# soundcard_v2_2.net
KiCad netlist of a schematic drawn in EAGLE
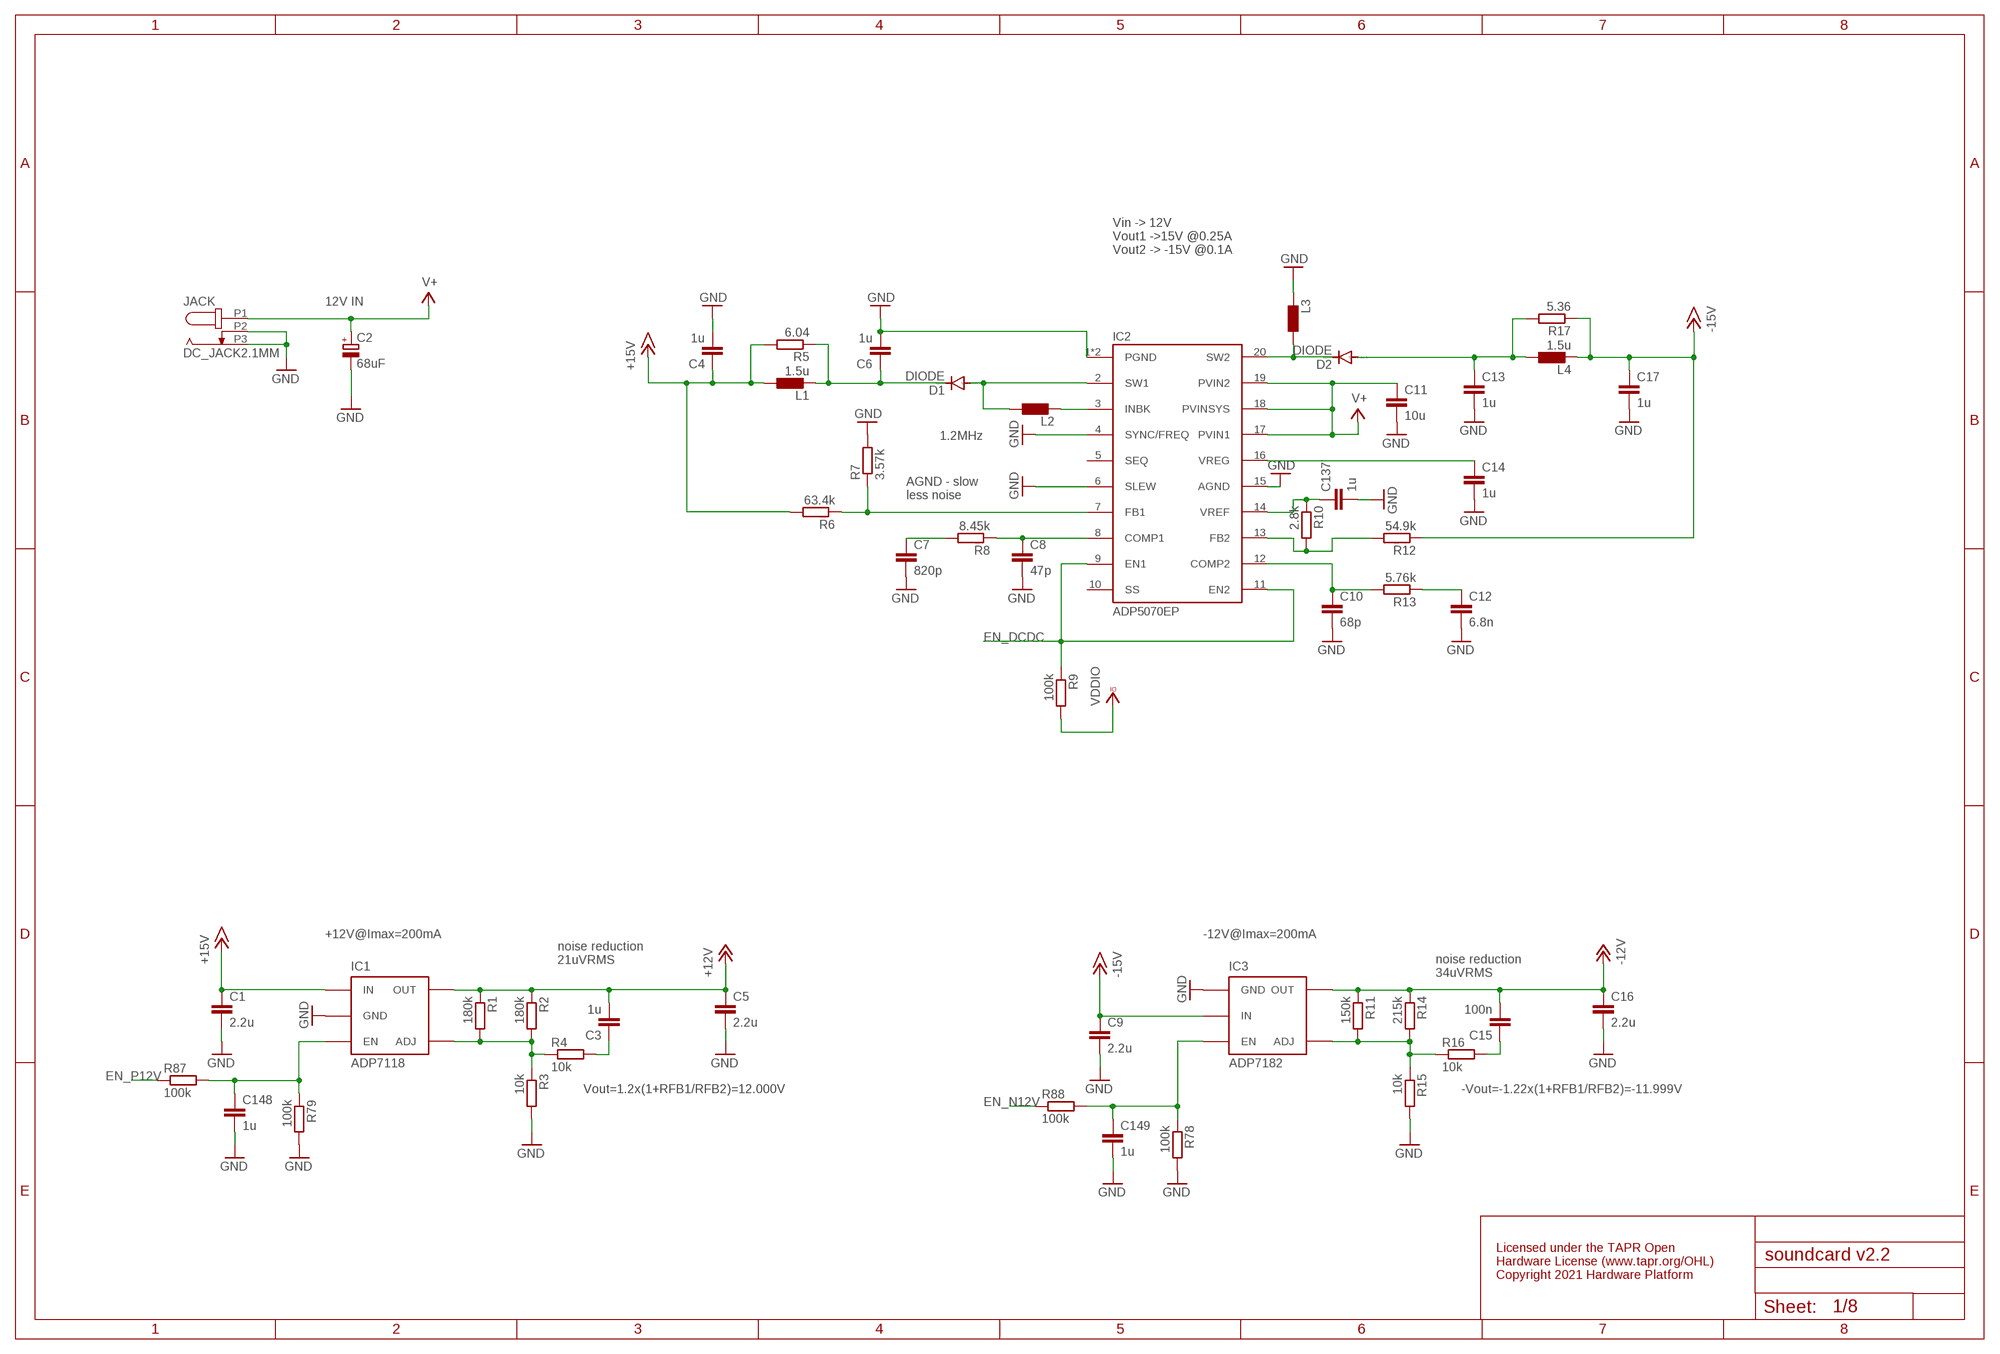
[diagram p0: schematic, sheet 1]
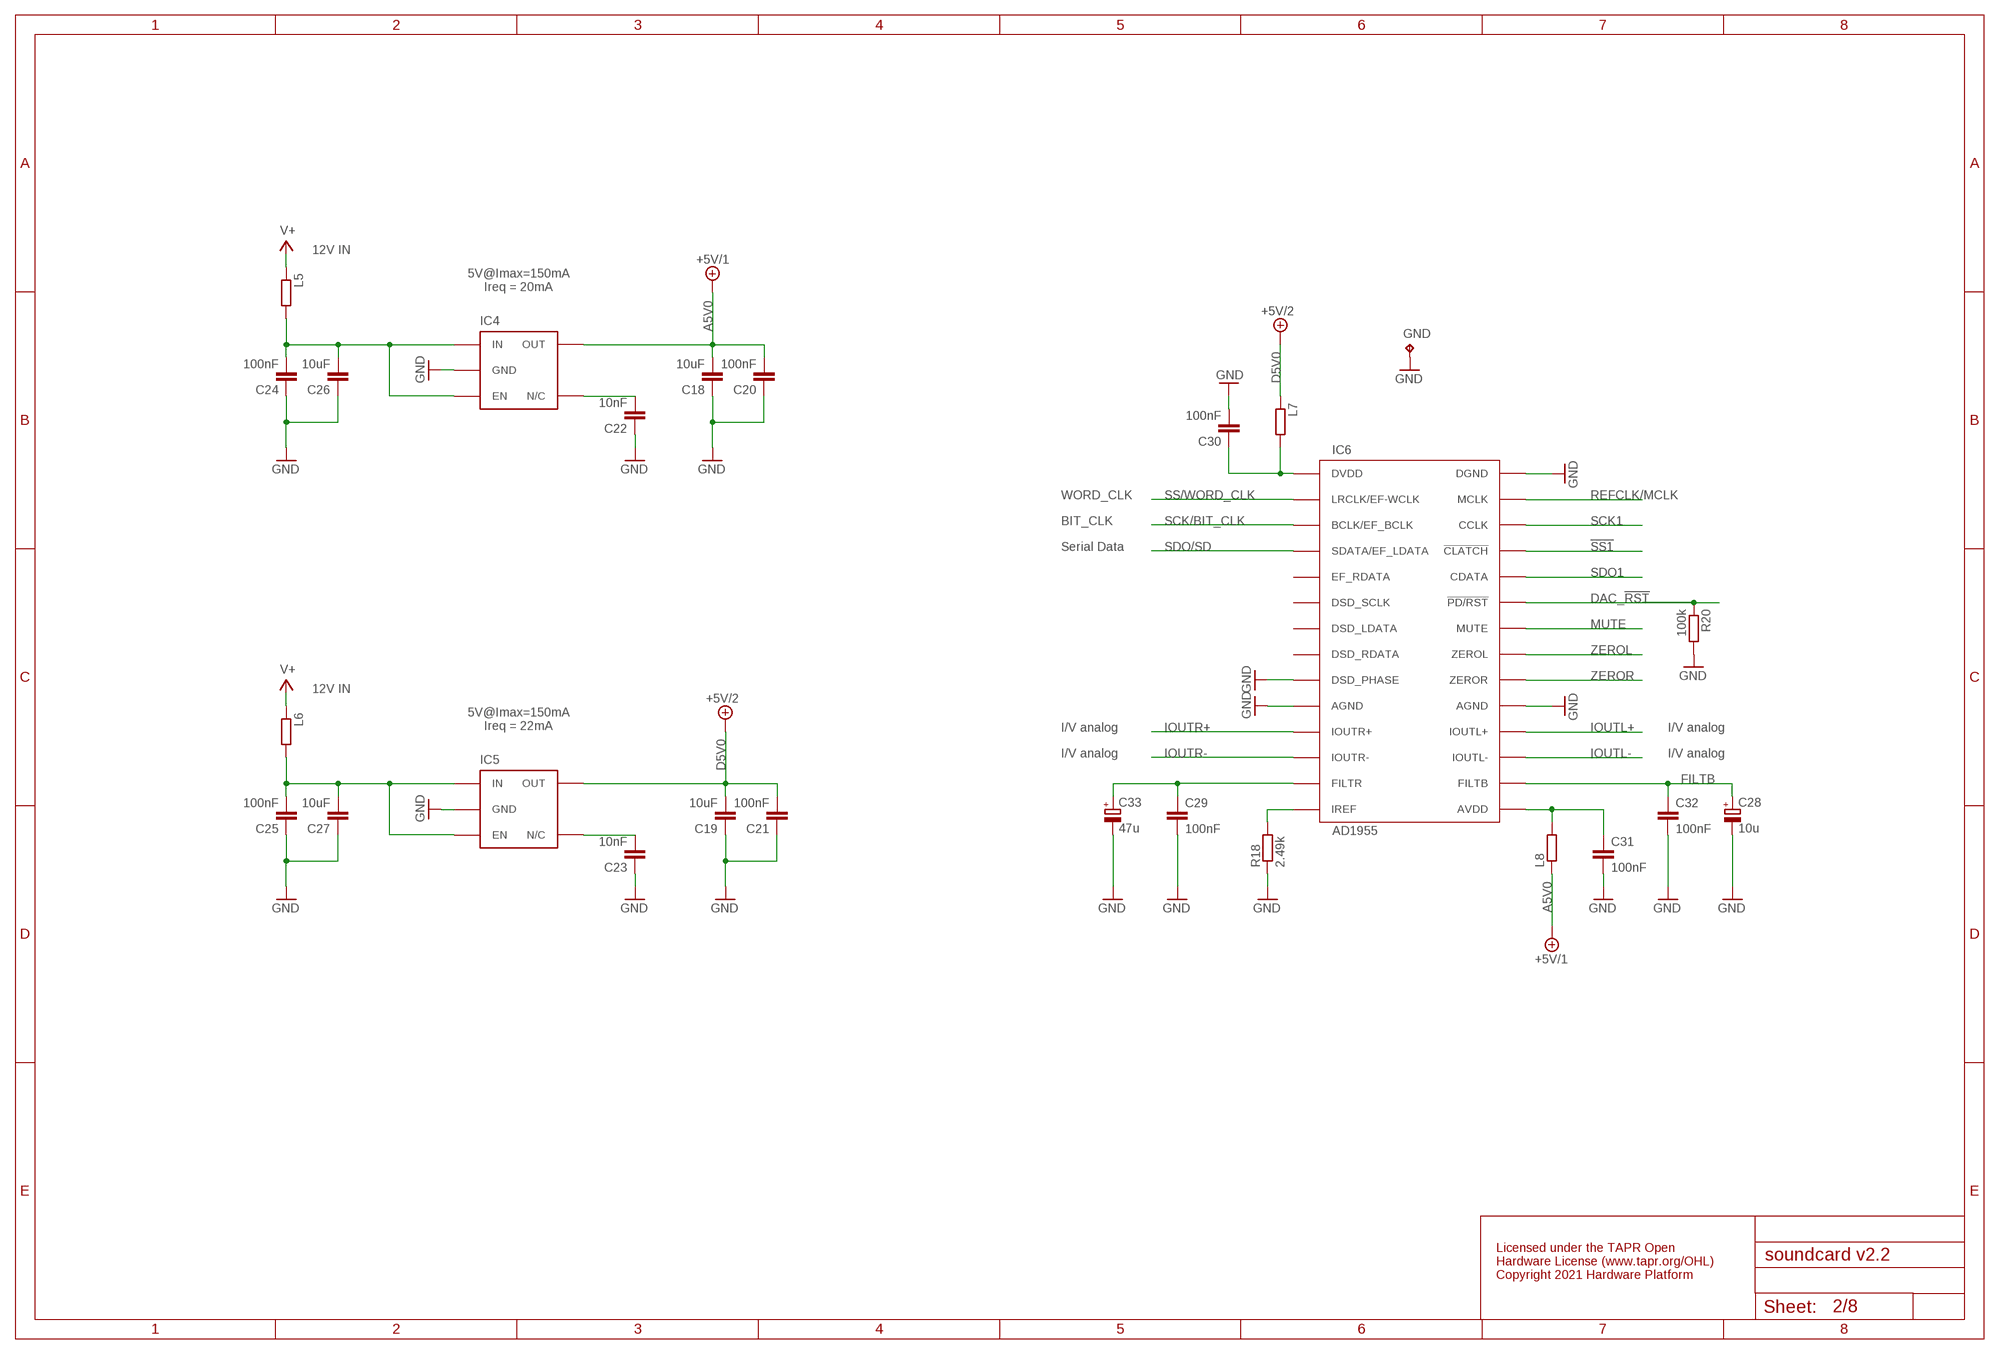
[diagram p1: schematic, sheet 2]
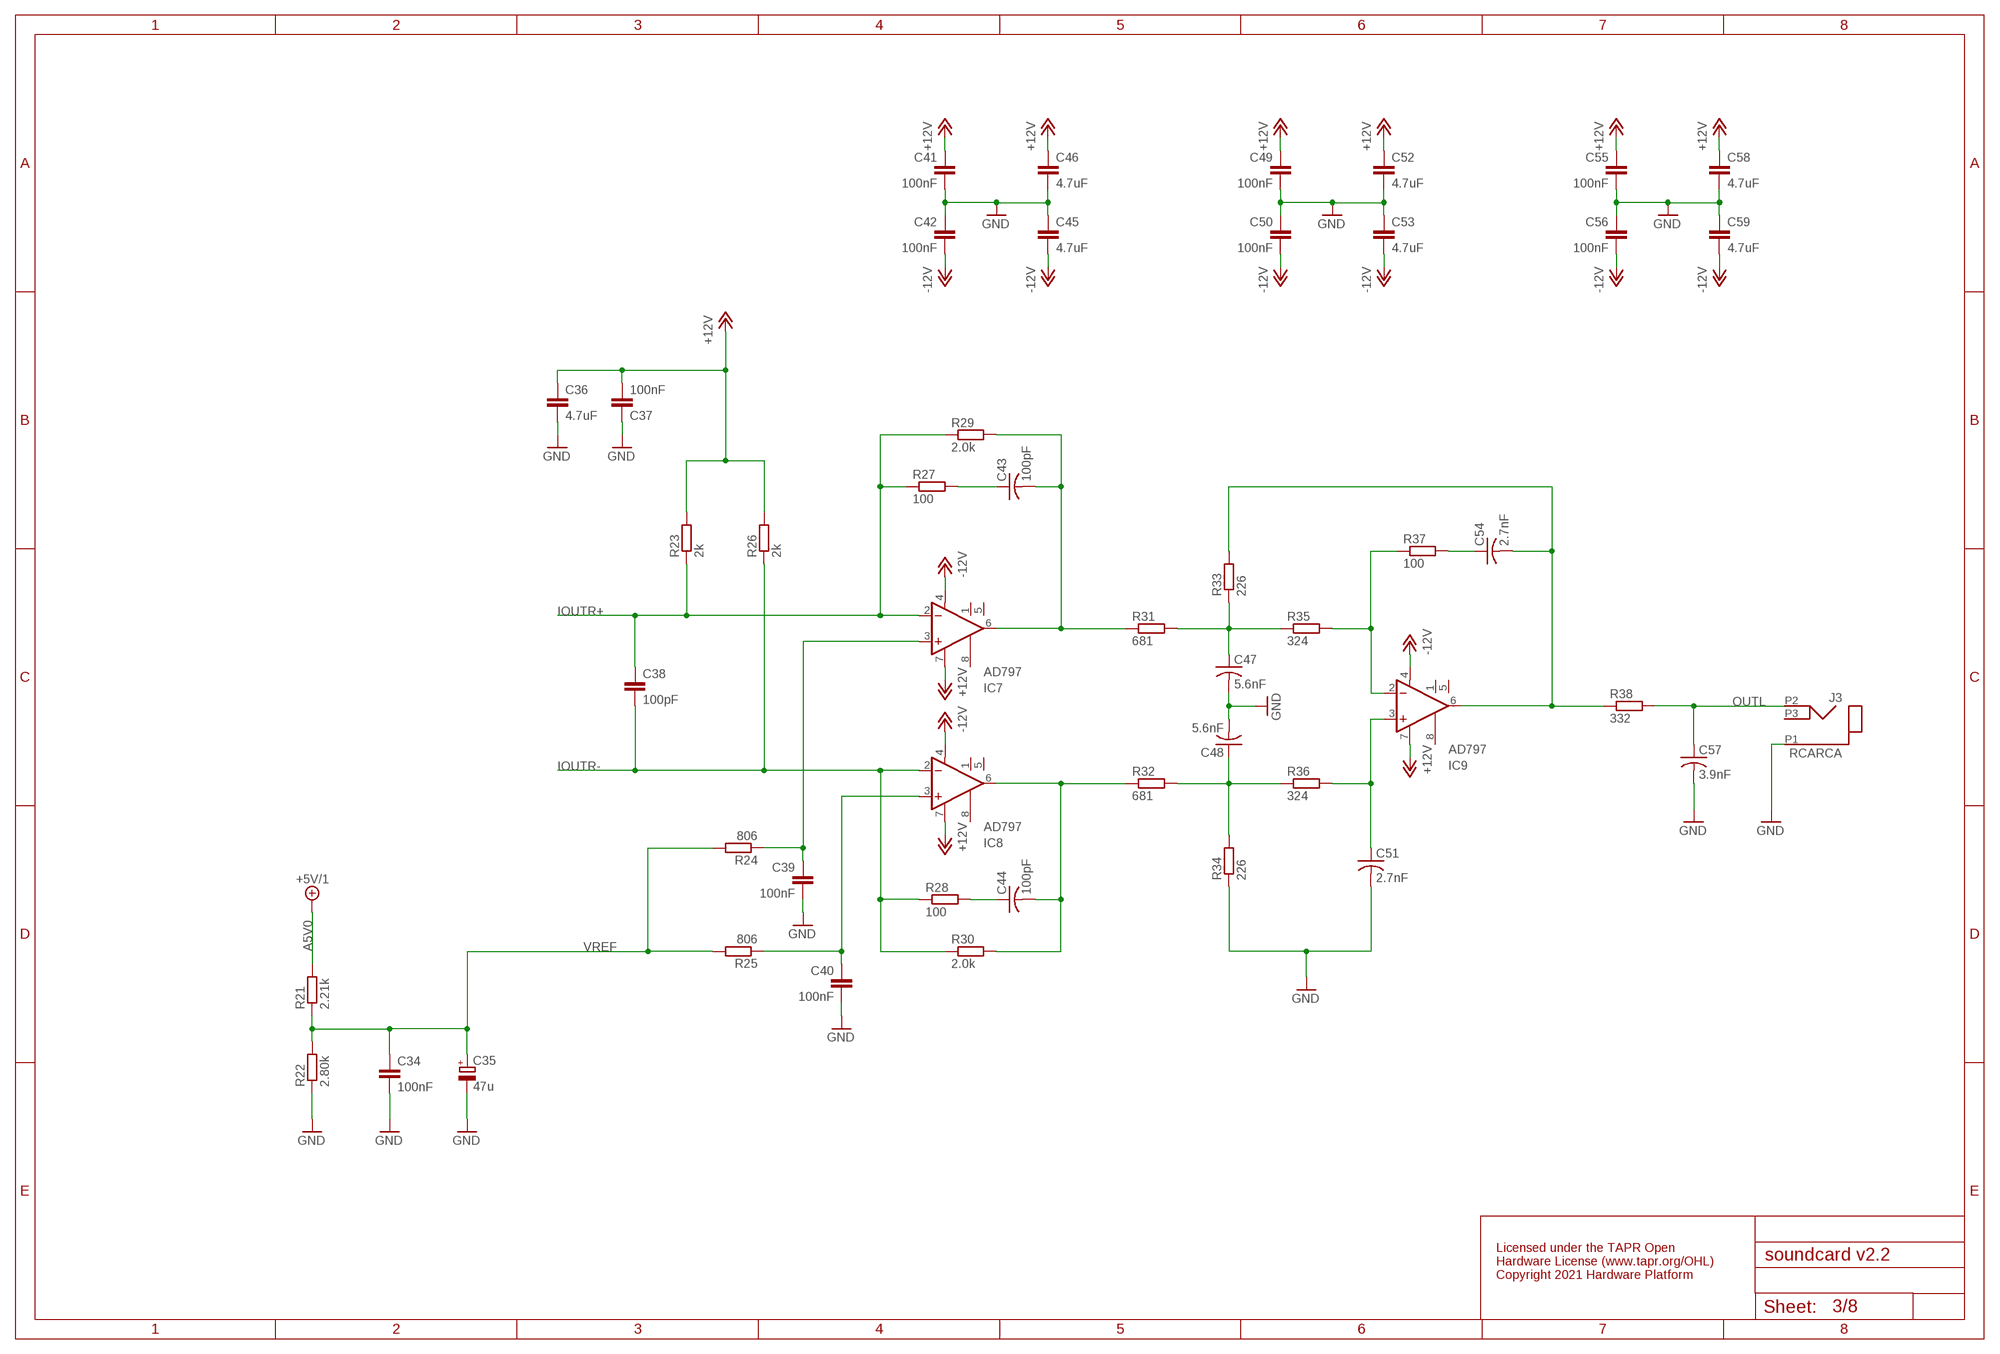
[diagram p2: schematic, sheet 3]
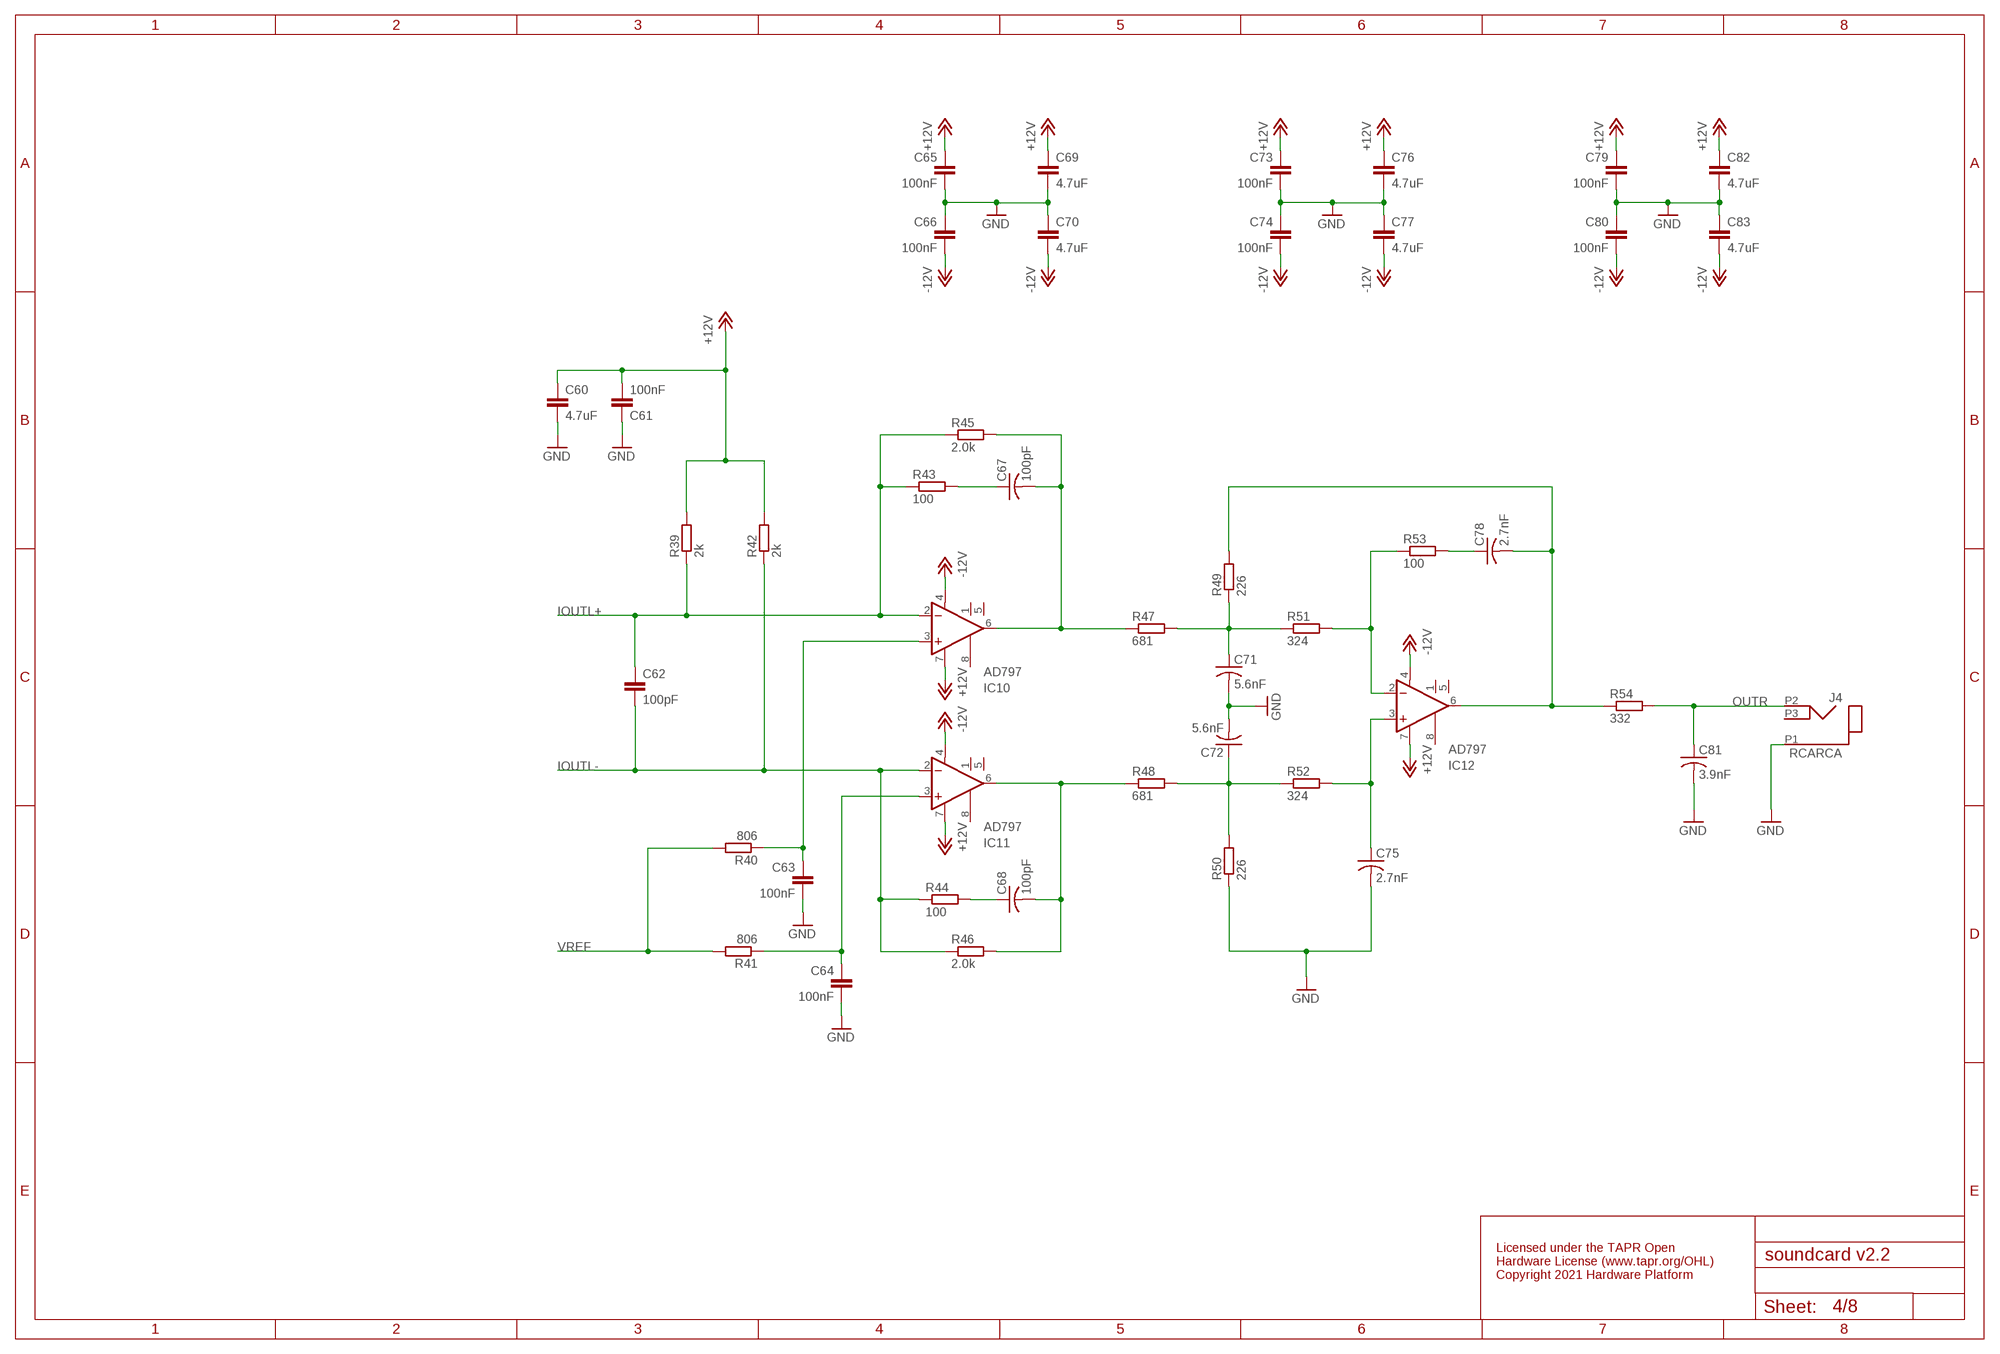
[diagram p3: schematic, sheet 4]
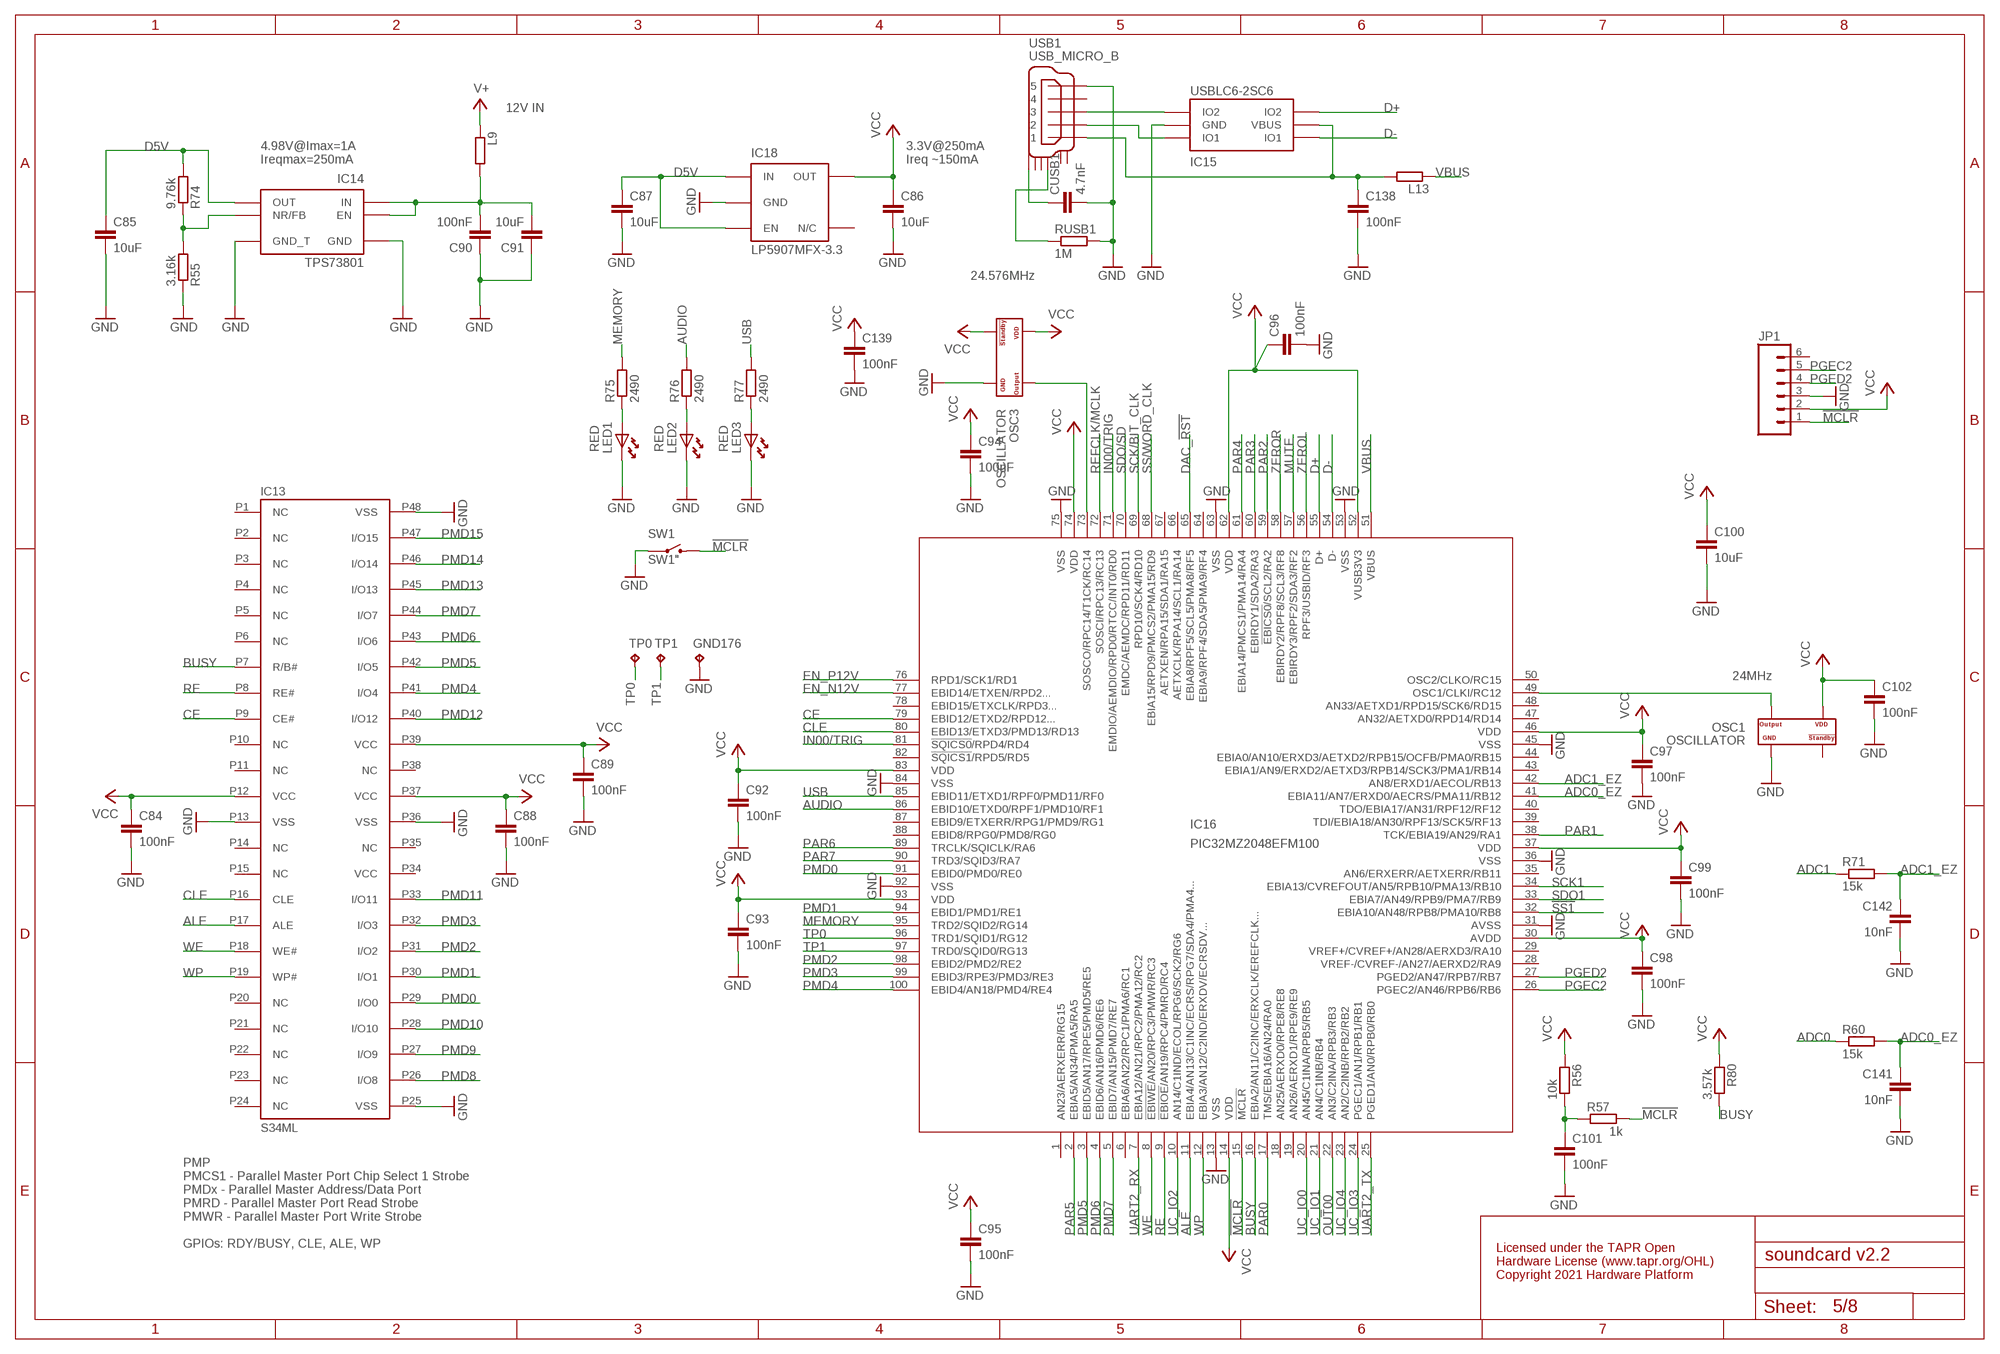
[diagram p4: schematic, sheet 5]
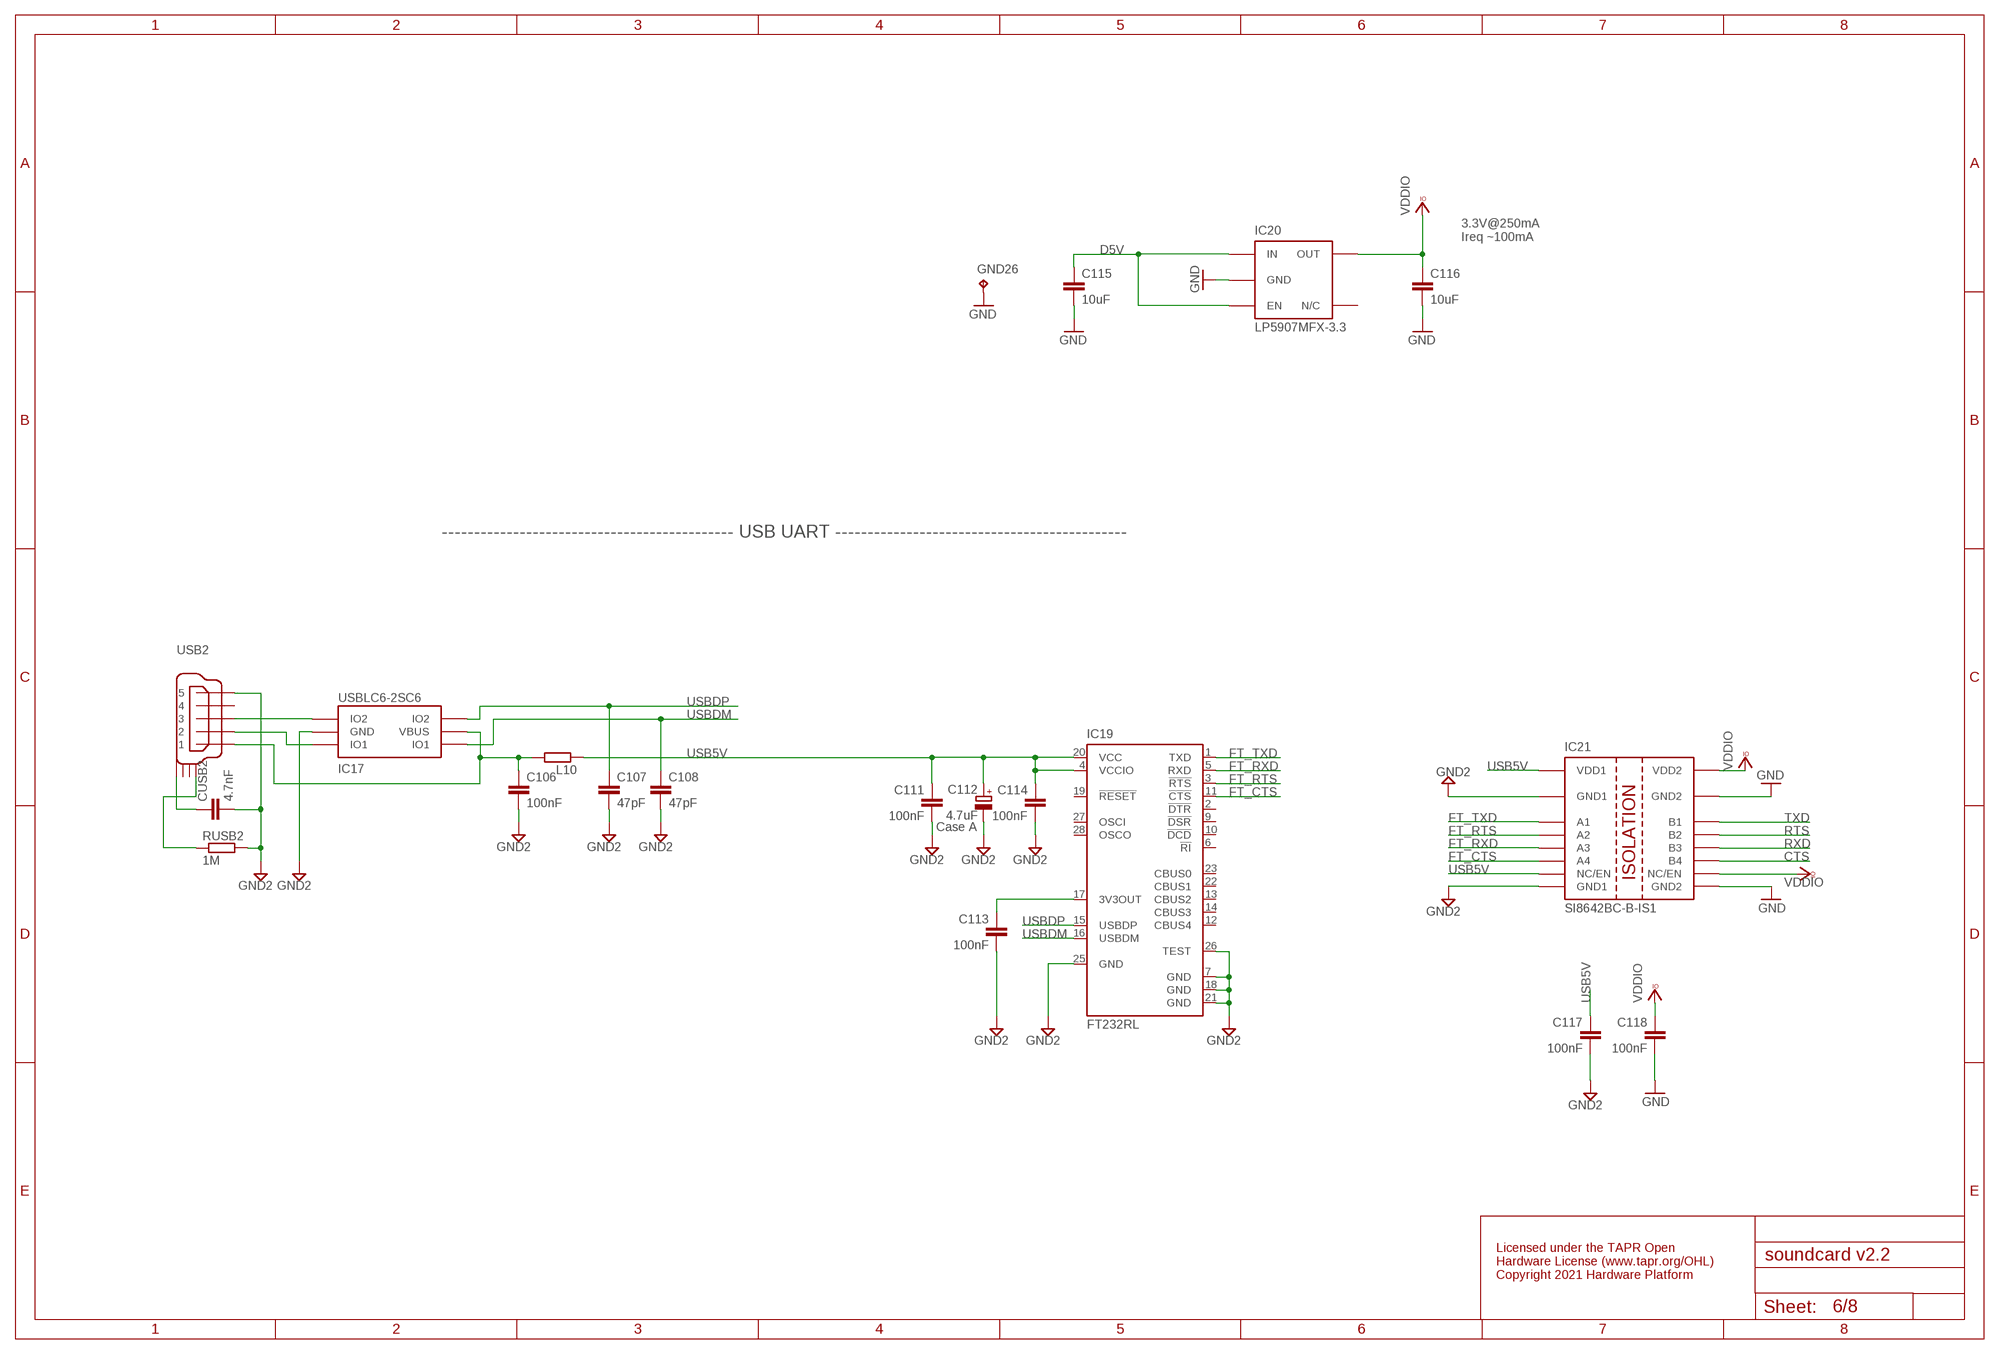
[diagram p5: schematic, sheet 6]
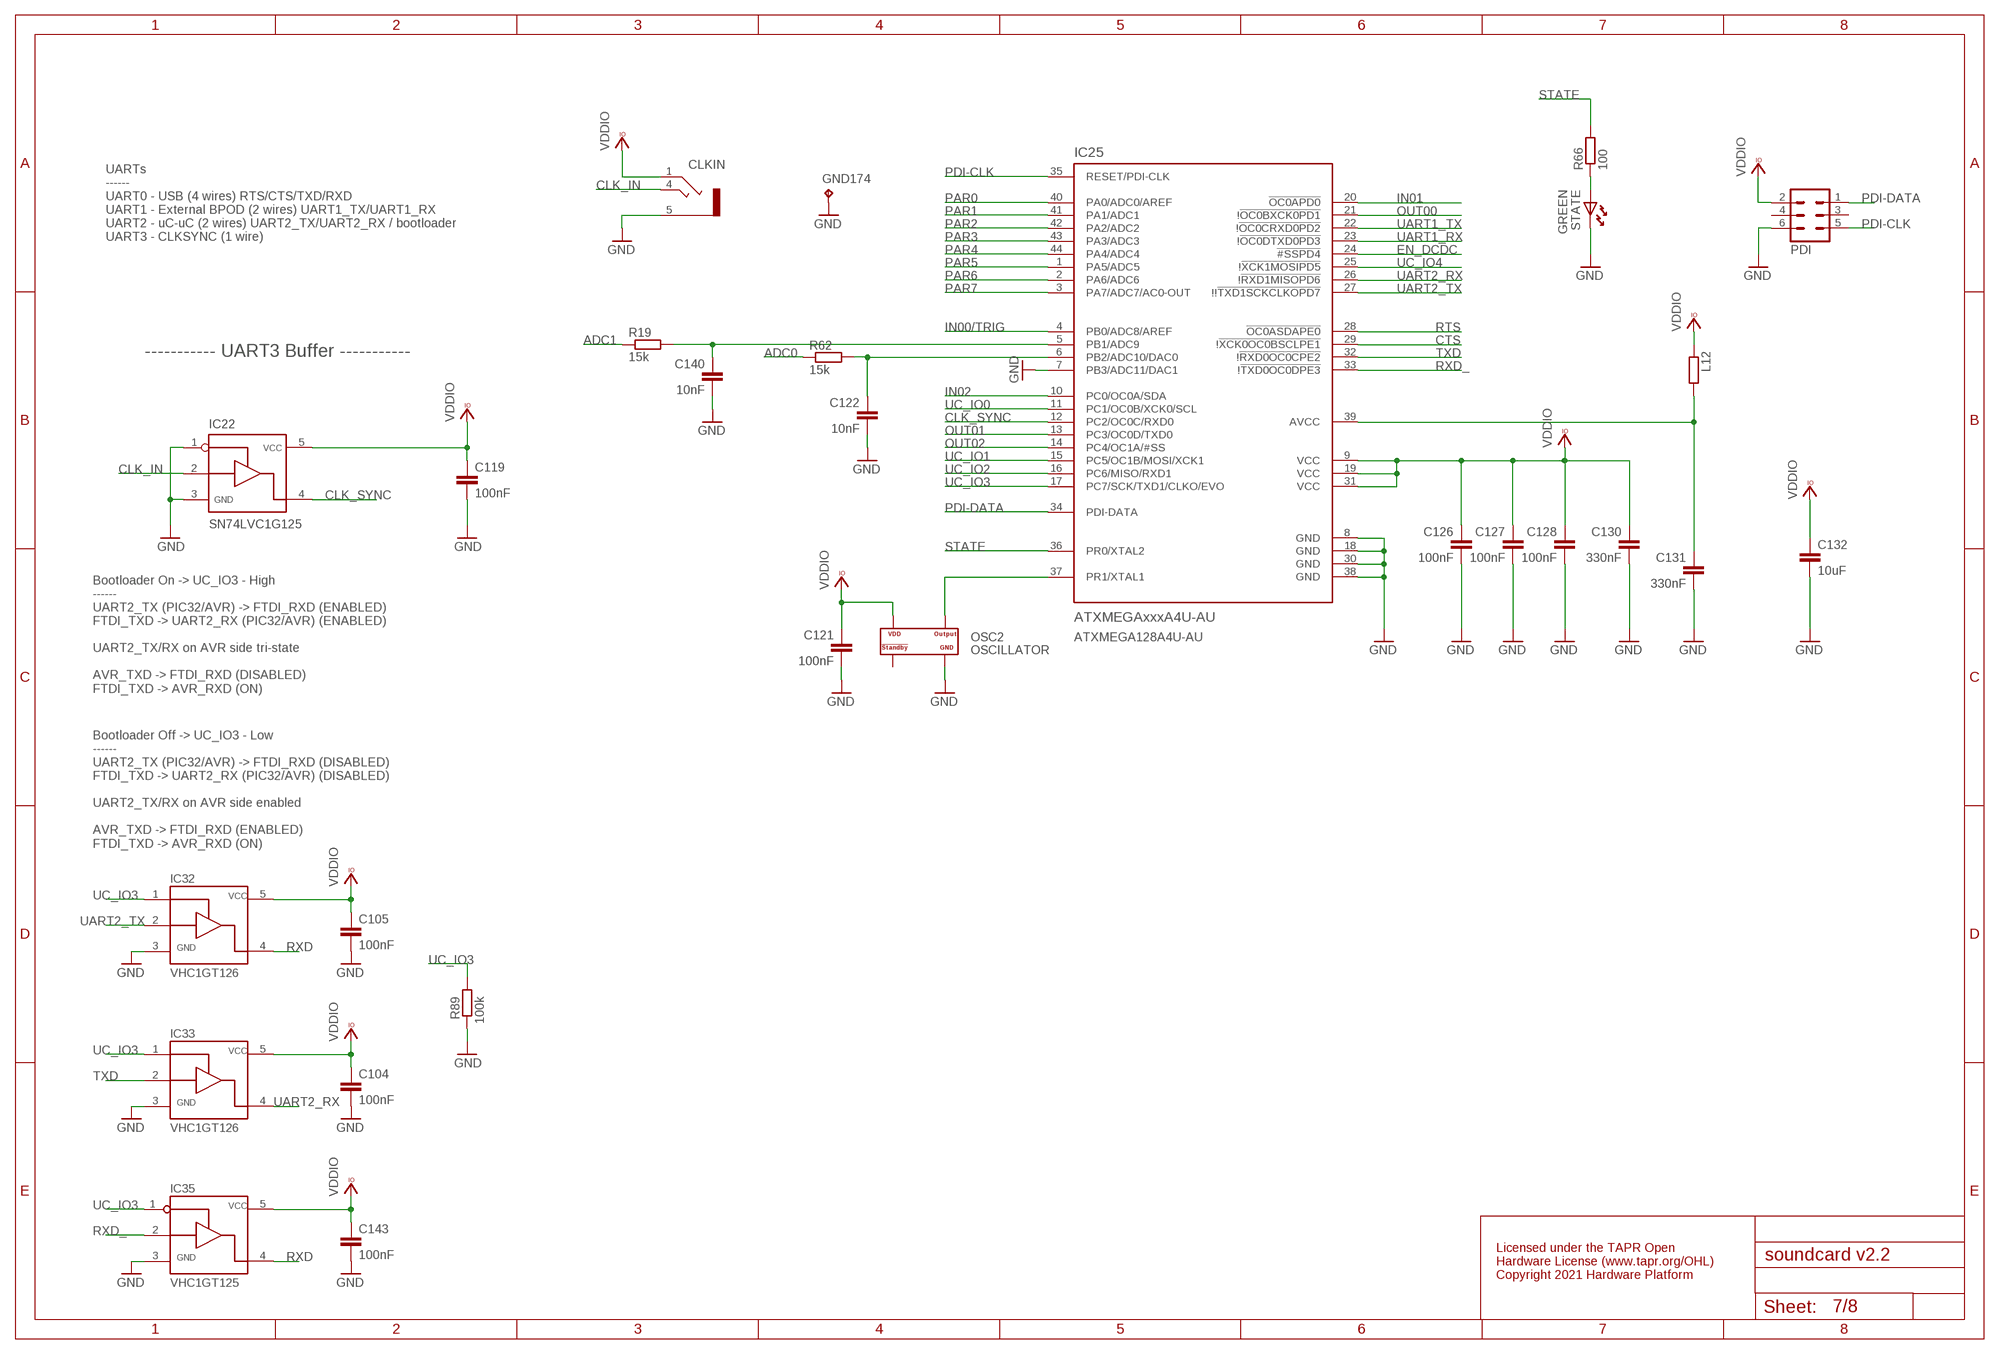
[diagram p6: schematic, sheet 7]
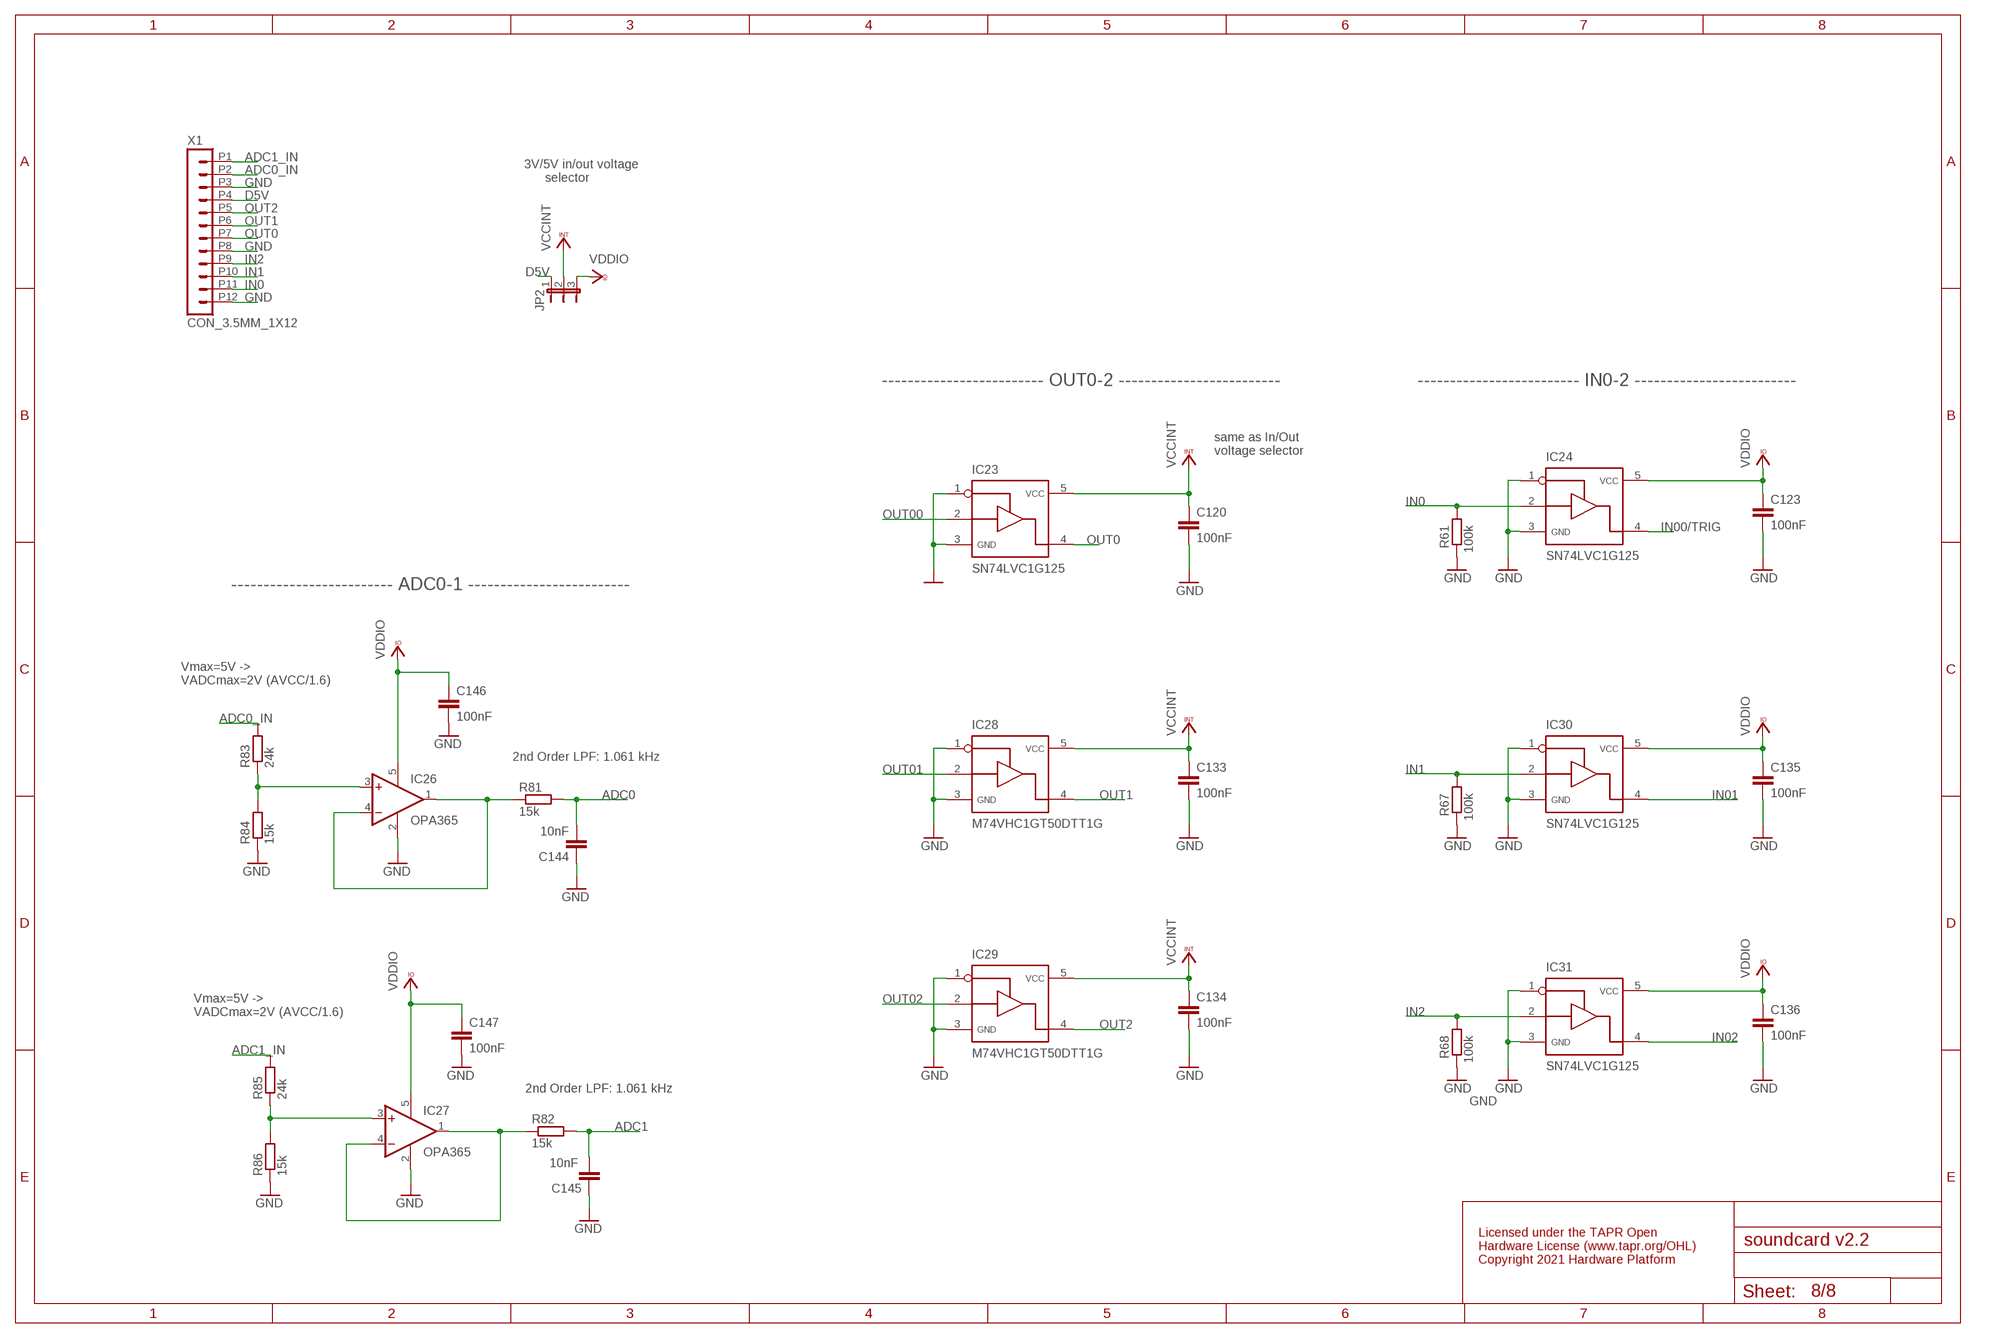
[diagram p7: schematic, sheet 8]

(export (version "E")
  (design (tool "Eeschema 10.0.6"))
  (components
    (comp (ref "C104")
      (value "100nF")
      (footprint "eagle-import:C0402")
      (libsource (lib "eagle-import") (part "rcl_334_C-EUC0402"))
    )
    (comp (ref "C105")
      (value "100nF")
      (footprint "eagle-import:C0402")
      (libsource (lib "eagle-import") (part "rcl_334_C-EUC0402"))
    )
    (comp (ref "C119")
      (value "100nF")
      (footprint "eagle-import:C0402")
      (libsource (lib "eagle-import") (part "rcl_334_C-EUC0402"))
    )
    (comp (ref "C121")
      (value "100nF")
      (footprint "eagle-import:C0402")
      (libsource (lib "eagle-import") (part "rcl_334_C-EUC0402"))
    )
    (comp (ref "C122")
      (value "10nF")
      (footprint "eagle-import:C0402")
      (libsource (lib "eagle-import") (part "C-EUC0402"))
    )
    (comp (ref "C126")
      (value "100nF")
      (footprint "eagle-import:C0402")
      (libsource (lib "eagle-import") (part "rcl_334_C-EUC0402"))
    )
    (comp (ref "C127")
      (value "100nF")
      (footprint "eagle-import:C0402")
      (libsource (lib "eagle-import") (part "rcl_334_C-EUC0402"))
    )
    (comp (ref "C128")
      (value "100nF")
      (footprint "eagle-import:C0402")
      (libsource (lib "eagle-import") (part "rcl_334_C-EUC0402"))
    )
    (comp (ref "C130")
      (value "330nF")
      (footprint "eagle-import:C0402")
      (libsource (lib "eagle-import") (part "rcl_334_C-EUC0402"))
    )
    (comp (ref "C131")
      (value "330nF")
      (footprint "eagle-import:C0402")
      (libsource (lib "eagle-import") (part "rcl_334_C-EUC0402"))
    )
    (comp (ref "C132")
      (value "10uF")
      (footprint "eagle-import:C0603")
      (libsource (lib "eagle-import") (part "rcl_334_C-EUC0603"))
    )
    (comp (ref "C140")
      (value "10nF")
      (footprint "eagle-import:C0402")
      (libsource (lib "eagle-import") (part "C-EUC0402"))
    )
    (comp (ref "C143")
      (value "100nF")
      (footprint "eagle-import:C0402")
      (libsource (lib "eagle-import") (part "rcl_334_C-EUC0402"))
    )
    (comp (ref "CLKIN")
      (value "STEREO_JACK")
      (footprint "eagle-import:35RASMT2BHNTRX")
      (libsource (lib "eagle-import") (part "STEREO_JACK"))
    )
    (comp (ref "GND174")
      (value "TP")
      (footprint "eagle-import:TP_1")
      (libsource (lib "eagle-import") (part "TP"))
    )
    (comp (ref "IC22")
      (value "SN74LVC1G125")
      (footprint "eagle-import:SOT23-5")
      (libsource (lib "eagle-import") (part "SN74LVC1G125"))
    )
    (comp (ref "IC25")
      (value "ATXMEGAxxxA4U-AU")
      (footprint "eagle-import:QFP80P1200X1200X120-44N")
      (libsource (lib "eagle-import") (part "AT-XMEGA-XXA4-AU"))
    )
    (comp (ref "IC32")
      (value "VHC1GT126")
      (footprint "eagle-import:SC-70-5")
      (libsource (lib "eagle-import") (part "VHC1GT126"))
    )
    (comp (ref "IC33")
      (value "VHC1GT126")
      (footprint "eagle-import:SC-70-5")
      (libsource (lib "eagle-import") (part "VHC1GT126"))
    )
    (comp (ref "IC35")
      (value "VHC1GT125")
      (footprint "eagle-import:SC-70-5")
      (libsource (lib "eagle-import") (part "VHC1GT125"))
    )
    (comp (ref "L12")
      (value "???")
      (footprint "eagle-import:R0805")
      (libsource (lib "eagle-import") (part "rcl_334_R-EU_R0805"))
    )
    (comp (ref "OSC2")
      (value "OSCILLATOR")
      (footprint "eagle-import:OSCILLATOR_3.2X2.5")
      (libsource (lib "eagle-import") (part "OSCILLATOR"))
    )
    (comp (ref "PDI")
      (value "MA03-2")
      (footprint "eagle-import:MA03-2")
      (libsource (lib "eagle-import") (part "MA03-2"))
    )
    (comp (ref "R19")
      (value "15k")
      (footprint "eagle-import:R0402")
      (libsource (lib "eagle-import") (part "R-EU_R0402"))
    )
    (comp (ref "R62")
      (value "15k")
      (footprint "eagle-import:R0402")
      (libsource (lib "eagle-import") (part "R-EU_R0402"))
    )
    (comp (ref "R66")
      (value "100")
      (footprint "eagle-import:R0402")
      (libsource (lib "eagle-import") (part "rcl_334_R-EU_R0402"))
    )
    (comp (ref "R89")
      (value "100k")
      (footprint "eagle-import:R0402")
      (libsource (lib "eagle-import") (part "rcl_334_R-EU_R0402"))
    )
    (comp (ref "STATE")
      (value "GREEN")
      (footprint "eagle-import:LED_HAND")
      (libsource (lib "eagle-import") (part "LEDHAND"))
    )
    (comp (ref "C106")
      (value "100nF")
      (footprint "eagle-import:C0402")
      (libsource (lib "eagle-import") (part "rcl_334_C-EUC0402"))
    )
    (comp (ref "C107")
      (value "47pF")
      (footprint "eagle-import:C0402")
      (libsource (lib "eagle-import") (part "rcl_334_C-EUC0402"))
    )
    (comp (ref "C108")
      (value "47pF")
      (footprint "eagle-import:C0402")
      (libsource (lib "eagle-import") (part "rcl_334_C-EUC0402"))
    )
    (comp (ref "C111")
      (value "100nF")
      (footprint "eagle-import:C0402")
      (libsource (lib "eagle-import") (part "rcl_334_C-EUC0402"))
    )
    (comp (ref "C112")
      (value "4.7uF")
      (footprint "eagle-import:A_3216-18W")
      (libsource (lib "eagle-import") (part "CPOL-EUA/3216-18W"))
    )
    (comp (ref "C113")
      (value "100nF")
      (footprint "eagle-import:C0402")
      (libsource (lib "eagle-import") (part "rcl_334_C-EUC0402"))
    )
    (comp (ref "C114")
      (value "100nF")
      (footprint "eagle-import:C0402")
      (libsource (lib "eagle-import") (part "rcl_334_C-EUC0402"))
    )
    (comp (ref "C115")
      (value "10uF")
      (footprint "eagle-import:C0603")
      (libsource (lib "eagle-import") (part "rcl_334_C-EUC0603"))
    )
    (comp (ref "C116")
      (value "10uF")
      (footprint "eagle-import:C0603")
      (libsource (lib "eagle-import") (part "rcl_334_C-EUC0603"))
    )
    (comp (ref "C117")
      (value "100nF")
      (footprint "eagle-import:C0402")
      (libsource (lib "eagle-import") (part "rcl_334_C-EUC0402"))
    )
    (comp (ref "C118")
      (value "100nF")
      (footprint "eagle-import:C0402")
      (libsource (lib "eagle-import") (part "rcl_334_C-EUC0402"))
    )
    (comp (ref "CUSB2")
      (value "4.7nF")
      (footprint "eagle-import:C0402")
      (libsource (lib "eagle-import") (part "rcl_334_C-EUC0402"))
    )
    (comp (ref "GND26")
      (value "TP")
      (footprint "eagle-import:TP_1")
      (libsource (lib "eagle-import") (part "TP"))
    )
    (comp (ref "IC17")
      (value "USBLC6-2SC6")
      (footprint "eagle-import:SOT23-6L")
      (libsource (lib "eagle-import") (part "USBLC6-2"))
    )
    (comp (ref "IC19")
      (value "FT232RL")
      (footprint "eagle-import:SSOP28")
      (libsource (lib "eagle-import") (part "FT232RL"))
    )
    (comp (ref "IC20")
      (value "LP5907MFX-3.3")
      (footprint "eagle-import:TSOT23-5")
      (libsource (lib "eagle-import") (part "TLV700XX"))
    )
    (comp (ref "IC21")
      (value "SI8642BC-B-IS1")
      (footprint "eagle-import:NSOIC-16")
      (libsource (lib "eagle-import") (part "SI8645"))
    )
    (comp (ref "L10")
      (value "???")
      (footprint "eagle-import:R0805")
      (libsource (lib "eagle-import") (part "rcl_334_R-EU_R0805"))
    )
    (comp (ref "RUSB2")
      (value "1M")
      (footprint "eagle-import:R0402")
      (libsource (lib "eagle-import") (part "rcl_334_R-EU_R0402"))
    )
    (comp (ref "USB2")
      (value "USB_MINI_B")
      (footprint "eagle-import:240-0002-1")
      (libsource (lib "eagle-import") (part "USB_MINI_B"))
    )
    (comp (ref "C60")
      (value "4.7uF")
      (footprint "eagle-import:C0603")
      (libsource (lib "eagle-import") (part "rcl_334_C-EUC0603"))
    )
    (comp (ref "C61")
      (value "100nF")
      (footprint "eagle-import:C0402")
      (libsource (lib "eagle-import") (part "rcl_334_C-EUC0402"))
    )
    (comp (ref "C62")
      (value "100pF")
      (footprint "eagle-import:C0603")
      (libsource (lib "eagle-import") (part "rcl_334_C-EUC0603"))
    )
    (comp (ref "C63")
      (value "100nF")
      (footprint "eagle-import:C0402")
      (libsource (lib "eagle-import") (part "rcl_334_C-EUC0402"))
    )
    (comp (ref "C64")
      (value "100nF")
      (footprint "eagle-import:C0402")
      (libsource (lib "eagle-import") (part "rcl_334_C-EUC0402"))
    )
    (comp (ref "C65")
      (value "100nF")
      (footprint "eagle-import:C0402")
      (libsource (lib "eagle-import") (part "rcl_334_C-EUC0402"))
    )
    (comp (ref "C66")
      (value "100nF")
      (footprint "eagle-import:C0402")
      (libsource (lib "eagle-import") (part "rcl_334_C-EUC0402"))
    )
    (comp (ref "C67")
      (value "100pF")
      (footprint "eagle-import:C050-025X075")
      (libsource (lib "eagle-import") (part "C-US050-025X075"))
    )
    (comp (ref "C68")
      (value "100pF")
      (footprint "eagle-import:C050-025X075")
      (libsource (lib "eagle-import") (part "C-US050-025X075"))
    )
    (comp (ref "C69")
      (value "4.7uF")
      (footprint "eagle-import:C0603")
      (libsource (lib "eagle-import") (part "rcl_334_C-EUC0603"))
    )
    (comp (ref "C70")
      (value "4.7uF")
      (footprint "eagle-import:C0603")
      (libsource (lib "eagle-import") (part "rcl_334_C-EUC0603"))
    )
    (comp (ref "C71")
      (value "5.6nF")
      (footprint "eagle-import:C050-025X075")
      (libsource (lib "eagle-import") (part "C-US050-025X075"))
    )
    (comp (ref "C72")
      (value "5.6nF")
      (footprint "eagle-import:C050-025X075")
      (libsource (lib "eagle-import") (part "C-US050-025X075"))
    )
    (comp (ref "C73")
      (value "100nF")
      (footprint "eagle-import:C0402")
      (libsource (lib "eagle-import") (part "rcl_334_C-EUC0402"))
    )
    (comp (ref "C74")
      (value "100nF")
      (footprint "eagle-import:C0402")
      (libsource (lib "eagle-import") (part "rcl_334_C-EUC0402"))
    )
    (comp (ref "C75")
      (value "2.7nF")
      (footprint "eagle-import:C050-025X075")
      (libsource (lib "eagle-import") (part "C-US050-025X075"))
    )
    (comp (ref "C76")
      (value "4.7uF")
      (footprint "eagle-import:C0603")
      (libsource (lib "eagle-import") (part "rcl_334_C-EUC0603"))
    )
    (comp (ref "C77")
      (value "4.7uF")
      (footprint "eagle-import:C0603")
      (libsource (lib "eagle-import") (part "rcl_334_C-EUC0603"))
    )
    (comp (ref "C78")
      (value "2.7nF")
      (footprint "eagle-import:C050-025X075")
      (libsource (lib "eagle-import") (part "C-US050-025X075"))
    )
    (comp (ref "C79")
      (value "100nF")
      (footprint "eagle-import:C0402")
      (libsource (lib "eagle-import") (part "rcl_334_C-EUC0402"))
    )
    (comp (ref "C80")
      (value "100nF")
      (footprint "eagle-import:C0402")
      (libsource (lib "eagle-import") (part "rcl_334_C-EUC0402"))
    )
    (comp (ref "C81")
      (value "3.9nF")
      (footprint "eagle-import:C050-025X075")
      (libsource (lib "eagle-import") (part "C-US050-025X075"))
    )
    (comp (ref "C82")
      (value "4.7uF")
      (footprint "eagle-import:C0603")
      (libsource (lib "eagle-import") (part "rcl_334_C-EUC0603"))
    )
    (comp (ref "C83")
      (value "4.7uF")
      (footprint "eagle-import:C0603")
      (libsource (lib "eagle-import") (part "rcl_334_C-EUC0603"))
    )
    (comp (ref "IC10")
      (value "AD797")
      (footprint "eagle-import:SO08")
      (libsource (lib "eagle-import") (part "AD797"))
    )
    (comp (ref "IC11")
      (value "AD797")
      (footprint "eagle-import:SO08")
      (libsource (lib "eagle-import") (part "AD797"))
    )
    (comp (ref "IC12")
      (value "AD797")
      (footprint "eagle-import:SO08")
      (libsource (lib "eagle-import") (part "AD797"))
    )
    (comp (ref "J4")
      (value "RCARCA")
      (footprint "eagle-import:RCA")
      (libsource (lib "eagle-import") (part "RCARCA"))
    )
    (comp (ref "R39")
      (value "2k")
      (footprint "eagle-import:R0402")
      (libsource (lib "eagle-import") (part "rcl_334_R-EU_R0402"))
    )
    (comp (ref "R40")
      (value "806")
      (footprint "eagle-import:R0402")
      (libsource (lib "eagle-import") (part "rcl_334_R-EU_R0402"))
    )
    (comp (ref "R41")
      (value "806")
      (footprint "eagle-import:R0402")
      (libsource (lib "eagle-import") (part "rcl_334_R-EU_R0402"))
    )
    (comp (ref "R42")
      (value "2k")
      (footprint "eagle-import:R0402")
      (libsource (lib "eagle-import") (part "rcl_334_R-EU_R0402"))
    )
    (comp (ref "R43")
      (value "100")
      (footprint "eagle-import:R0402")
      (libsource (lib "eagle-import") (part "rcl_334_R-EU_R0402"))
    )
    (comp (ref "R44")
      (value "100")
      (footprint "eagle-import:R0402")
      (libsource (lib "eagle-import") (part "rcl_334_R-EU_R0402"))
    )
    (comp (ref "R45")
      (value "2.0k")
      (footprint "eagle-import:R0402")
      (libsource (lib "eagle-import") (part "rcl_334_R-EU_R0402"))
    )
    (comp (ref "R46")
      (value "2.0k")
      (footprint "eagle-import:R0402")
      (libsource (lib "eagle-import") (part "rcl_334_R-EU_R0402"))
    )
    (comp (ref "R47")
      (value "681")
      (footprint "eagle-import:R0402")
      (libsource (lib "eagle-import") (part "rcl_334_R-EU_R0402"))
    )
    (comp (ref "R48")
      (value "681")
      (footprint "eagle-import:R0402")
      (libsource (lib "eagle-import") (part "rcl_334_R-EU_R0402"))
    )
    (comp (ref "R49")
      (value "226")
      (footprint "eagle-import:R0402")
      (libsource (lib "eagle-import") (part "rcl_334_R-EU_R0402"))
    )
    (comp (ref "R50")
      (value "226")
      (footprint "eagle-import:R0402")
      (libsource (lib "eagle-import") (part "rcl_334_R-EU_R0402"))
    )
    (comp (ref "R51")
      (value "324")
      (footprint "eagle-import:R0402")
      (libsource (lib "eagle-import") (part "rcl_334_R-EU_R0402"))
    )
    (comp (ref "R52")
      (value "324")
      (footprint "eagle-import:R0402")
      (libsource (lib "eagle-import") (part "rcl_334_R-EU_R0402"))
    )
    (comp (ref "R53")
      (value "100")
      (footprint "eagle-import:R0402")
      (libsource (lib "eagle-import") (part "rcl_334_R-EU_R0402"))
    )
    (comp (ref "R54")
      (value "332")
      (footprint "eagle-import:R0402")
      (libsource (lib "eagle-import") (part "rcl_334_R-EU_R0402"))
    )
    (comp (ref "C120")
      (value "100nF")
      (footprint "eagle-import:C0402")
      (libsource (lib "eagle-import") (part "rcl_334_C-EUC0402"))
    )
    (comp (ref "C123")
      (value "100nF")
      (footprint "eagle-import:C0402")
      (libsource (lib "eagle-import") (part "rcl_334_C-EUC0402"))
    )
    (comp (ref "C133")
      (value "100nF")
      (footprint "eagle-import:C0402")
      (libsource (lib "eagle-import") (part "rcl_334_C-EUC0402"))
    )
    (comp (ref "C134")
      (value "100nF")
      (footprint "eagle-import:C0402")
      (libsource (lib "eagle-import") (part "rcl_334_C-EUC0402"))
    )
    (comp (ref "C135")
      (value "100nF")
      (footprint "eagle-import:C0402")
      (libsource (lib "eagle-import") (part "rcl_334_C-EUC0402"))
    )
    (comp (ref "C136")
      (value "100nF")
      (footprint "eagle-import:C0402")
      (libsource (lib "eagle-import") (part "rcl_334_C-EUC0402"))
    )
    (comp (ref "C144")
      (value "10nF")
      (footprint "eagle-import:C0402")
      (libsource (lib "eagle-import") (part "C-EUC0402"))
    )
    (comp (ref "C145")
      (value "10nF")
      (footprint "eagle-import:C0402")
      (libsource (lib "eagle-import") (part "C-EUC0402"))
    )
    (comp (ref "C146")
      (value "100nF")
      (footprint "eagle-import:C0402")
      (libsource (lib "eagle-import") (part "C-EUC0402"))
    )
    (comp (ref "C147")
      (value "100nF")
      (footprint "eagle-import:C0402")
      (libsource (lib "eagle-import") (part "C-EUC0402"))
    )
    (comp (ref "IC23")
      (value "SN74LVC1G125")
      (footprint "eagle-import:SOT23-5")
      (libsource (lib "eagle-import") (part "SN74LVC1G125"))
    )
    (comp (ref "IC24")
      (value "SN74LVC1G125")
      (footprint "eagle-import:SOT23-5")
      (libsource (lib "eagle-import") (part "SN74LVC1G125"))
    )
    (comp (ref "IC26")
      (value "OPA365")
      (footprint "eagle-import:SOT23-5")
      (libsource (lib "eagle-import") (part "OPA365"))
    )
    (comp (ref "IC27")
      (value "OPA365")
      (footprint "eagle-import:SOT23-5")
      (libsource (lib "eagle-import") (part "OPA365"))
    )
    (comp (ref "IC28")
      (value "M74VHC1GT50DTT1G")
      (footprint "eagle-import:SOT23-5")
      (libsource (lib "eagle-import") (part "SN74LVC1G125"))
    )
    (comp (ref "IC29")
      (value "M74VHC1GT50DTT1G")
      (footprint "eagle-import:SOT23-5")
      (libsource (lib "eagle-import") (part "SN74LVC1G125"))
    )
    (comp (ref "IC30")
      (value "SN74LVC1G125")
      (footprint "eagle-import:SOT23-5")
      (libsource (lib "eagle-import") (part "SN74LVC1G125"))
    )
    (comp (ref "IC31")
      (value "SN74LVC1G125")
      (footprint "eagle-import:SOT23-5")
      (libsource (lib "eagle-import") (part "SN74LVC1G125"))
    )
    (comp (ref "JP2")
      (value "JP2E")
      (footprint "eagle-import:JP2")
      (libsource (lib "eagle-import") (part "JP2E"))
    )
    (comp (ref "R61")
      (value "100k")
      (footprint "eagle-import:R0402")
      (libsource (lib "eagle-import") (part "rcl_334_R-EU_R0402"))
    )
    (comp (ref "R67")
      (value "100k")
      (footprint "eagle-import:R0402")
      (libsource (lib "eagle-import") (part "rcl_334_R-EU_R0402"))
    )
    (comp (ref "R68")
      (value "100k")
      (footprint "eagle-import:R0402")
      (libsource (lib "eagle-import") (part "rcl_334_R-EU_R0402"))
    )
    (comp (ref "R81")
      (value "15k")
      (footprint "eagle-import:R0402")
      (libsource (lib "eagle-import") (part "R-EU_R0402"))
    )
    (comp (ref "R82")
      (value "15k")
      (footprint "eagle-import:R0402")
      (libsource (lib "eagle-import") (part "R-EU_R0402"))
    )
    (comp (ref "R83")
      (value "24k")
      (footprint "eagle-import:R0402")
      (libsource (lib "eagle-import") (part "R-EU_R0402"))
    )
    (comp (ref "R84")
      (value "15k")
      (footprint "eagle-import:R0402")
      (libsource (lib "eagle-import") (part "R-EU_R0402"))
    )
    (comp (ref "R85")
      (value "24k")
      (footprint "eagle-import:R0402")
      (libsource (lib "eagle-import") (part "R-EU_R0402"))
    )
    (comp (ref "R86")
      (value "15k")
      (footprint "eagle-import:R0402")
      (libsource (lib "eagle-import") (part "R-EU_R0402"))
    )
    (comp (ref "X1")
      (value "CON_3.5MM_1X12")
      (footprint "eagle-import:CON_3.5MM_1X12")
      (libsource (lib "eagle-import") (part "CON_3.5MM_1X12"))
    )
    (comp (ref "C34")
      (value "100nF")
      (footprint "eagle-import:C0402")
      (libsource (lib "eagle-import") (part "rcl_334_C-EUC0402"))
    )
    (comp (ref "C35")
      (value "47u")
      (footprint "eagle-import:C_6032-28W")
      (libsource (lib "eagle-import") (part "CPOL-EUC/6032-28W"))
    )
    (comp (ref "C36")
      (value "4.7uF")
      (footprint "eagle-import:C0603")
      (libsource (lib "eagle-import") (part "rcl_334_C-EUC0603"))
    )
    (comp (ref "C37")
      (value "100nF")
      (footprint "eagle-import:C0402")
      (libsource (lib "eagle-import") (part "rcl_334_C-EUC0402"))
    )
    (comp (ref "C38")
      (value "100pF")
      (footprint "eagle-import:C0603")
      (libsource (lib "eagle-import") (part "rcl_334_C-EUC0603"))
    )
    (comp (ref "C39")
      (value "100nF")
      (footprint "eagle-import:C0402")
      (libsource (lib "eagle-import") (part "rcl_334_C-EUC0402"))
    )
    (comp (ref "C40")
      (value "100nF")
      (footprint "eagle-import:C0402")
      (libsource (lib "eagle-import") (part "rcl_334_C-EUC0402"))
    )
    (comp (ref "C41")
      (value "100nF")
      (footprint "eagle-import:C0402")
      (libsource (lib "eagle-import") (part "rcl_334_C-EUC0402"))
    )
    (comp (ref "C42")
      (value "100nF")
      (footprint "eagle-import:C0402")
      (libsource (lib "eagle-import") (part "rcl_334_C-EUC0402"))
    )
    (comp (ref "C43")
      (value "100pF")
      (footprint "eagle-import:C050-025X075")
      (libsource (lib "eagle-import") (part "C-US050-025X075"))
    )
    (comp (ref "C44")
      (value "100pF")
      (footprint "eagle-import:C050-025X075")
      (libsource (lib "eagle-import") (part "C-US050-025X075"))
    )
    (comp (ref "C45")
      (value "4.7uF")
      (footprint "eagle-import:C0603")
      (libsource (lib "eagle-import") (part "rcl_334_C-EUC0603"))
    )
    (comp (ref "C46")
      (value "4.7uF")
      (footprint "eagle-import:C0603")
      (libsource (lib "eagle-import") (part "rcl_334_C-EUC0603"))
    )
    (comp (ref "C47")
      (value "5.6nF")
      (footprint "eagle-import:C050-025X075")
      (libsource (lib "eagle-import") (part "C-US050-025X075"))
    )
    (comp (ref "C48")
      (value "5.6nF")
      (footprint "eagle-import:C050-025X075")
      (libsource (lib "eagle-import") (part "C-US050-025X075"))
    )
    (comp (ref "C49")
      (value "100nF")
      (footprint "eagle-import:C0402")
      (libsource (lib "eagle-import") (part "rcl_334_C-EUC0402"))
    )
    (comp (ref "C50")
      (value "100nF")
      (footprint "eagle-import:C0402")
      (libsource (lib "eagle-import") (part "rcl_334_C-EUC0402"))
    )
    (comp (ref "C51")
      (value "2.7nF")
      (footprint "eagle-import:C050-025X075")
      (libsource (lib "eagle-import") (part "C-US050-025X075"))
    )
    (comp (ref "C52")
      (value "4.7uF")
      (footprint "eagle-import:C0603")
      (libsource (lib "eagle-import") (part "rcl_334_C-EUC0603"))
    )
    (comp (ref "C53")
      (value "4.7uF")
      (footprint "eagle-import:C0603")
      (libsource (lib "eagle-import") (part "rcl_334_C-EUC0603"))
    )
    (comp (ref "C54")
      (value "2.7nF")
      (footprint "eagle-import:C050-025X075")
      (libsource (lib "eagle-import") (part "C-US050-025X075"))
    )
    (comp (ref "C55")
      (value "100nF")
      (footprint "eagle-import:C0402")
      (libsource (lib "eagle-import") (part "rcl_334_C-EUC0402"))
    )
    (comp (ref "C56")
      (value "100nF")
      (footprint "eagle-import:C0402")
      (libsource (lib "eagle-import") (part "rcl_334_C-EUC0402"))
    )
    (comp (ref "C57")
      (value "3.9nF")
      (footprint "eagle-import:C050-025X075")
      (libsource (lib "eagle-import") (part "C-US050-025X075"))
    )
    (comp (ref "C58")
      (value "4.7uF")
      (footprint "eagle-import:C0603")
      (libsource (lib "eagle-import") (part "rcl_334_C-EUC0603"))
    )
    (comp (ref "C59")
      (value "4.7uF")
      (footprint "eagle-import:C0603")
      (libsource (lib "eagle-import") (part "rcl_334_C-EUC0603"))
    )
    (comp (ref "IC7")
      (value "AD797")
      (footprint "eagle-import:SO08")
      (libsource (lib "eagle-import") (part "AD797"))
    )
    (comp (ref "IC8")
      (value "AD797")
      (footprint "eagle-import:SO08")
      (libsource (lib "eagle-import") (part "AD797"))
    )
    (comp (ref "IC9")
      (value "AD797")
      (footprint "eagle-import:SO08")
      (libsource (lib "eagle-import") (part "AD797"))
    )
    (comp (ref "J3")
      (value "RCARCA")
      (footprint "eagle-import:RCA")
      (libsource (lib "eagle-import") (part "RCARCA"))
    )
    (comp (ref "R21")
      (value "2.21k")
      (footprint "eagle-import:R0402")
      (libsource (lib "eagle-import") (part "rcl_334_R-EU_R0402"))
    )
    (comp (ref "R22")
      (value "2.80k")
      (footprint "eagle-import:R0402")
      (libsource (lib "eagle-import") (part "rcl_334_R-EU_R0402"))
    )
    (comp (ref "R23")
      (value "2k")
      (footprint "eagle-import:R0402")
      (libsource (lib "eagle-import") (part "rcl_334_R-EU_R0402"))
    )
    (comp (ref "R24")
      (value "806")
      (footprint "eagle-import:R0402")
      (libsource (lib "eagle-import") (part "rcl_334_R-EU_R0402"))
    )
    (comp (ref "R25")
      (value "806")
      (footprint "eagle-import:R0402")
      (libsource (lib "eagle-import") (part "rcl_334_R-EU_R0402"))
    )
    (comp (ref "R26")
      (value "2k")
      (footprint "eagle-import:R0402")
      (libsource (lib "eagle-import") (part "rcl_334_R-EU_R0402"))
    )
    (comp (ref "R27")
      (value "100")
      (footprint "eagle-import:R0402")
      (libsource (lib "eagle-import") (part "rcl_334_R-EU_R0402"))
    )
    (comp (ref "R28")
      (value "100")
      (footprint "eagle-import:R0402")
      (libsource (lib "eagle-import") (part "rcl_334_R-EU_R0402"))
    )
    (comp (ref "R29")
      (value "2.0k")
      (footprint "eagle-import:R0402")
      (libsource (lib "eagle-import") (part "rcl_334_R-EU_R0402"))
    )
    (comp (ref "R30")
      (value "2.0k")
      (footprint "eagle-import:R0402")
      (libsource (lib "eagle-import") (part "rcl_334_R-EU_R0402"))
    )
    (comp (ref "R31")
      (value "681")
      (footprint "eagle-import:R0402")
      (libsource (lib "eagle-import") (part "rcl_334_R-EU_R0402"))
    )
    (comp (ref "R32")
      (value "681")
      (footprint "eagle-import:R0402")
      (libsource (lib "eagle-import") (part "rcl_334_R-EU_R0402"))
    )
    (comp (ref "R33")
      (value "226")
      (footprint "eagle-import:R0402")
      (libsource (lib "eagle-import") (part "rcl_334_R-EU_R0402"))
    )
    (comp (ref "R34")
      (value "226")
      (footprint "eagle-import:R0402")
      (libsource (lib "eagle-import") (part "rcl_334_R-EU_R0402"))
    )
    (comp (ref "R35")
      (value "324")
      (footprint "eagle-import:R0402")
      (libsource (lib "eagle-import") (part "rcl_334_R-EU_R0402"))
    )
    (comp (ref "R36")
      (value "324")
      (footprint "eagle-import:R0402")
      (libsource (lib "eagle-import") (part "rcl_334_R-EU_R0402"))
    )
    (comp (ref "R37")
      (value "100")
      (footprint "eagle-import:R0402")
      (libsource (lib "eagle-import") (part "rcl_334_R-EU_R0402"))
    )
    (comp (ref "R38")
      (value "332")
      (footprint "eagle-import:R0402")
      (libsource (lib "eagle-import") (part "rcl_334_R-EU_R0402"))
    )
    (comp (ref "C18")
      (value "10uF")
      (footprint "eagle-import:C0603")
      (libsource (lib "eagle-import") (part "rcl_334_C-EUC0603"))
    )
    (comp (ref "C19")
      (value "10uF")
      (footprint "eagle-import:C0603")
      (libsource (lib "eagle-import") (part "rcl_334_C-EUC0603"))
    )
    (comp (ref "C20")
      (value "100nF")
      (footprint "eagle-import:C0402")
      (libsource (lib "eagle-import") (part "rcl_334_C-EUC0402"))
    )
    (comp (ref "C21")
      (value "100nF")
      (footprint "eagle-import:C0402")
      (libsource (lib "eagle-import") (part "rcl_334_C-EUC0402"))
    )
    (comp (ref "C22")
      (value "10nF")
      (footprint "eagle-import:C0402")
      (libsource (lib "eagle-import") (part "rcl_334_C-EUC0402"))
    )
    (comp (ref "C23")
      (value "10nF")
      (footprint "eagle-import:C0402")
      (libsource (lib "eagle-import") (part "rcl_334_C-EUC0402"))
    )
    (comp (ref "C24")
      (value "100nF")
      (footprint "eagle-import:C0402")
      (libsource (lib "eagle-import") (part "rcl_334_C-EUC0402"))
    )
    (comp (ref "C25")
      (value "100nF")
      (footprint "eagle-import:C0402")
      (libsource (lib "eagle-import") (part "rcl_334_C-EUC0402"))
    )
    (comp (ref "C26")
      (value "10uF")
      (footprint "eagle-import:C0603")
      (libsource (lib "eagle-import") (part "rcl_334_C-EUC0603"))
    )
    (comp (ref "C27")
      (value "10uF")
      (footprint "eagle-import:C0603")
      (libsource (lib "eagle-import") (part "rcl_334_C-EUC0603"))
    )
    (comp (ref "C28")
      (value "10u")
      (footprint "eagle-import:B_3528-21W")
      (libsource (lib "eagle-import") (part "CPOL-EUB/3528-21W"))
    )
    (comp (ref "C29")
      (value "100nF")
      (footprint "eagle-import:C0402")
      (libsource (lib "eagle-import") (part "rcl_334_C-EUC0402"))
    )
    (comp (ref "C30")
      (value "100nF")
      (footprint "eagle-import:C0402")
      (libsource (lib "eagle-import") (part "rcl_334_C-EUC0402"))
    )
    (comp (ref "C31")
      (value "100nF")
      (footprint "eagle-import:C0402")
      (libsource (lib "eagle-import") (part "rcl_334_C-EUC0402"))
    )
    (comp (ref "C32")
      (value "100nF")
      (footprint "eagle-import:C0402")
      (libsource (lib "eagle-import") (part "rcl_334_C-EUC0402"))
    )
    (comp (ref "C33")
      (value "47u")
      (footprint "eagle-import:C_6032-28W")
      (libsource (lib "eagle-import") (part "CPOL-EUC/6032-28W"))
    )
    (comp (ref "GND")
      (value "TP")
      (footprint "eagle-import:TP_1")
      (libsource (lib "eagle-import") (part "TP"))
    )
    (comp (ref "IC4")
      (value "LP5907MFX-3.3")
      (footprint "eagle-import:TSOT23-5")
      (libsource (lib "eagle-import") (part "TLV700XX"))
    )
    (comp (ref "IC5")
      (value "LP5907MFX-3.3")
      (footprint "eagle-import:TSOT23-5")
      (libsource (lib "eagle-import") (part "TLV700XX"))
    )
    (comp (ref "IC6")
      (value "AD1955")
      (footprint "eagle-import:SSOP28")
      (libsource (lib "eagle-import") (part "AD1955"))
    )
    (comp (ref "L5")
      (value "600@100M")
      (footprint "eagle-import:R0805")
      (libsource (lib "eagle-import") (part "rcl_334_R-EU_R0805"))
    )
    (comp (ref "L6")
      (value "600@100M")
      (footprint "eagle-import:R0805")
      (libsource (lib "eagle-import") (part "rcl_334_R-EU_R0805"))
    )
    (comp (ref "L7")
      (value "600@100M")
      (footprint "eagle-import:R0805")
      (libsource (lib "eagle-import") (part "rcl_334_R-EU_R0805"))
    )
    (comp (ref "L8")
      (value "600@100M")
      (footprint "eagle-import:R0805")
      (libsource (lib "eagle-import") (part "rcl_334_R-EU_R0805"))
    )
    (comp (ref "R18")
      (value "2.49k")
      (footprint "eagle-import:R0402")
      (libsource (lib "eagle-import") (part "rcl_334_R-EU_R0402"))
    )
    (comp (ref "R20")
      (value "100k")
      (footprint "eagle-import:R0402")
      (libsource (lib "eagle-import") (part "rcl_334_R-EU_R0402"))
    )
    (comp (ref "C84")
      (value "100nF")
      (footprint "eagle-import:C0402")
      (libsource (lib "eagle-import") (part "rcl_334_C-EUC0402"))
    )
    (comp (ref "C85")
      (value "10uF")
      (footprint "eagle-import:C0603")
      (libsource (lib "eagle-import") (part "rcl_334_C-EUC0603"))
    )
    (comp (ref "C86")
      (value "10uF")
      (footprint "eagle-import:C0603")
      (libsource (lib "eagle-import") (part "rcl_334_C-EUC0603"))
    )
    (comp (ref "C87")
      (value "10uF")
      (footprint "eagle-import:C0603")
      (libsource (lib "eagle-import") (part "rcl_334_C-EUC0603"))
    )
    (comp (ref "C88")
      (value "100nF")
      (footprint "eagle-import:C0402")
      (libsource (lib "eagle-import") (part "rcl_334_C-EUC0402"))
    )
    (comp (ref "C89")
      (value "100nF")
      (footprint "eagle-import:C0402")
      (libsource (lib "eagle-import") (part "rcl_334_C-EUC0402"))
    )
    (comp (ref "C90")
      (value "100nF")
      (footprint "eagle-import:C0402")
      (libsource (lib "eagle-import") (part "rcl_334_C-EUC0402"))
    )
    (comp (ref "C91")
      (value "10uF")
      (footprint "eagle-import:C0603")
      (libsource (lib "eagle-import") (part "rcl_334_C-EUC0603"))
    )
    (comp (ref "C92")
      (value "100nF")
      (footprint "eagle-import:C0402")
      (libsource (lib "eagle-import") (part "rcl_334_C-EUC0402"))
    )
    (comp (ref "C93")
      (value "100nF")
      (footprint "eagle-import:C0402")
      (libsource (lib "eagle-import") (part "rcl_334_C-EUC0402"))
    )
    (comp (ref "C94")
      (value "100nF")
      (footprint "eagle-import:C0402")
      (libsource (lib "eagle-import") (part "rcl_334_C-EUC0402"))
    )
    (comp (ref "C95")
      (value "100nF")
      (footprint "eagle-import:C0402")
      (libsource (lib "eagle-import") (part "rcl_334_C-EUC0402"))
    )
    (comp (ref "C96")
      (value "100nF")
      (footprint "eagle-import:C0402")
      (libsource (lib "eagle-import") (part "rcl_334_C-EUC0402"))
    )
    (comp (ref "C97")
      (value "100nF")
      (footprint "eagle-import:C0402")
      (libsource (lib "eagle-import") (part "rcl_334_C-EUC0402"))
    )
    (comp (ref "C98")
      (value "100nF")
      (footprint "eagle-import:C0402")
      (libsource (lib "eagle-import") (part "rcl_334_C-EUC0402"))
    )
    (comp (ref "C99")
      (value "100nF")
      (footprint "eagle-import:C0402")
      (libsource (lib "eagle-import") (part "rcl_334_C-EUC0402"))
    )
    (comp (ref "C100")
      (value "10uF")
      (footprint "eagle-import:C0603")
      (libsource (lib "eagle-import") (part "rcl_334_C-EUC0603"))
    )
    (comp (ref "C101")
      (value "100nF")
      (footprint "eagle-import:C0402")
      (libsource (lib "eagle-import") (part "rcl_334_C-EUC0402"))
    )
    (comp (ref "C102")
      (value "100nF")
      (footprint "eagle-import:C0402")
      (libsource (lib "eagle-import") (part "rcl_334_C-EUC0402"))
    )
    (comp (ref "C138")
      (value "100nF")
      (footprint "eagle-import:C0402")
      (libsource (lib "eagle-import") (part "rcl_334_C-EUC0402"))
    )
    (comp (ref "C139")
      (value "100nF")
      (footprint "eagle-import:C0402")
      (libsource (lib "eagle-import") (part "rcl_334_C-EUC0402"))
    )
    (comp (ref "C141")
      (value "10nF")
      (footprint "eagle-import:C0402")
      (libsource (lib "eagle-import") (part "C-EUC0402"))
    )
    (comp (ref "C142")
      (value "10nF")
      (footprint "eagle-import:C0402")
      (libsource (lib "eagle-import") (part "C-EUC0402"))
    )
    (comp (ref "CUSB1")
      (value "4.7nF")
      (footprint "eagle-import:C0402")
      (libsource (lib "eagle-import") (part "rcl_334_C-EUC0402"))
    )
    (comp (ref "GND176")
      (value "TP")
      (footprint "eagle-import:TP_1")
      (libsource (lib "eagle-import") (part "TP"))
    )
    (comp (ref "IC13")
      (value "S34ML")
      (footprint "eagle-import:TSOP-48")
      (libsource (lib "eagle-import") (part "S34ML"))
    )
    (comp (ref "IC14")
      (value "TPS73801")
      (footprint "eagle-import:SOT223-6")
      (libsource (lib "eagle-import") (part "TPS73801"))
    )
    (comp (ref "IC15")
      (value "USBLC6-2SC6")
      (footprint "eagle-import:SOT23-6L")
      (libsource (lib "eagle-import") (part "USBLC6-2"))
    )
    (comp (ref "IC16")
      (value "PIC32MZ2048EFM100")
      (footprint "eagle-import:TQFP-100")
      (libsource (lib "eagle-import") (part "PIC32MZ2048EFM100"))
    )
    (comp (ref "IC18")
      (value "LP5907MFX-3.3")
      (footprint "eagle-import:TSOT23-5")
      (libsource (lib "eagle-import") (part "TLV700XX"))
    )
    (comp (ref "JP1")
      (value "M06NO_SILK")
      (footprint "eagle-import:1X06_NO_SILK")
      (libsource (lib "eagle-import") (part "M06NO_SILK"))
    )
    (comp (ref "L9")
      (value "600@100M")
      (footprint "eagle-import:R0805")
      (libsource (lib "eagle-import") (part "rcl_334_R-EU_R0805"))
    )
    (comp (ref "L13")
      (value "???")
      (footprint "eagle-import:R0805")
      (libsource (lib "eagle-import") (part "rcl_334_R-EU_R0805"))
    )
    (comp (ref "LED1")
      (value "RED")
      (footprint "eagle-import:LED_HAND")
      (libsource (lib "eagle-import") (part "LEDHAND"))
    )
    (comp (ref "LED2")
      (value "RED")
      (footprint "eagle-import:LED_HAND")
      (libsource (lib "eagle-import") (part "LEDHAND"))
    )
    (comp (ref "LED3")
      (value "RED")
      (footprint "eagle-import:LED_HAND")
      (libsource (lib "eagle-import") (part "LEDHAND"))
    )
    (comp (ref "OSC1")
      (value "OSCILLATOR")
      (footprint "eagle-import:OSCILLATOR_3.2X2.5")
      (libsource (lib "eagle-import") (part "OSCILLATOR"))
    )
    (comp (ref "OSC3")
      (value "OSCILLATOR")
      (footprint "eagle-import:OSCILLATOR_3.2X2.5")
      (libsource (lib "eagle-import") (part "OSCILLATOR"))
    )
    (comp (ref "R55")
      (value "3.16k")
      (footprint "eagle-import:R0402")
      (libsource (lib "eagle-import") (part "rcl_334_R-EU_R0402"))
    )
    (comp (ref "R56")
      (value "10k")
      (footprint "eagle-import:R0402")
      (libsource (lib "eagle-import") (part "rcl_334_R-EU_R0402"))
    )
    (comp (ref "R57")
      (value "1k")
      (footprint "eagle-import:R0402")
      (libsource (lib "eagle-import") (part "rcl_334_R-EU_R0402"))
    )
    (comp (ref "R60")
      (value "15k")
      (footprint "eagle-import:R0402")
      (libsource (lib "eagle-import") (part "R-EU_R0402"))
    )
    (comp (ref "R71")
      (value "15k")
      (footprint "eagle-import:R0402")
      (libsource (lib "eagle-import") (part "R-EU_R0402"))
    )
    (comp (ref "R74")
      (value "9.76k")
      (footprint "eagle-import:R0402")
      (libsource (lib "eagle-import") (part "rcl_334_R-EU_R0402"))
    )
    (comp (ref "R75")
      (value "2490")
      (footprint "eagle-import:R0402")
      (libsource (lib "eagle-import") (part "rcl_334_R-EU_R0402"))
    )
    (comp (ref "R76")
      (value "2490")
      (footprint "eagle-import:R0402")
      (libsource (lib "eagle-import") (part "rcl_334_R-EU_R0402"))
    )
    (comp (ref "R77")
      (value "2490")
      (footprint "eagle-import:R0402")
      (libsource (lib "eagle-import") (part "rcl_334_R-EU_R0402"))
    )
    (comp (ref "R80")
      (value "3.57k")
      (footprint "eagle-import:R0402")
      (libsource (lib "eagle-import") (part "rcl_334_R-EU_R0402"))
    )
    (comp (ref "RUSB1")
      (value "1M")
      (footprint "eagle-import:R0402")
      (libsource (lib "eagle-import") (part "rcl_334_R-EU_R0402"))
    )
    (comp (ref "SW1")
      (value "SW1\"")
      (footprint "eagle-import:SWITCH_KSS")
      (libsource (lib "eagle-import") (part "SW1{dblquote}"))
    )
    (comp (ref "TP0")
      (value "TP")
      (footprint "eagle-import:TP_1")
      (libsource (lib "eagle-import") (part "TP"))
    )
    (comp (ref "TP1")
      (value "TP")
      (footprint "eagle-import:TP_1")
      (libsource (lib "eagle-import") (part "TP"))
    )
    (comp (ref "USB1")
      (value "USB_MICRO_B")
      (footprint "eagle-import:ZX62D-B-5P8")
      (libsource (lib "eagle-import") (part "USB_MICRO_B"))
    )
    (comp (ref "C1")
      (value "2.2u")
      (footprint "eagle-import:C0603")
      (libsource (lib "eagle-import") (part "rcl_334_C-EUC0603"))
    )
    (comp (ref "C2")
      (value "68uF")
      (footprint "eagle-import:E2-5")
      (libsource (lib "eagle-import") (part "rcl_334_CPOL-EUE2-5"))
    )
    (comp (ref "C3")
      (value "1u")
      (footprint "eagle-import:C0402")
      (libsource (lib "eagle-import") (part "rcl_334_C-EUC0402"))
    )
    (comp (ref "C4")
      (value "1u")
      (footprint "eagle-import:C0603")
      (libsource (lib "eagle-import") (part "rcl_334_C-EUC0603"))
    )
    (comp (ref "C5")
      (value "2.2u")
      (footprint "eagle-import:C0603")
      (libsource (lib "eagle-import") (part "rcl_334_C-EUC0603"))
    )
    (comp (ref "C6")
      (value "1u")
      (footprint "eagle-import:C0603")
      (libsource (lib "eagle-import") (part "rcl_334_C-EUC0603"))
    )
    (comp (ref "C7")
      (value "820p")
      (footprint "eagle-import:C0402")
      (libsource (lib "eagle-import") (part "rcl_334_C-EUC0402"))
    )
    (comp (ref "C8")
      (value "47p")
      (footprint "eagle-import:C0402")
      (libsource (lib "eagle-import") (part "rcl_334_C-EUC0402"))
    )
    (comp (ref "C9")
      (value "2.2u")
      (footprint "eagle-import:C0603")
      (libsource (lib "eagle-import") (part "rcl_334_C-EUC0603"))
    )
    (comp (ref "C10")
      (value "68p")
      (footprint "eagle-import:C0402")
      (libsource (lib "eagle-import") (part "rcl_334_C-EUC0402"))
    )
    (comp (ref "C11")
      (value "10u")
      (footprint "eagle-import:C1206")
      (libsource (lib "eagle-import") (part "rcl_334_C-EUC1206"))
    )
    (comp (ref "C12")
      (value "6.8n")
      (footprint "eagle-import:C0402")
      (libsource (lib "eagle-import") (part "rcl_334_C-EUC0402"))
    )
    (comp (ref "C13")
      (value "1u")
      (footprint "eagle-import:C0603")
      (libsource (lib "eagle-import") (part "rcl_334_C-EUC0603"))
    )
    (comp (ref "C14")
      (value "1u")
      (footprint "eagle-import:C0402")
      (libsource (lib "eagle-import") (part "rcl_334_C-EUC0402"))
    )
    (comp (ref "C15")
      (value "100n")
      (footprint "eagle-import:C0402")
      (libsource (lib "eagle-import") (part "rcl_334_C-EUC0402"))
    )
    (comp (ref "C16")
      (value "2.2u")
      (footprint "eagle-import:C0603")
      (libsource (lib "eagle-import") (part "rcl_334_C-EUC0603"))
    )
    (comp (ref "C17")
      (value "1u")
      (footprint "eagle-import:C0603")
      (libsource (lib "eagle-import") (part "rcl_334_C-EUC0603"))
    )
    (comp (ref "C137")
      (value "1u")
      (footprint "eagle-import:C0402")
      (libsource (lib "eagle-import") (part "rcl_334_C-EUC0402"))
    )
    (comp (ref "C148")
      (value "1u")
      (footprint "eagle-import:C0603")
      (libsource (lib "eagle-import") (part "rcl_334_C-EUC0603"))
    )
    (comp (ref "C149")
      (value "1u")
      (footprint "eagle-import:C0603")
      (libsource (lib "eagle-import") (part "rcl_334_C-EUC0603"))
    )
    (comp (ref "D1")
      (value "DIODE")
      (footprint "eagle-import:SOD-323-DIODE")
      (libsource (lib "eagle-import") (part "DIODE"))
    )
    (comp (ref "D2")
      (value "DIODE")
      (footprint "eagle-import:SOD-323-DIODE")
      (libsource (lib "eagle-import") (part "DIODE"))
    )
    (comp (ref "IC1")
      (value "ADP7118")
      (footprint "eagle-import:TSOT23-5")
      (libsource (lib "eagle-import") (part "ADP7118"))
    )
    (comp (ref "IC2")
      (value "ADP5070EP")
      (footprint "eagle-import:TSSOP-EP-20")
      (libsource (lib "eagle-import") (part "ADP5070EP"))
    )
    (comp (ref "IC3")
      (value "ADP7182")
      (footprint "eagle-import:TSOT23-5")
      (libsource (lib "eagle-import") (part "ADP7182"))
    )
    (comp (ref "JACK")
      (value "DC_JACK2.1MM")
      (footprint "eagle-import:DC_POWER_INPUT_2.1MM")
      (libsource (lib "eagle-import") (part "DC_JACK2.1MM"))
    )
    (comp (ref "L1")
      (value "1.5u")
      (footprint "eagle-import:IND_LPS4012_V2")
      (libsource (lib "eagle-import") (part "INDLPS4012_L"))
    )
    (comp (ref "L2")
      (value "INDLPS6225_L")
      (footprint "eagle-import:IND_LPS6225_V2")
      (libsource (lib "eagle-import") (part "INDLPS6225_L"))
    )
    (comp (ref "L3")
      (value "INDLPS6225_L")
      (footprint "eagle-import:IND_LPS6225_V2")
      (libsource (lib "eagle-import") (part "INDLPS6225_L"))
    )
    (comp (ref "L4")
      (value "1.5u")
      (footprint "eagle-import:IND_LPS4012_V2")
      (libsource (lib "eagle-import") (part "INDLPS4012_L"))
    )
    (comp (ref "R1")
      (value "180k")
      (footprint "eagle-import:R0402")
      (libsource (lib "eagle-import") (part "rcl_334_R-EU_R0402"))
    )
    (comp (ref "R2")
      (value "180k")
      (footprint "eagle-import:R0402")
      (libsource (lib "eagle-import") (part "rcl_334_R-EU_R0402"))
    )
    (comp (ref "R3")
      (value "10k")
      (footprint "eagle-import:R0402")
      (libsource (lib "eagle-import") (part "rcl_334_R-EU_R0402"))
    )
    (comp (ref "R4")
      (value "10k")
      (footprint "eagle-import:R0402")
      (libsource (lib "eagle-import") (part "rcl_334_R-EU_R0402"))
    )
    (comp (ref "R5")
      (value "6.04")
      (footprint "eagle-import:R0402")
      (libsource (lib "eagle-import") (part "rcl_334_R-EU_R0402"))
    )
    (comp (ref "R6")
      (value "63.4k")
      (footprint "eagle-import:R0402")
      (libsource (lib "eagle-import") (part "rcl_334_R-EU_R0402"))
    )
    (comp (ref "R7")
      (value "3.57k")
      (footprint "eagle-import:R0402")
      (libsource (lib "eagle-import") (part "rcl_334_R-EU_R0402"))
    )
    (comp (ref "R8")
      (value "8.45k")
      (footprint "eagle-import:R0402")
      (libsource (lib "eagle-import") (part "rcl_334_R-EU_R0402"))
    )
    (comp (ref "R9")
      (value "100k")
      (footprint "eagle-import:R0402")
      (libsource (lib "eagle-import") (part "rcl_334_R-EU_R0402"))
    )
    (comp (ref "R10")
      (value "2.8k")
      (footprint "eagle-import:R0402")
      (libsource (lib "eagle-import") (part "rcl_334_R-EU_R0402"))
    )
    (comp (ref "R11")
      (value "150k")
      (footprint "eagle-import:R0402")
      (libsource (lib "eagle-import") (part "rcl_334_R-EU_R0402"))
    )
    (comp (ref "R12")
      (value "54.9k")
      (footprint "eagle-import:R0402")
      (libsource (lib "eagle-import") (part "rcl_334_R-EU_R0402"))
    )
    (comp (ref "R13")
      (value "5.76k")
      (footprint "eagle-import:R0402")
      (libsource (lib "eagle-import") (part "rcl_334_R-EU_R0402"))
    )
    (comp (ref "R14")
      (value "215k")
      (footprint "eagle-import:R0402")
      (libsource (lib "eagle-import") (part "rcl_334_R-EU_R0402"))
    )
    (comp (ref "R15")
      (value "10k")
      (footprint "eagle-import:R0402")
      (libsource (lib "eagle-import") (part "rcl_334_R-EU_R0402"))
    )
    (comp (ref "R16")
      (value "10k")
      (footprint "eagle-import:R0402")
      (libsource (lib "eagle-import") (part "rcl_334_R-EU_R0402"))
    )
    (comp (ref "R17")
      (value "5.36")
      (footprint "eagle-import:R0402")
      (libsource (lib "eagle-import") (part "rcl_334_R-EU_R0402"))
    )
    (comp (ref "R78")
      (value "100k")
      (footprint "eagle-import:R0402")
      (libsource (lib "eagle-import") (part "rcl_334_R-EU_R0402"))
    )
    (comp (ref "R79")
      (value "100k")
      (footprint "eagle-import:R0402")
      (libsource (lib "eagle-import") (part "rcl_334_R-EU_R0402"))
    )
    (comp (ref "R87")
      (value "100k")
      (footprint "eagle-import:R0402")
      (libsource (lib "eagle-import") (part "rcl_334_R-EU_R0402"))
    )
    (comp (ref "R88")
      (value "100k")
      (footprint "eagle-import:R0402")
      (libsource (lib "eagle-import") (part "rcl_334_R-EU_R0402"))
    )
  )
  (nets
    (net (code "1") (name "+12V") (class "Default")
      (node (ref "C3") (pin "2") (pinfunction "2_2") (pintype "passive"))
      (node (ref "C36") (pin "1") (pinfunction "1_1") (pintype "passive"))
      (node (ref "C37") (pin "2") (pinfunction "2_2") (pintype "passive"))
      (node (ref "C41") (pin "1") (pinfunction "1_1") (pintype "passive"))
      (node (ref "C46") (pin "1") (pinfunction "1_1") (pintype "passive"))
      (node (ref "C49") (pin "1") (pinfunction "1_1") (pintype "passive"))
      (node (ref "C5") (pin "1") (pinfunction "1_1") (pintype "passive"))
      (node (ref "C52") (pin "1") (pinfunction "1_1") (pintype "passive"))
      (node (ref "C55") (pin "1") (pinfunction "1_1") (pintype "passive"))
      (node (ref "C58") (pin "1") (pinfunction "1_1") (pintype "passive"))
      (node (ref "C60") (pin "1") (pinfunction "1_1") (pintype "passive"))
      (node (ref "C61") (pin "2") (pinfunction "2_2") (pintype "passive"))
      (node (ref "C65") (pin "1") (pinfunction "1_1") (pintype "passive"))
      (node (ref "C69") (pin "1") (pinfunction "1_1") (pintype "passive"))
      (node (ref "C73") (pin "1") (pinfunction "1_1") (pintype "passive"))
      (node (ref "C76") (pin "1") (pinfunction "1_1") (pintype "passive"))
      (node (ref "C79") (pin "1") (pinfunction "1_1") (pintype "passive"))
      (node (ref "C82") (pin "1") (pinfunction "1_1") (pintype "passive"))
      (node (ref "IC1") (pin "5") (pinfunction "OUT_5") (pintype "bidirectional"))
      (node (ref "IC10") (pin "7") (pinfunction "V+_7") (pintype "power_in"))
      (node (ref "IC11") (pin "7") (pinfunction "V+_7") (pintype "power_in"))
      (node (ref "IC12") (pin "7") (pinfunction "V+_7") (pintype "power_in"))
      (node (ref "IC7") (pin "7") (pinfunction "V+_7") (pintype "power_in"))
      (node (ref "IC8") (pin "7") (pinfunction "V+_7") (pintype "power_in"))
      (node (ref "IC9") (pin "7") (pinfunction "V+_7") (pintype "power_in"))
      (node (ref "R1") (pin "1") (pinfunction "1_1") (pintype "passive"))
      (node (ref "R2") (pin "1") (pinfunction "1_1") (pintype "passive"))
      (node (ref "R23") (pin "2") (pinfunction "2_2") (pintype "passive"))
      (node (ref "R26") (pin "2") (pinfunction "2_2") (pintype "passive"))
      (node (ref "R39") (pin "2") (pinfunction "2_2") (pintype "passive"))
      (node (ref "R42") (pin "2") (pinfunction "2_2") (pintype "passive"))
    )
    (net (code "2") (name "+15V") (class "Default")
      (node (ref "C1") (pin "1") (pinfunction "1_1") (pintype "passive"))
      (node (ref "C4") (pin "1") (pinfunction "1_1") (pintype "passive"))
      (node (ref "IC1") (pin "1") (pinfunction "IN_1") (pintype "bidirectional"))
      (node (ref "L1") (pin "1") (pinfunction "1_1") (pintype "passive"))
      (node (ref "R5") (pin "2") (pinfunction "2_2") (pintype "passive"))
      (node (ref "R6") (pin "2") (pinfunction "2_2") (pintype "passive"))
    )
    (net (code "3") (name "-12V") (class "Default")
      (node (ref "C15") (pin "2") (pinfunction "2_2") (pintype "passive"))
      (node (ref "C16") (pin "1") (pinfunction "1_1") (pintype "passive"))
      (node (ref "C42") (pin "2") (pinfunction "2_2") (pintype "passive"))
      (node (ref "C45") (pin "2") (pinfunction "2_2") (pintype "passive"))
      (node (ref "C50") (pin "2") (pinfunction "2_2") (pintype "passive"))
      (node (ref "C53") (pin "2") (pinfunction "2_2") (pintype "passive"))
      (node (ref "C56") (pin "2") (pinfunction "2_2") (pintype "passive"))
      (node (ref "C59") (pin "2") (pinfunction "2_2") (pintype "passive"))
      (node (ref "C66") (pin "2") (pinfunction "2_2") (pintype "passive"))
      (node (ref "C70") (pin "2") (pinfunction "2_2") (pintype "passive"))
      (node (ref "C74") (pin "2") (pinfunction "2_2") (pintype "passive"))
      (node (ref "C77") (pin "2") (pinfunction "2_2") (pintype "passive"))
      (node (ref "C80") (pin "2") (pinfunction "2_2") (pintype "passive"))
      (node (ref "C83") (pin "2") (pinfunction "2_2") (pintype "passive"))
      (node (ref "IC10") (pin "4") (pinfunction "V-_4") (pintype "power_in"))
      (node (ref "IC11") (pin "4") (pinfunction "V-_4") (pintype "power_in"))
      (node (ref "IC12") (pin "4") (pinfunction "V-_4") (pintype "power_in"))
      (node (ref "IC3") (pin "5") (pinfunction "OUT_5") (pintype "bidirectional"))
      (node (ref "IC7") (pin "4") (pinfunction "V-_4") (pintype "power_in"))
      (node (ref "IC8") (pin "4") (pinfunction "V-_4") (pintype "power_in"))
      (node (ref "IC9") (pin "4") (pinfunction "V-_4") (pintype "power_in"))
      (node (ref "R11") (pin "1") (pinfunction "1_1") (pintype "passive"))
      (node (ref "R14") (pin "1") (pinfunction "1_1") (pintype "passive"))
    )
    (net (code "4") (name "-15V") (class "Default")
      (node (ref "C17") (pin "1") (pinfunction "1_1") (pintype "passive"))
      (node (ref "C9") (pin "1") (pinfunction "1_1") (pintype "passive"))
      (node (ref "IC3") (pin "2") (pinfunction "IN_2") (pintype "bidirectional"))
      (node (ref "L4") (pin "2") (pinfunction "2_2") (pintype "passive"))
      (node (ref "R12") (pin "1") (pinfunction "1_1") (pintype "passive"))
      (node (ref "R17") (pin "1") (pinfunction "1_1") (pintype "passive"))
    )
    (net (code "5") (name "A5V0") (class "Default")
      (node (ref "C18") (pin "2") (pinfunction "2_2") (pintype "passive"))
      (node (ref "C20") (pin "2") (pinfunction "2_2") (pintype "passive"))
      (node (ref "IC4") (pin "5") (pinfunction "OUT_5") (pintype "bidirectional"))
      (node (ref "L8") (pin "1") (pinfunction "1_1") (pintype "passive"))
      (node (ref "R21") (pin "2") (pinfunction "2_2") (pintype "passive"))
    )
    (net (code "6") (name "ADC0") (class "Default")
      (node (ref "C144") (pin "2") (pinfunction "2_2") (pintype "passive"))
      (node (ref "R60") (pin "1") (pinfunction "1_1") (pintype "passive"))
      (node (ref "R62") (pin "1") (pinfunction "1_1") (pintype "passive"))
      (node (ref "R81") (pin "2") (pinfunction "2_2") (pintype "passive"))
    )
    (net (code "7") (name "ADC0_EZ") (class "Default")
      (node (ref "C141") (pin "1") (pinfunction "1_1") (pintype "passive"))
      (node (ref "IC16") (pin "41") (pinfunction "EBIA11/AN7/ERXD0/AECRS/PMA11/RB12_41") (pintype "bidirectional"))
      (node (ref "R60") (pin "2") (pinfunction "2_2") (pintype "passive"))
    )
    (net (code "8") (name "ADC0_IN") (class "Default")
      (node (ref "R83") (pin "2") (pinfunction "2_2") (pintype "passive"))
      (node (ref "X1") (pin "P2") (pinfunction "2_P2") (pintype "passive"))
    )
    (net (code "9") (name "ADC1") (class "Default")
      (node (ref "C145") (pin "2") (pinfunction "2_2") (pintype "passive"))
      (node (ref "R19") (pin "1") (pinfunction "1_1") (pintype "passive"))
      (node (ref "R71") (pin "1") (pinfunction "1_1") (pintype "passive"))
      (node (ref "R82") (pin "2") (pinfunction "2_2") (pintype "passive"))
    )
    (net (code "10") (name "ADC1_EZ") (class "Default")
      (node (ref "C142") (pin "1") (pinfunction "1_1") (pintype "passive"))
      (node (ref "IC16") (pin "42") (pinfunction "AN8/ERXD1/AECOL/RB13_42") (pintype "bidirectional"))
      (node (ref "R71") (pin "2") (pinfunction "2_2") (pintype "passive"))
    )
    (net (code "11") (name "ADC1_IN") (class "Default")
      (node (ref "R85") (pin "2") (pinfunction "2_2") (pintype "passive"))
      (node (ref "X1") (pin "P1") (pinfunction "1_P1") (pintype "passive"))
    )
    (net (code "12") (name "ALE") (class "Default")
      (node (ref "IC13") (pin "P17") (pinfunction "ALE_P17") (pintype "bidirectional"))
      (node (ref "IC16") (pin "11") (pinfunction "EBIA4/AN13/C1INC/ECRS/RPG7/SDA4/PMA4..._11") (pintype "bidirectional"))
    )
    (net (code "13") (name "AUDIO") (class "Default")
      (node (ref "IC16") (pin "86") (pinfunction "EBID10/ETXD0/RPF1/PMD10/RF1_86") (pintype "bidirectional"))
      (node (ref "R76") (pin "2") (pinfunction "2_2") (pintype "passive"))
    )
    (net (code "14") (name "BUSY") (class "Default")
      (node (ref "IC13") (pin "P7") (pinfunction "R/B#_P7") (pintype "bidirectional"))
      (node (ref "IC16") (pin "16") (pinfunction "EBIA2/AN11/C2INC/ERXCLK/EREFCLK..._16") (pintype "bidirectional"))
      (node (ref "R80") (pin "1") (pinfunction "1_1") (pintype "passive"))
    )
    (net (code "15") (name "CE") (class "Default")
      (node (ref "IC13") (pin "P9") (pinfunction "CE#_P9") (pintype "bidirectional"))
      (node (ref "IC16") (pin "79") (pinfunction "EBID12/ETXD2/RPD12..._79") (pintype "bidirectional"))
    )
    (net (code "16") (name "CLE") (class "Default")
      (node (ref "IC13") (pin "P16") (pinfunction "CLE_P16") (pintype "bidirectional"))
      (node (ref "IC16") (pin "80") (pinfunction "EBID13/ETXD3/PMD13/RD13_80") (pintype "bidirectional"))
    )
    (net (code "17") (name "CLK_IN") (class "Default")
      (node (ref "CLKIN") (pin "4") (pinfunction "4_4") (pintype "passive"))
      (node (ref "IC22") (pin "2") (pinfunction "P$2_2") (pintype "bidirectional"))
    )
    (net (code "18") (name "CLK_SYNC") (class "Default")
      (node (ref "IC22") (pin "4") (pinfunction "P$4_4") (pintype "bidirectional"))
      (node (ref "IC25") (pin "12") (pinfunction "PC2/OC0C/RXD0_12") (pintype "bidirectional"))
    )
    (net (code "19") (name "CTS") (class "Default")
      (node (ref "IC21") (pin "11") (pinfunction "B4_11") (pintype "bidirectional"))
      (node (ref "IC25") (pin "29") (pinfunction "~XCK0OC0BSCLPE1_29") (pintype "bidirectional"))
    )
    (net (code "20") (name "D+") (class "Default")
      (node (ref "IC15") (pin "P$4") (pinfunction "IO2_P$4") (pintype "bidirectional"))
      (node (ref "IC16") (pin "55") (pinfunction "D+_55") (pintype "bidirectional"))
    )
    (net (code "21") (name "D-") (class "Default")
      (node (ref "IC15") (pin "P$6") (pinfunction "IO1_P$6") (pintype "bidirectional"))
      (node (ref "IC16") (pin "54") (pinfunction "D-_54") (pintype "bidirectional"))
    )
    (net (code "22") (name "D5V") (class "Default")
      (node (ref "C115") (pin "1") (pinfunction "1_1") (pintype "passive"))
      (node (ref "C85") (pin "1") (pinfunction "1_1") (pintype "passive"))
      (node (ref "C87") (pin "1") (pinfunction "1_1") (pintype "passive"))
      (node (ref "IC14") (pin "P$2") (pinfunction "OUT_P$2") (pintype "bidirectional"))
      (node (ref "IC18") (pin "1") (pinfunction "IN_1") (pintype "bidirectional"))
      (node (ref "IC18") (pin "3") (pinfunction "EN_3") (pintype "bidirectional"))
      (node (ref "IC20") (pin "1") (pinfunction "IN_1") (pintype "bidirectional"))
      (node (ref "IC20") (pin "3") (pinfunction "EN_3") (pintype "bidirectional"))
      (node (ref "JP2") (pin "1") (pinfunction "1_1") (pintype "passive"))
      (node (ref "R74") (pin "2") (pinfunction "2_2") (pintype "passive"))
      (node (ref "X1") (pin "P4") (pinfunction "4_P4") (pintype "passive"))
    )
    (net (code "23") (name "D5V0") (class "Default")
      (node (ref "C19") (pin "2") (pinfunction "2_2") (pintype "passive"))
      (node (ref "C21") (pin "2") (pinfunction "2_2") (pintype "passive"))
      (node (ref "IC5") (pin "5") (pinfunction "OUT_5") (pintype "bidirectional"))
      (node (ref "L7") (pin "1") (pinfunction "1_1") (pintype "passive"))
    )
    (net (code "24") (name "DAC_~{RST}") (class "Default")
      (node (ref "IC16") (pin "65") (pinfunction "EBIA8/RPF5/SCL5/PMA8/RF5_65") (pintype "bidirectional"))
      (node (ref "IC6") (pin "P23") (pinfunction "~{PD/RST}_P23") (pintype "bidirectional"))
      (node (ref "R20") (pin "1") (pinfunction "1_1") (pintype "passive"))
    )
    (net (code "25") (name "EN_DCDC") (class "Default")
      (node (ref "IC2") (pin "11") (pinfunction "EN2_11") (pintype "bidirectional"))
      (node (ref "IC2") (pin "9") (pinfunction "EN1_9") (pintype "bidirectional"))
      (node (ref "IC25") (pin "24") (pinfunction "~{#SSPD4}_24") (pintype "bidirectional"))
      (node (ref "R9") (pin "1") (pinfunction "1_1") (pintype "passive"))
    )
    (net (code "26") (name "EN_N12V") (class "Default")
      (node (ref "IC16") (pin "77") (pinfunction "EBID14/ETXEN/RPD2..._77") (pintype "bidirectional"))
      (node (ref "R88") (pin "1") (pinfunction "1_1") (pintype "passive"))
    )
    (net (code "27") (name "EN_P12V") (class "Default")
      (node (ref "IC16") (pin "76") (pinfunction "RPD1/SCK1/RD1_76") (pintype "bidirectional"))
      (node (ref "R87") (pin "1") (pinfunction "1_1") (pintype "passive"))
    )
    (net (code "28") (name "FILTB") (class "Default")
      (node (ref "C28") (pin "+") (pinfunction "+_+") (pintype "passive"))
      (node (ref "C32") (pin "1") (pinfunction "1_1") (pintype "passive"))
      (node (ref "IC6") (pin "P16") (pinfunction "FILTB_P16") (pintype "bidirectional"))
    )
    (net (code "29") (name "FT_CTS") (class "Default")
      (node (ref "IC19") (pin "11") (pinfunction "~{CTS}_11") (pintype "input"))
      (node (ref "IC21") (pin "6") (pinfunction "A4_6") (pintype "bidirectional"))
    )
    (net (code "30") (name "FT_RTS") (class "Default")
      (node (ref "IC19") (pin "3") (pinfunction "~{RTS}_3") (pintype "output"))
      (node (ref "IC21") (pin "4") (pinfunction "A2_4") (pintype "bidirectional"))
    )
    (net (code "31") (name "FT_RXD") (class "Default")
      (node (ref "IC19") (pin "5") (pinfunction "RXD_5") (pintype "input"))
      (node (ref "IC21") (pin "5") (pinfunction "A3_5") (pintype "bidirectional"))
    )
    (net (code "32") (name "FT_TXD") (class "Default")
      (node (ref "IC19") (pin "1") (pinfunction "TXD_1") (pintype "output"))
      (node (ref "IC21") (pin "3") (pinfunction "A1_3") (pintype "bidirectional"))
    )
    (net (code "33") (name "GND") (class "Default")
      (node (ref "C1") (pin "2") (pinfunction "2_2") (pintype "passive"))
      (node (ref "C10") (pin "2") (pinfunction "2_2") (pintype "passive"))
      (node (ref "C100") (pin "2") (pinfunction "2_2") (pintype "passive"))
      (node (ref "C101") (pin "2") (pinfunction "2_2") (pintype "passive"))
      (node (ref "C102") (pin "2") (pinfunction "2_2") (pintype "passive"))
      (node (ref "C104") (pin "2") (pinfunction "2_2") (pintype "passive"))
      (node (ref "C105") (pin "2") (pinfunction "2_2") (pintype "passive"))
      (node (ref "C11") (pin "2") (pinfunction "2_2") (pintype "passive"))
      (node (ref "C115") (pin "2") (pinfunction "2_2") (pintype "passive"))
      (node (ref "C116") (pin "2") (pinfunction "2_2") (pintype "passive"))
      (node (ref "C118") (pin "2") (pinfunction "2_2") (pintype "passive"))
      (node (ref "C119") (pin "2") (pinfunction "2_2") (pintype "passive"))
      (node (ref "C12") (pin "2") (pinfunction "2_2") (pintype "passive"))
      (node (ref "C120") (pin "2") (pinfunction "2_2") (pintype "passive"))
      (node (ref "C121") (pin "2") (pinfunction "2_2") (pintype "passive"))
      (node (ref "C122") (pin "2") (pinfunction "2_2") (pintype "passive"))
      (node (ref "C123") (pin "2") (pinfunction "2_2") (pintype "passive"))
      (node (ref "C126") (pin "2") (pinfunction "2_2") (pintype "passive"))
      (node (ref "C127") (pin "2") (pinfunction "2_2") (pintype "passive"))
      (node (ref "C128") (pin "2") (pinfunction "2_2") (pintype "passive"))
      (node (ref "C13") (pin "2") (pinfunction "2_2") (pintype "passive"))
      (node (ref "C130") (pin "2") (pinfunction "2_2") (pintype "passive"))
      (node (ref "C131") (pin "2") (pinfunction "2_2") (pintype "passive"))
      (node (ref "C132") (pin "2") (pinfunction "2_2") (pintype "passive"))
      (node (ref "C133") (pin "2") (pinfunction "2_2") (pintype "passive"))
      (node (ref "C134") (pin "2") (pinfunction "2_2") (pintype "passive"))
      (node (ref "C135") (pin "2") (pinfunction "2_2") (pintype "passive"))
      (node (ref "C136") (pin "2") (pinfunction "2_2") (pintype "passive"))
      (node (ref "C137") (pin "2") (pinfunction "2_2") (pintype "passive"))
      (node (ref "C138") (pin "2") (pinfunction "2_2") (pintype "passive"))
      (node (ref "C139") (pin "2") (pinfunction "2_2") (pintype "passive"))
      (node (ref "C14") (pin "2") (pinfunction "2_2") (pintype "passive"))
      (node (ref "C140") (pin "2") (pinfunction "2_2") (pintype "passive"))
      (node (ref "C141") (pin "2") (pinfunction "2_2") (pintype "passive"))
      (node (ref "C142") (pin "2") (pinfunction "2_2") (pintype "passive"))
      (node (ref "C143") (pin "2") (pinfunction "2_2") (pintype "passive"))
      (node (ref "C144") (pin "1") (pinfunction "1_1") (pintype "passive"))
      (node (ref "C145") (pin "1") (pinfunction "1_1") (pintype "passive"))
      (node (ref "C146") (pin "2") (pinfunction "2_2") (pintype "passive"))
      (node (ref "C147") (pin "2") (pinfunction "2_2") (pintype "passive"))
      (node (ref "C148") (pin "2") (pinfunction "2_2") (pintype "passive"))
      (node (ref "C149") (pin "2") (pinfunction "2_2") (pintype "passive"))
      (node (ref "C16") (pin "2") (pinfunction "2_2") (pintype "passive"))
      (node (ref "C17") (pin "2") (pinfunction "2_2") (pintype "passive"))
      (node (ref "C18") (pin "1") (pinfunction "1_1") (pintype "passive"))
      (node (ref "C19") (pin "1") (pinfunction "1_1") (pintype "passive"))
      (node (ref "C2") (pin "-") (pinfunction "-_-") (pintype "passive"))
      (node (ref "C20") (pin "1") (pinfunction "1_1") (pintype "passive"))
      (node (ref "C21") (pin "1") (pinfunction "1_1") (pintype "passive"))
      (node (ref "C22") (pin "1") (pinfunction "1_1") (pintype "passive"))
      (node (ref "C23") (pin "1") (pinfunction "1_1") (pintype "passive"))
      (node (ref "C24") (pin "1") (pinfunction "1_1") (pintype "passive"))
      (node (ref "C25") (pin "1") (pinfunction "1_1") (pintype "passive"))
      (node (ref "C26") (pin "1") (pinfunction "1_1") (pintype "passive"))
      (node (ref "C27") (pin "1") (pinfunction "1_1") (pintype "passive"))
      (node (ref "C28") (pin "-") (pinfunction "-_-") (pintype "passive"))
      (node (ref "C29") (pin "2") (pinfunction "2_2") (pintype "passive"))
      (node (ref "C30") (pin "2") (pinfunction "2_2") (pintype "passive"))
      (node (ref "C31") (pin "2") (pinfunction "2_2") (pintype "passive"))
      (node (ref "C32") (pin "2") (pinfunction "2_2") (pintype "passive"))
      (node (ref "C33") (pin "-") (pinfunction "-_-") (pintype "passive"))
      (node (ref "C34") (pin "2") (pinfunction "2_2") (pintype "passive"))
      (node (ref "C35") (pin "-") (pinfunction "-_-") (pintype "passive"))
      (node (ref "C36") (pin "2") (pinfunction "2_2") (pintype "passive"))
      (node (ref "C37") (pin "1") (pinfunction "1_1") (pintype "passive"))
      (node (ref "C39") (pin "2") (pinfunction "2_2") (pintype "passive"))
      (node (ref "C4") (pin "2") (pinfunction "2_2") (pintype "passive"))
      (node (ref "C40") (pin "2") (pinfunction "2_2") (pintype "passive"))
      (node (ref "C41") (pin "2") (pinfunction "2_2") (pintype "passive"))
      (node (ref "C42") (pin "1") (pinfunction "1_1") (pintype "passive"))
      (node (ref "C45") (pin "1") (pinfunction "1_1") (pintype "passive"))
      (node (ref "C46") (pin "2") (pinfunction "2_2") (pintype "passive"))
      (node (ref "C47") (pin "2") (pinfunction "2_2") (pintype "passive"))
      (node (ref "C48") (pin "2") (pinfunction "2_2") (pintype "passive"))
      (node (ref "C49") (pin "2") (pinfunction "2_2") (pintype "passive"))
      (node (ref "C5") (pin "2") (pinfunction "2_2") (pintype "passive"))
      (node (ref "C50") (pin "1") (pinfunction "1_1") (pintype "passive"))
      (node (ref "C51") (pin "2") (pinfunction "2_2") (pintype "passive"))
      (node (ref "C52") (pin "2") (pinfunction "2_2") (pintype "passive"))
      (node (ref "C53") (pin "1") (pinfunction "1_1") (pintype "passive"))
      (node (ref "C55") (pin "2") (pinfunction "2_2") (pintype "passive"))
      (node (ref "C56") (pin "1") (pinfunction "1_1") (pintype "passive"))
      (node (ref "C57") (pin "2") (pinfunction "2_2") (pintype "passive"))
      (node (ref "C58") (pin "2") (pinfunction "2_2") (pintype "passive"))
      (node (ref "C59") (pin "1") (pinfunction "1_1") (pintype "passive"))
      (node (ref "C6") (pin "2") (pinfunction "2_2") (pintype "passive"))
      (node (ref "C60") (pin "2") (pinfunction "2_2") (pintype "passive"))
      (node (ref "C61") (pin "1") (pinfunction "1_1") (pintype "passive"))
      (node (ref "C63") (pin "2") (pinfunction "2_2") (pintype "passive"))
      (node (ref "C64") (pin "2") (pinfunction "2_2") (pintype "passive"))
      (node (ref "C65") (pin "2") (pinfunction "2_2") (pintype "passive"))
      (node (ref "C66") (pin "1") (pinfunction "1_1") (pintype "passive"))
      (node (ref "C69") (pin "2") (pinfunction "2_2") (pintype "passive"))
      (node (ref "C7") (pin "2") (pinfunction "2_2") (pintype "passive"))
      (node (ref "C70") (pin "1") (pinfunction "1_1") (pintype "passive"))
      (node (ref "C71") (pin "2") (pinfunction "2_2") (pintype "passive"))
      (node (ref "C72") (pin "2") (pinfunction "2_2") (pintype "passive"))
      (node (ref "C73") (pin "2") (pinfunction "2_2") (pintype "passive"))
      (node (ref "C74") (pin "1") (pinfunction "1_1") (pintype "passive"))
      (node (ref "C75") (pin "2") (pinfunction "2_2") (pintype "passive"))
      (node (ref "C76") (pin "2") (pinfunction "2_2") (pintype "passive"))
      (node (ref "C77") (pin "1") (pinfunction "1_1") (pintype "passive"))
      (node (ref "C79") (pin "2") (pinfunction "2_2") (pintype "passive"))
      (node (ref "C8") (pin "2") (pinfunction "2_2") (pintype "passive"))
      (node (ref "C80") (pin "1") (pinfunction "1_1") (pintype "passive"))
      (node (ref "C81") (pin "2") (pinfunction "2_2") (pintype "passive"))
      (node (ref "C82") (pin "2") (pinfunction "2_2") (pintype "passive"))
      (node (ref "C83") (pin "1") (pinfunction "1_1") (pintype "passive"))
      (node (ref "C84") (pin "2") (pinfunction "2_2") (pintype "passive"))
      (node (ref "C85") (pin "2") (pinfunction "2_2") (pintype "passive"))
      (node (ref "C86") (pin "2") (pinfunction "2_2") (pintype "passive"))
      (node (ref "C87") (pin "2") (pinfunction "2_2") (pintype "passive"))
      (node (ref "C88") (pin "2") (pinfunction "2_2") (pintype "passive"))
      (node (ref "C89") (pin "2") (pinfunction "2_2") (pintype "passive"))
      (node (ref "C9") (pin "2") (pinfunction "2_2") (pintype "passive"))
      (node (ref "C90") (pin "1") (pinfunction "1_1") (pintype "passive"))
      (node (ref "C91") (pin "1") (pinfunction "1_1") (pintype "passive"))
      (node (ref "C92") (pin "2") (pinfunction "2_2") (pintype "passive"))
      (node (ref "C93") (pin "2") (pinfunction "2_2") (pintype "passive"))
      (node (ref "C94") (pin "2") (pinfunction "2_2") (pintype "passive"))
      (node (ref "C95") (pin "2") (pinfunction "2_2") (pintype "passive"))
      (node (ref "C96") (pin "2") (pinfunction "2_2") (pintype "passive"))
      (node (ref "C97") (pin "2") (pinfunction "2_2") (pintype "passive"))
      (node (ref "C98") (pin "2") (pinfunction "2_2") (pintype "passive"))
      (node (ref "C99") (pin "2") (pinfunction "2_2") (pintype "passive"))
      (node (ref "CLKIN") (pin "5") (pinfunction "5_5") (pintype "passive"))
      (node (ref "CUSB1") (pin "2") (pinfunction "2_2") (pintype "passive"))
      (node (ref "GND") (pin "TP") (pinfunction "TP_TP") (pintype "input"))
      (node (ref "GND174") (pin "TP") (pinfunction "TP_TP") (pintype "input"))
      (node (ref "GND176") (pin "TP") (pinfunction "TP_TP") (pintype "input"))
      (node (ref "GND26") (pin "TP") (pinfunction "TP_TP") (pintype "input"))
      (node (ref "IC1") (pin "2") (pinfunction "GND_2") (pintype "bidirectional"))
      (node (ref "IC13") (pin "P13") (pinfunction "VSS_P13") (pintype "bidirectional"))
      (node (ref "IC13") (pin "P25") (pinfunction "VSS_P25") (pintype "bidirectional"))
      (node (ref "IC13") (pin "P36") (pinfunction "VSS_P36") (pintype "bidirectional"))
      (node (ref "IC13") (pin "P48") (pinfunction "VSS_P48") (pintype "bidirectional"))
      (node (ref "IC14") (pin "P$3") (pinfunction "GND_P$3") (pintype "bidirectional"))
      (node (ref "IC14") (pin "P$6") (pinfunction "GND_T_P$6") (pintype "bidirectional"))
      (node (ref "IC15") (pin "P$2") (pinfunction "GND_P$2") (pintype "bidirectional"))
      (node (ref "IC16") (pin "13") (pinfunction "VSS_13") (pintype "input"))
      (node (ref "IC16") (pin "31") (pinfunction "AVSS_31") (pintype "bidirectional"))
      (node (ref "IC16") (pin "36") (pinfunction "VSS_36") (pintype "bidirectional"))
      (node (ref "IC16") (pin "45") (pinfunction "VSS_45") (pintype "bidirectional"))
      (node (ref "IC16") (pin "53") (pinfunction "VSS_53") (pintype "bidirectional"))
      (node (ref "IC16") (pin "63") (pinfunction "VSS_63") (pintype "bidirectional"))
      (node (ref "IC16") (pin "75") (pinfunction "VSS_75") (pintype "bidirectional"))
      (node (ref "IC16") (pin "84") (pinfunction "VSS_84") (pintype "bidirectional"))
      (node (ref "IC16") (pin "92") (pinfunction "VSS_92") (pintype "input"))
      (node (ref "IC18") (pin "2") (pinfunction "GND_2") (pintype "bidirectional"))
      (node (ref "IC2") (pin "1") (pinfunction "PGND_1") (pintype "bidirectional"))
      (node (ref "IC2") (pin "15") (pinfunction "AGND_15") (pintype "bidirectional"))
      (node (ref "IC2") (pin "4") (pinfunction "SYNC/FREQ_4") (pintype "bidirectional"))
      (node (ref "IC2") (pin "6") (pinfunction "SLEW_6") (pintype "bidirectional"))
      (node (ref "IC2") (pin "EPAD") (pinfunction "PGND_EPAD") (pintype "bidirectional"))
      (node (ref "IC20") (pin "2") (pinfunction "GND_2") (pintype "bidirectional"))
      (node (ref "IC21") (pin "15") (pinfunction "GND2_15") (pintype "bidirectional"))
      (node (ref "IC21") (pin "9") (pinfunction "GND2_9") (pintype "bidirectional"))
      (node (ref "IC22") (pin "1") (pinfunction "P$1_1") (pintype "bidirectional"))
      (node (ref "IC22") (pin "3") (pinfunction "P$3_3") (pintype "bidirectional"))
      (node (ref "IC23") (pin "1") (pinfunction "P$1_1") (pintype "bidirectional"))
      (node (ref "IC23") (pin "3") (pinfunction "P$3_3") (pintype "bidirectional"))
      (node (ref "IC24") (pin "1") (pinfunction "P$1_1") (pintype "bidirectional"))
      (node (ref "IC24") (pin "3") (pinfunction "P$3_3") (pintype "bidirectional"))
      (node (ref "IC25") (pin "18") (pinfunction "GND_18") (pintype "power_in"))
      (node (ref "IC25") (pin "30") (pinfunction "GND_30") (pintype "power_in"))
      (node (ref "IC25") (pin "38") (pinfunction "GND_38") (pintype "power_in"))
      (node (ref "IC25") (pin "7") (pinfunction "PB3/ADC11/DAC1_7") (pintype "bidirectional"))
      (node (ref "IC25") (pin "8") (pinfunction "GND_8") (pintype "power_in"))
      (node (ref "IC26") (pin "2") (pinfunction "V-_2") (pintype "power_in"))
      (node (ref "IC27") (pin "2") (pinfunction "V-_2") (pintype "power_in"))
      (node (ref "IC28") (pin "1") (pinfunction "P$1_1") (pintype "bidirectional"))
      (node (ref "IC28") (pin "3") (pinfunction "P$3_3") (pintype "bidirectional"))
      (node (ref "IC29") (pin "1") (pinfunction "P$1_1") (pintype "bidirectional"))
      (node (ref "IC29") (pin "3") (pinfunction "P$3_3") (pintype "bidirectional"))
      (node (ref "IC3") (pin "1") (pinfunction "GND_1") (pintype "bidirectional"))
      (node (ref "IC30") (pin "1") (pinfunction "P$1_1") (pintype "bidirectional"))
      (node (ref "IC30") (pin "3") (pinfunction "P$3_3") (pintype "bidirectional"))
      (node (ref "IC31") (pin "1") (pinfunction "P$1_1") (pintype "bidirectional"))
      (node (ref "IC31") (pin "3") (pinfunction "P$3_3") (pintype "bidirectional"))
      (node (ref "IC32") (pin "3") (pinfunction "GND_3") (pintype "bidirectional"))
      (node (ref "IC33") (pin "3") (pinfunction "GND_3") (pintype "bidirectional"))
      (node (ref "IC35") (pin "3") (pinfunction "GND_3") (pintype "bidirectional"))
      (node (ref "IC4") (pin "2") (pinfunction "GND_2") (pintype "bidirectional"))
      (node (ref "IC5") (pin "2") (pinfunction "GND_2") (pintype "bidirectional"))
      (node (ref "IC6") (pin "P10") (pinfunction "AGND_P10") (pintype "bidirectional"))
      (node (ref "IC6") (pin "P19") (pinfunction "AGND_P19") (pintype "bidirectional"))
      (node (ref "IC6") (pin "P28") (pinfunction "DGND_P28") (pintype "bidirectional"))
      (node (ref "IC6") (pin "P9") (pinfunction "DSD_PHASE_P9") (pintype "bidirectional"))
      (node (ref "J3") (pin "P1") (pinfunction "1_P1") (pintype "passive"))
      (node (ref "J4") (pin "P1") (pinfunction "1_P1") (pintype "passive"))
      (node (ref "JACK") (pin "P2") (pinfunction "2_P2") (pintype "passive"))
      (node (ref "JACK") (pin "P3") (pinfunction "3_P3") (pintype "passive"))
      (node (ref "JP1") (pin "3") (pinfunction "3_3") (pintype "passive"))
      (node (ref "L3") (pin "2") (pinfunction "2_2") (pintype "passive"))
      (node (ref "LED1") (pin "K") (pinfunction "K_K") (pintype "bidirectional"))
      (node (ref "LED2") (pin "K") (pinfunction "K_K") (pintype "bidirectional"))
      (node (ref "LED3") (pin "K") (pinfunction "K_K") (pintype "bidirectional"))
      (node (ref "OSC1") (pin "P$2") (pinfunction "GND_P$2") (pintype "passive"))
      (node (ref "OSC2") (pin "P$2") (pinfunction "GND_P$2") (pintype "passive"))
      (node (ref "OSC3") (pin "P$2") (pinfunction "GND_P$2") (pintype "passive"))
      (node (ref "PDI") (pin "6") (pinfunction "6_6") (pintype "passive"))
      (node (ref "R15") (pin "2") (pinfunction "2_2") (pintype "passive"))
      (node (ref "R18") (pin "1") (pinfunction "1_1") (pintype "passive"))
      (node (ref "R20") (pin "2") (pinfunction "2_2") (pintype "passive"))
      (node (ref "R22") (pin "1") (pinfunction "1_1") (pintype "passive"))
      (node (ref "R3") (pin "2") (pinfunction "2_2") (pintype "passive"))
      (node (ref "R34") (pin "1") (pinfunction "1_1") (pintype "passive"))
      (node (ref "R50") (pin "1") (pinfunction "1_1") (pintype "passive"))
      (node (ref "R55") (pin "1") (pinfunction "1_1") (pintype "passive"))
      (node (ref "R61") (pin "2") (pinfunction "2_2") (pintype "passive"))
      (node (ref "R67") (pin "2") (pinfunction "2_2") (pintype "passive"))
      (node (ref "R68") (pin "2") (pinfunction "2_2") (pintype "passive"))
      (node (ref "R7") (pin "2") (pinfunction "2_2") (pintype "passive"))
      (node (ref "R78") (pin "2") (pinfunction "2_2") (pintype "passive"))
      (node (ref "R79") (pin "2") (pinfunction "2_2") (pintype "passive"))
      (node (ref "R84") (pin "1") (pinfunction "1_1") (pintype "passive"))
      (node (ref "R86") (pin "1") (pinfunction "1_1") (pintype "passive"))
      (node (ref "R89") (pin "2") (pinfunction "2_2") (pintype "passive"))
      (node (ref "RUSB1") (pin "2") (pinfunction "2_2") (pintype "passive"))
      (node (ref "STATE") (pin "K") (pinfunction "K_K") (pintype "bidirectional"))
      (node (ref "SW1") (pin "P") (pinfunction "P_P") (pintype "passive"))
      (node (ref "USB1") (pin "P$5") (pinfunction "5_P$5") (pintype "bidirectional"))
      (node (ref "X1") (pin "P12") (pinfunction "12_P12") (pintype "passive"))
      (node (ref "X1") (pin "P3") (pinfunction "3_P3") (pintype "passive"))
      (node (ref "X1") (pin "P8") (pinfunction "8_P8") (pintype "passive"))
    )
    (net (code "34") (name "GND2") (class "Default")
      (node (ref "C106") (pin "2") (pinfunction "2_2") (pintype "passive"))
      (node (ref "C107") (pin "2") (pinfunction "2_2") (pintype "passive"))
      (node (ref "C108") (pin "2") (pinfunction "2_2") (pintype "passive"))
      (node (ref "C111") (pin "2") (pinfunction "2_2") (pintype "passive"))
      (node (ref "C112") (pin "-") (pinfunction "-_-") (pintype "passive"))
      (node (ref "C113") (pin "2") (pinfunction "2_2") (pintype "passive"))
      (node (ref "C114") (pin "2") (pinfunction "2_2") (pintype "passive"))
      (node (ref "C117") (pin "2") (pinfunction "2_2") (pintype "passive"))
      (node (ref "CUSB2") (pin "2") (pinfunction "2_2") (pintype "passive"))
      (node (ref "IC17") (pin "P$2") (pinfunction "GND_P$2") (pintype "bidirectional"))
      (node (ref "IC19") (pin "18") (pinfunction "GND_18") (pintype "power_in"))
      (node (ref "IC19") (pin "21") (pinfunction "GND_21") (pintype "power_in"))
      (node (ref "IC19") (pin "25") (pinfunction "GND_25") (pintype "power_in"))
      (node (ref "IC19") (pin "26") (pinfunction "TEST_26") (pintype "input"))
      (node (ref "IC19") (pin "7") (pinfunction "GND_7") (pintype "power_in"))
      (node (ref "IC21") (pin "2") (pinfunction "GND1_2") (pintype "bidirectional"))
      (node (ref "IC21") (pin "8") (pinfunction "GND1_8") (pintype "bidirectional"))
      (node (ref "RUSB2") (pin "2") (pinfunction "2_2") (pintype "passive"))
      (node (ref "USB2") (pin "P$5") (pinfunction "5_P$5") (pintype "bidirectional"))
    )
    (net (code "35") (name "IN0") (class "Default")
      (node (ref "IC24") (pin "2") (pinfunction "P$2_2") (pintype "bidirectional"))
      (node (ref "R61") (pin "1") (pinfunction "1_1") (pintype "passive"))
      (node (ref "X1") (pin "P11") (pinfunction "11_P11") (pintype "passive"))
    )
    (net (code "36") (name "IN00{slash}TRIG") (class "Default")
      (node (ref "IC16") (pin "71") (pinfunction "EMDIO/AEMDIO/RPD0/RTCC/INT0/RD0_71") (pintype "bidirectional"))
      (node (ref "IC16") (pin "81") (pinfunction "~{SQICS0}/RPD4/RD4_81") (pintype "bidirectional"))
      (node (ref "IC24") (pin "4") (pinfunction "P$4_4") (pintype "bidirectional"))
      (node (ref "IC25") (pin "4") (pinfunction "PB0/ADC8/AREF_4") (pintype "bidirectional"))
    )
    (net (code "37") (name "IN1") (class "Default")
      (node (ref "IC30") (pin "2") (pinfunction "P$2_2") (pintype "bidirectional"))
      (node (ref "R67") (pin "1") (pinfunction "1_1") (pintype "passive"))
      (node (ref "X1") (pin "P10") (pinfunction "10_P10") (pintype "passive"))
    )
    (net (code "38") (name "IN01") (class "Default")
      (node (ref "IC25") (pin "20") (pinfunction "~{OC0APD0}_20") (pintype "bidirectional"))
      (node (ref "IC30") (pin "4") (pinfunction "P$4_4") (pintype "bidirectional"))
    )
    (net (code "39") (name "IN2") (class "Default")
      (node (ref "IC31") (pin "2") (pinfunction "P$2_2") (pintype "bidirectional"))
      (node (ref "R68") (pin "1") (pinfunction "1_1") (pintype "passive"))
      (node (ref "X1") (pin "P9") (pinfunction "9_P9") (pintype "passive"))
    )
    (net (code "40") (name "IN02") (class "Default")
      (node (ref "IC25") (pin "10") (pinfunction "PC0/OC0A/SDA_10") (pintype "bidirectional"))
      (node (ref "IC31") (pin "4") (pinfunction "P$4_4") (pintype "bidirectional"))
    )
    (net (code "41") (name "IOUTL+") (class "Default")
      (node (ref "C62") (pin "1") (pinfunction "1_1") (pintype "passive"))
      (node (ref "IC10") (pin "2") (pinfunction "-IN_2") (pintype "input"))
      (node (ref "IC6") (pin "P18") (pinfunction "IOUTL+_P18") (pintype "bidirectional"))
      (node (ref "R39") (pin "1") (pinfunction "1_1") (pintype "passive"))
      (node (ref "R43") (pin "1") (pinfunction "1_1") (pintype "passive"))
      (node (ref "R45") (pin "1") (pinfunction "1_1") (pintype "passive"))
    )
    (net (code "42") (name "IOUTL-") (class "Default")
      (node (ref "C62") (pin "2") (pinfunction "2_2") (pintype "passive"))
      (node (ref "IC11") (pin "2") (pinfunction "-IN_2") (pintype "input"))
      (node (ref "IC6") (pin "P17") (pinfunction "IOUTL-_P17") (pintype "bidirectional"))
      (node (ref "R42") (pin "1") (pinfunction "1_1") (pintype "passive"))
      (node (ref "R44") (pin "1") (pinfunction "1_1") (pintype "passive"))
      (node (ref "R46") (pin "1") (pinfunction "1_1") (pintype "passive"))
    )
    (net (code "43") (name "IOUTR+") (class "Default")
      (node (ref "C38") (pin "1") (pinfunction "1_1") (pintype "passive"))
      (node (ref "IC6") (pin "P11") (pinfunction "IOUTR+_P11") (pintype "bidirectional"))
      (node (ref "IC7") (pin "2") (pinfunction "-IN_2") (pintype "input"))
      (node (ref "R23") (pin "1") (pinfunction "1_1") (pintype "passive"))
      (node (ref "R27") (pin "1") (pinfunction "1_1") (pintype "passive"))
      (node (ref "R29") (pin "1") (pinfunction "1_1") (pintype "passive"))
    )
    (net (code "44") (name "IOUTR-") (class "Default")
      (node (ref "C38") (pin "2") (pinfunction "2_2") (pintype "passive"))
      (node (ref "IC6") (pin "P12") (pinfunction "IOUTR-_P12") (pintype "bidirectional"))
      (node (ref "IC8") (pin "2") (pinfunction "-IN_2") (pintype "input"))
      (node (ref "R26") (pin "1") (pinfunction "1_1") (pintype "passive"))
      (node (ref "R28") (pin "1") (pinfunction "1_1") (pintype "passive"))
      (node (ref "R30") (pin "1") (pinfunction "1_1") (pintype "passive"))
    )
    (net (code "45") (name "MEMORY") (class "Default")
      (node (ref "IC16") (pin "95") (pinfunction "TRD2/SQID2/RG14_95") (pintype "bidirectional"))
      (node (ref "R75") (pin "2") (pinfunction "2_2") (pintype "passive"))
    )
    (net (code "46") (name "MUTE") (class "Default")
      (node (ref "IC16") (pin "57") (pinfunction "EBIRDY3/RPF2/SDA3/RF2_57") (pintype "bidirectional"))
      (node (ref "IC6") (pin "P22") (pinfunction "MUTE_P22") (pintype "bidirectional"))
    )
    (net (code "47") (name "Net-(C3-Pad1)") (class "Default")
      (node (ref "C3") (pin "1") (pinfunction "1_1") (pintype "passive"))
      (node (ref "R4") (pin "2") (pinfunction "2_2") (pintype "passive"))
    )
    (net (code "48") (name "Net-(C6-Pad1)") (class "Default")
      (node (ref "C6") (pin "1") (pinfunction "1_1") (pintype "passive"))
      (node (ref "D1") (pin "C") (pinfunction "C_C") (pintype "passive"))
      (node (ref "L1") (pin "2") (pinfunction "2_2") (pintype "passive"))
      (node (ref "R5") (pin "1") (pinfunction "1_1") (pintype "passive"))
    )
    (net (code "49") (name "Net-(C7-Pad1)") (class "Default")
      (node (ref "C7") (pin "1") (pinfunction "1_1") (pintype "passive"))
      (node (ref "R8") (pin "2") (pinfunction "2_2") (pintype "passive"))
    )
    (net (code "50") (name "Net-(C12-Pad1)") (class "Default")
      (node (ref "C12") (pin "1") (pinfunction "1_1") (pintype "passive"))
      (node (ref "R13") (pin "1") (pinfunction "1_1") (pintype "passive"))
    )
    (net (code "51") (name "Net-(C13-Pad1)") (class "Default")
      (node (ref "C13") (pin "1") (pinfunction "1_1") (pintype "passive"))
      (node (ref "D2") (pin "A") (pinfunction "A_A") (pintype "passive"))
      (node (ref "L4") (pin "1") (pinfunction "1_1") (pintype "passive"))
      (node (ref "R17") (pin "2") (pinfunction "2_2") (pintype "passive"))
    )
    (net (code "52") (name "Net-(C15-Pad1)") (class "Default")
      (node (ref "C15") (pin "1") (pinfunction "1_1") (pintype "passive"))
      (node (ref "R16") (pin "2") (pinfunction "2_2") (pintype "passive"))
    )
    (net (code "53") (name "Net-(C43-Pad1)") (class "Default")
      (node (ref "C43") (pin "1") (pinfunction "1_1") (pintype "passive"))
      (node (ref "R27") (pin "2") (pinfunction "2_2") (pintype "passive"))
    )
    (net (code "54") (name "Net-(C44-Pad1)") (class "Default")
      (node (ref "C44") (pin "1") (pinfunction "1_1") (pintype "passive"))
      (node (ref "R28") (pin "2") (pinfunction "2_2") (pintype "passive"))
    )
    (net (code "55") (name "Net-(C47-Pad1)") (class "Default")
      (node (ref "C47") (pin "1") (pinfunction "1_1") (pintype "passive"))
      (node (ref "R31") (pin "2") (pinfunction "2_2") (pintype "passive"))
      (node (ref "R33") (pin "1") (pinfunction "1_1") (pintype "passive"))
      (node (ref "R35") (pin "1") (pinfunction "1_1") (pintype "passive"))
    )
    (net (code "56") (name "Net-(C48-Pad1)") (class "Default")
      (node (ref "C48") (pin "1") (pinfunction "1_1") (pintype "passive"))
      (node (ref "R32") (pin "2") (pinfunction "2_2") (pintype "passive"))
      (node (ref "R34") (pin "2") (pinfunction "2_2") (pintype "passive"))
      (node (ref "R36") (pin "1") (pinfunction "1_1") (pintype "passive"))
    )
    (net (code "57") (name "Net-(C54-Pad1)") (class "Default")
      (node (ref "C54") (pin "1") (pinfunction "1_1") (pintype "passive"))
      (node (ref "R37") (pin "2") (pinfunction "2_2") (pintype "passive"))
    )
    (net (code "58") (name "Net-(C67-Pad1)") (class "Default")
      (node (ref "C67") (pin "1") (pinfunction "1_1") (pintype "passive"))
      (node (ref "R43") (pin "2") (pinfunction "2_2") (pintype "passive"))
    )
    (net (code "59") (name "Net-(C68-Pad1)") (class "Default")
      (node (ref "C68") (pin "1") (pinfunction "1_1") (pintype "passive"))
      (node (ref "R44") (pin "2") (pinfunction "2_2") (pintype "passive"))
    )
    (net (code "60") (name "Net-(C71-Pad1)") (class "Default")
      (node (ref "C71") (pin "1") (pinfunction "1_1") (pintype "passive"))
      (node (ref "R47") (pin "2") (pinfunction "2_2") (pintype "passive"))
      (node (ref "R49") (pin "1") (pinfunction "1_1") (pintype "passive"))
      (node (ref "R51") (pin "1") (pinfunction "1_1") (pintype "passive"))
    )
    (net (code "61") (name "Net-(C72-Pad1)") (class "Default")
      (node (ref "C72") (pin "1") (pinfunction "1_1") (pintype "passive"))
      (node (ref "R48") (pin "2") (pinfunction "2_2") (pintype "passive"))
      (node (ref "R50") (pin "2") (pinfunction "2_2") (pintype "passive"))
      (node (ref "R52") (pin "1") (pinfunction "1_1") (pintype "passive"))
    )
    (net (code "62") (name "Net-(C78-Pad1)") (class "Default")
      (node (ref "C78") (pin "1") (pinfunction "1_1") (pintype "passive"))
      (node (ref "R53") (pin "2") (pinfunction "2_2") (pintype "passive"))
    )
    (net (code "63") (name "Net-(C101-Pad1)") (class "Default")
      (node (ref "C101") (pin "1") (pinfunction "1_1") (pintype "passive"))
      (node (ref "R56") (pin "1") (pinfunction "1_1") (pintype "passive"))
      (node (ref "R57") (pin "2") (pinfunction "2_2") (pintype "passive"))
    )
    (net (code "64") (name "Net-(IC1-ADJ)") (class "Default")
      (node (ref "IC1") (pin "4") (pinfunction "ADJ_4") (pintype "bidirectional"))
      (node (ref "R1") (pin "2") (pinfunction "2_2") (pintype "passive"))
      (node (ref "R2") (pin "2") (pinfunction "2_2") (pintype "passive"))
      (node (ref "R3") (pin "1") (pinfunction "1_1") (pintype "passive"))
      (node (ref "R4") (pin "1") (pinfunction "1_1") (pintype "passive"))
    )
    (net (code "65") (name "Net-(IC1-EN)") (class "Default")
      (node (ref "C148") (pin "1") (pinfunction "1_1") (pintype "passive"))
      (node (ref "IC1") (pin "3") (pinfunction "EN_3") (pintype "bidirectional"))
      (node (ref "R79") (pin "1") (pinfunction "1_1") (pintype "passive"))
      (node (ref "R87") (pin "2") (pinfunction "2_2") (pintype "passive"))
    )
    (net (code "66") (name "Net-(IC2-COMP1)") (class "Default")
      (node (ref "C8") (pin "1") (pinfunction "1_1") (pintype "passive"))
      (node (ref "IC2") (pin "8") (pinfunction "COMP1_8") (pintype "bidirectional"))
      (node (ref "R8") (pin "1") (pinfunction "1_1") (pintype "passive"))
    )
    (net (code "67") (name "Net-(IC2-COMP2)") (class "Default")
      (node (ref "C10") (pin "1") (pinfunction "1_1") (pintype "passive"))
      (node (ref "IC2") (pin "12") (pinfunction "COMP2_12") (pintype "bidirectional"))
      (node (ref "R13") (pin "2") (pinfunction "2_2") (pintype "passive"))
    )
    (net (code "68") (name "Net-(IC2-FB1)") (class "Default")
      (node (ref "IC2") (pin "7") (pinfunction "FB1_7") (pintype "bidirectional"))
      (node (ref "R6") (pin "1") (pinfunction "1_1") (pintype "passive"))
      (node (ref "R7") (pin "1") (pinfunction "1_1") (pintype "passive"))
    )
    (net (code "69") (name "Net-(IC2-FB2)") (class "Default")
      (node (ref "IC2") (pin "13") (pinfunction "FB2_13") (pintype "bidirectional"))
      (node (ref "R10") (pin "2") (pinfunction "2_2") (pintype "passive"))
      (node (ref "R12") (pin "2") (pinfunction "2_2") (pintype "passive"))
    )
    (net (code "70") (name "Net-(IC2-INBK)") (class "Default")
      (node (ref "IC2") (pin "3") (pinfunction "INBK_3") (pintype "bidirectional"))
      (node (ref "L2") (pin "2") (pinfunction "2_2") (pintype "passive"))
    )
    (net (code "71") (name "Net-(IC2-SW1)") (class "Default")
      (node (ref "D1") (pin "A") (pinfunction "A_A") (pintype "passive"))
      (node (ref "IC2") (pin "2") (pinfunction "SW1_2") (pintype "bidirectional"))
      (node (ref "L2") (pin "1") (pinfunction "1_1") (pintype "passive"))
    )
    (net (code "72") (name "Net-(IC2-SW2)") (class "Default")
      (node (ref "D2") (pin "C") (pinfunction "C_C") (pintype "passive"))
      (node (ref "IC2") (pin "20") (pinfunction "SW2_20") (pintype "bidirectional"))
      (node (ref "L3") (pin "1") (pinfunction "1_1") (pintype "passive"))
    )
    (net (code "73") (name "Net-(IC2-VREF)") (class "Default")
      (node (ref "C137") (pin "1") (pinfunction "1_1") (pintype "passive"))
      (node (ref "IC2") (pin "14") (pinfunction "VREF_14") (pintype "bidirectional"))
      (node (ref "R10") (pin "1") (pinfunction "1_1") (pintype "passive"))
    )
    (net (code "74") (name "Net-(IC2-VREG)") (class "Default")
      (node (ref "C14") (pin "1") (pinfunction "1_1") (pintype "passive"))
      (node (ref "IC2") (pin "16") (pinfunction "VREG_16") (pintype "bidirectional"))
    )
    (net (code "75") (name "Net-(IC3-ADJ)") (class "Default")
      (node (ref "IC3") (pin "4") (pinfunction "ADJ_4") (pintype "bidirectional"))
      (node (ref "R11") (pin "2") (pinfunction "2_2") (pintype "passive"))
      (node (ref "R14") (pin "2") (pinfunction "2_2") (pintype "passive"))
      (node (ref "R15") (pin "1") (pinfunction "1_1") (pintype "passive"))
      (node (ref "R16") (pin "1") (pinfunction "1_1") (pintype "passive"))
    )
    (net (code "76") (name "Net-(IC3-EN)") (class "Default")
      (node (ref "C149") (pin "1") (pinfunction "1_1") (pintype "passive"))
      (node (ref "IC3") (pin "3") (pinfunction "EN_3") (pintype "bidirectional"))
      (node (ref "R78") (pin "1") (pinfunction "1_1") (pintype "passive"))
      (node (ref "R88") (pin "2") (pinfunction "2_2") (pintype "passive"))
    )
    (net (code "77") (name "Net-(IC4-EN)") (class "Default")
      (node (ref "C24") (pin "2") (pinfunction "2_2") (pintype "passive"))
      (node (ref "C26") (pin "2") (pinfunction "2_2") (pintype "passive"))
      (node (ref "IC4") (pin "1") (pinfunction "IN_1") (pintype "bidirectional"))
      (node (ref "IC4") (pin "3") (pinfunction "EN_3") (pintype "bidirectional"))
      (node (ref "L5") (pin "2") (pinfunction "2_2") (pintype "passive"))
    )
    (net (code "78") (name "Net-(IC4-N{slash}C)") (class "Default")
      (node (ref "C22") (pin "2") (pinfunction "2_2") (pintype "passive"))
      (node (ref "IC4") (pin "4") (pinfunction "N/C_4") (pintype "bidirectional"))
    )
    (net (code "79") (name "Net-(IC5-EN)") (class "Default")
      (node (ref "C25") (pin "2") (pinfunction "2_2") (pintype "passive"))
      (node (ref "C27") (pin "2") (pinfunction "2_2") (pintype "passive"))
      (node (ref "IC5") (pin "1") (pinfunction "IN_1") (pintype "bidirectional"))
      (node (ref "IC5") (pin "3") (pinfunction "EN_3") (pintype "bidirectional"))
      (node (ref "L6") (pin "2") (pinfunction "2_2") (pintype "passive"))
    )
    (net (code "80") (name "Net-(IC5-N{slash}C)") (class "Default")
      (node (ref "C23") (pin "2") (pinfunction "2_2") (pintype "passive"))
      (node (ref "IC5") (pin "4") (pinfunction "N/C_4") (pintype "bidirectional"))
    )
    (net (code "81") (name "Net-(IC6-AVDD)") (class "Default")
      (node (ref "C31") (pin "1") (pinfunction "1_1") (pintype "passive"))
      (node (ref "IC6") (pin "P15") (pinfunction "AVDD_P15") (pintype "bidirectional"))
      (node (ref "L8") (pin "2") (pinfunction "2_2") (pintype "passive"))
    )
    (net (code "82") (name "Net-(IC6-DVDD)") (class "Default")
      (node (ref "C30") (pin "1") (pinfunction "1_1") (pintype "passive"))
      (node (ref "IC6") (pin "P1") (pinfunction "DVDD_P1") (pintype "bidirectional"))
      (node (ref "L7") (pin "2") (pinfunction "2_2") (pintype "passive"))
    )
    (net (code "83") (name "Net-(IC6-FILTR)") (class "Default")
      (node (ref "C29") (pin "1") (pinfunction "1_1") (pintype "passive"))
      (node (ref "C33") (pin "+") (pinfunction "+_+") (pintype "passive"))
      (node (ref "IC6") (pin "P13") (pinfunction "FILTR_P13") (pintype "bidirectional"))
    )
    (net (code "84") (name "Net-(IC6-IREF)") (class "Default")
      (node (ref "IC6") (pin "P14") (pinfunction "IREF_P14") (pintype "bidirectional"))
      (node (ref "R18") (pin "2") (pinfunction "2_2") (pintype "passive"))
    )
    (net (code "85") (name "Net-(IC7-+IN)") (class "Default")
      (node (ref "C39") (pin "1") (pinfunction "1_1") (pintype "passive"))
      (node (ref "IC7") (pin "3") (pinfunction "+IN_3") (pintype "input"))
      (node (ref "R24") (pin "1") (pinfunction "1_1") (pintype "passive"))
    )
    (net (code "86") (name "Net-(IC7-OUT)") (class "Default")
      (node (ref "C43") (pin "2") (pinfunction "2_2") (pintype "passive"))
      (node (ref "IC7") (pin "6") (pinfunction "OUT_6") (pintype "output"))
      (node (ref "R29") (pin "2") (pinfunction "2_2") (pintype "passive"))
      (node (ref "R31") (pin "1") (pinfunction "1_1") (pintype "passive"))
    )
    (net (code "87") (name "Net-(IC8-+IN)") (class "Default")
      (node (ref "C40") (pin "1") (pinfunction "1_1") (pintype "passive"))
      (node (ref "IC8") (pin "3") (pinfunction "+IN_3") (pintype "input"))
      (node (ref "R25") (pin "1") (pinfunction "1_1") (pintype "passive"))
    )
    (net (code "88") (name "Net-(IC8-OUT)") (class "Default")
      (node (ref "C44") (pin "2") (pinfunction "2_2") (pintype "passive"))
      (node (ref "IC8") (pin "6") (pinfunction "OUT_6") (pintype "output"))
      (node (ref "R30") (pin "2") (pinfunction "2_2") (pintype "passive"))
      (node (ref "R32") (pin "1") (pinfunction "1_1") (pintype "passive"))
    )
    (net (code "89") (name "Net-(IC9-+IN)") (class "Default")
      (node (ref "C51") (pin "1") (pinfunction "1_1") (pintype "passive"))
      (node (ref "IC9") (pin "3") (pinfunction "+IN_3") (pintype "input"))
      (node (ref "R36") (pin "2") (pinfunction "2_2") (pintype "passive"))
    )
    (net (code "90") (name "Net-(IC9--IN)") (class "Default")
      (node (ref "IC9") (pin "2") (pinfunction "-IN_2") (pintype "input"))
      (node (ref "R35") (pin "2") (pinfunction "2_2") (pintype "passive"))
      (node (ref "R37") (pin "1") (pinfunction "1_1") (pintype "passive"))
    )
    (net (code "91") (name "Net-(IC9-OUT)") (class "Default")
      (node (ref "C54") (pin "2") (pinfunction "2_2") (pintype "passive"))
      (node (ref "IC9") (pin "6") (pinfunction "OUT_6") (pintype "output"))
      (node (ref "R33") (pin "2") (pinfunction "2_2") (pintype "passive"))
      (node (ref "R38") (pin "1") (pinfunction "1_1") (pintype "passive"))
    )
    (net (code "92") (name "Net-(IC10-+IN)") (class "Default")
      (node (ref "C63") (pin "1") (pinfunction "1_1") (pintype "passive"))
      (node (ref "IC10") (pin "3") (pinfunction "+IN_3") (pintype "input"))
      (node (ref "R40") (pin "1") (pinfunction "1_1") (pintype "passive"))
    )
    (net (code "93") (name "Net-(IC10-OUT)") (class "Default")
      (node (ref "C67") (pin "2") (pinfunction "2_2") (pintype "passive"))
      (node (ref "IC10") (pin "6") (pinfunction "OUT_6") (pintype "output"))
      (node (ref "R45") (pin "2") (pinfunction "2_2") (pintype "passive"))
      (node (ref "R47") (pin "1") (pinfunction "1_1") (pintype "passive"))
    )
    (net (code "94") (name "Net-(IC11-+IN)") (class "Default")
      (node (ref "C64") (pin "1") (pinfunction "1_1") (pintype "passive"))
      (node (ref "IC11") (pin "3") (pinfunction "+IN_3") (pintype "input"))
      (node (ref "R41") (pin "1") (pinfunction "1_1") (pintype "passive"))
    )
    (net (code "95") (name "Net-(IC11-OUT)") (class "Default")
      (node (ref "C68") (pin "2") (pinfunction "2_2") (pintype "passive"))
      (node (ref "IC11") (pin "6") (pinfunction "OUT_6") (pintype "output"))
      (node (ref "R46") (pin "2") (pinfunction "2_2") (pintype "passive"))
      (node (ref "R48") (pin "1") (pinfunction "1_1") (pintype "passive"))
    )
    (net (code "96") (name "Net-(IC12-+IN)") (class "Default")
      (node (ref "C75") (pin "1") (pinfunction "1_1") (pintype "passive"))
      (node (ref "IC12") (pin "3") (pinfunction "+IN_3") (pintype "input"))
      (node (ref "R52") (pin "2") (pinfunction "2_2") (pintype "passive"))
    )
    (net (code "97") (name "Net-(IC12--IN)") (class "Default")
      (node (ref "IC12") (pin "2") (pinfunction "-IN_2") (pintype "input"))
      (node (ref "R51") (pin "2") (pinfunction "2_2") (pintype "passive"))
      (node (ref "R53") (pin "1") (pinfunction "1_1") (pintype "passive"))
    )
    (net (code "98") (name "Net-(IC12-OUT)") (class "Default")
      (node (ref "C78") (pin "2") (pinfunction "2_2") (pintype "passive"))
      (node (ref "IC12") (pin "6") (pinfunction "OUT_6") (pintype "output"))
      (node (ref "R49") (pin "2") (pinfunction "2_2") (pintype "passive"))
      (node (ref "R54") (pin "1") (pinfunction "1_1") (pintype "passive"))
    )
    (net (code "99") (name "Net-(IC14-EN)") (class "Default")
      (node (ref "C90") (pin "2") (pinfunction "2_2") (pintype "passive"))
      (node (ref "C91") (pin "2") (pinfunction "2_2") (pintype "passive"))
      (node (ref "IC14") (pin "P$1") (pinfunction "IN_P$1") (pintype "bidirectional"))
      (node (ref "IC14") (pin "P$5") (pinfunction "EN_P$5") (pintype "bidirectional"))
      (node (ref "L9") (pin "2") (pinfunction "2_2") (pintype "passive"))
    )
    (net (code "100") (name "Net-(IC14-NR{slash}FB)") (class "Default")
      (node (ref "IC14") (pin "P$4") (pinfunction "NR/FB_P$4") (pintype "bidirectional"))
      (node (ref "R55") (pin "2") (pinfunction "2_2") (pintype "passive"))
      (node (ref "R74") (pin "1") (pinfunction "1_1") (pintype "passive"))
    )
    (net (code "101") (name "Net-(IC15-VBUS)") (class "Default")
      (node (ref "C138") (pin "1") (pinfunction "1_1") (pintype "passive"))
      (node (ref "IC15") (pin "P$5") (pinfunction "VBUS_P$5") (pintype "bidirectional"))
      (node (ref "L13") (pin "2") (pinfunction "2_2") (pintype "passive"))
      (node (ref "USB1") (pin "P$1") (pinfunction "1_P$1") (pintype "bidirectional"))
    )
    (net (code "102") (name "Net-(IC16-OSC1{slash}CLKI{slash}RC12)") (class "Default")
      (node (ref "IC16") (pin "49") (pinfunction "OSC1/CLKI/RC12_49") (pintype "bidirectional"))
      (node (ref "OSC1") (pin "P$3") (pinfunction "OUTPUT_P$3") (pintype "passive"))
    )
    (net (code "103") (name "Net-(IC16-SOSCO{slash}RPC14{slash}T1CK{slash}RC14)") (class "Default")
      (node (ref "IC16") (pin "73") (pinfunction "SOSCO/RPC14/T1CK/RC14_73") (pintype "bidirectional"))
      (node (ref "OSC3") (pin "P$3") (pinfunction "OUTPUT_P$3") (pintype "passive"))
    )
    (net (code "104") (name "Net-(IC17-VBUS)") (class "Default")
      (node (ref "C106") (pin "1") (pinfunction "1_1") (pintype "passive"))
      (node (ref "IC17") (pin "P$5") (pinfunction "VBUS_P$5") (pintype "bidirectional"))
      (node (ref "L10") (pin "2") (pinfunction "2_2") (pintype "passive"))
      (node (ref "USB2") (pin "P$1") (pinfunction "1_P$1") (pintype "bidirectional"))
    )
    (net (code "105") (name "Net-(IC19-3V3OUT)") (class "Default")
      (node (ref "C113") (pin "1") (pinfunction "1_1") (pintype "passive"))
      (node (ref "IC19") (pin "17") (pinfunction "3V3OUT_17") (pintype "output"))
    )
    (net (code "106") (name "Net-(IC25-AVCC)") (class "Default")
      (node (ref "C131") (pin "1") (pinfunction "1_1") (pintype "passive"))
      (node (ref "IC25") (pin "39") (pinfunction "AVCC_39") (pintype "power_in"))
      (node (ref "L12") (pin "2") (pinfunction "2_2") (pintype "passive"))
    )
    (net (code "107") (name "Net-(IC25-PB1{slash}ADC9)") (class "Default")
      (node (ref "C140") (pin "1") (pinfunction "1_1") (pintype "passive"))
      (node (ref "IC25") (pin "5") (pinfunction "PB1/ADC9_5") (pintype "bidirectional"))
      (node (ref "R19") (pin "2") (pinfunction "2_2") (pintype "passive"))
    )
    (net (code "108") (name "Net-(IC25-PB2{slash}ADC10{slash}DAC0)") (class "Default")
      (node (ref "C122") (pin "1") (pinfunction "1_1") (pintype "passive"))
      (node (ref "IC25") (pin "6") (pinfunction "PB2/ADC10/DAC0_6") (pintype "bidirectional"))
      (node (ref "R62") (pin "2") (pinfunction "2_2") (pintype "passive"))
    )
    (net (code "109") (name "Net-(IC25-PR1{slash}XTAL1)") (class "Default")
      (node (ref "IC25") (pin "37") (pinfunction "PR1/XTAL1_37") (pintype "bidirectional"))
      (node (ref "OSC2") (pin "P$3") (pinfunction "OUTPUT_P$3") (pintype "passive"))
    )
    (net (code "110") (name "Net-(IC26-+IN)") (class "Default")
      (node (ref "IC26") (pin "3") (pinfunction "+IN_3") (pintype "input"))
      (node (ref "R83") (pin "1") (pinfunction "1_1") (pintype "passive"))
      (node (ref "R84") (pin "2") (pinfunction "2_2") (pintype "passive"))
    )
    (net (code "111") (name "Net-(IC26--IN)") (class "Default")
      (node (ref "IC26") (pin "1") (pinfunction "OUT_1") (pintype "output"))
      (node (ref "IC26") (pin "4") (pinfunction "-IN_4") (pintype "input"))
      (node (ref "R81") (pin "1") (pinfunction "1_1") (pintype "passive"))
    )
    (net (code "112") (name "Net-(IC27-+IN)") (class "Default")
      (node (ref "IC27") (pin "3") (pinfunction "+IN_3") (pintype "input"))
      (node (ref "R85") (pin "1") (pinfunction "1_1") (pintype "passive"))
      (node (ref "R86") (pin "2") (pinfunction "2_2") (pintype "passive"))
    )
    (net (code "113") (name "Net-(IC27--IN)") (class "Default")
      (node (ref "IC27") (pin "1") (pinfunction "OUT_1") (pintype "output"))
      (node (ref "IC27") (pin "4") (pinfunction "-IN_4") (pintype "input"))
      (node (ref "R82") (pin "1") (pinfunction "1_1") (pintype "passive"))
    )
    (net (code "114") (name "Net-(LED1-PadA)") (class "Default")
      (node (ref "LED1") (pin "A") (pinfunction "A_A") (pintype "bidirectional"))
      (node (ref "R75") (pin "1") (pinfunction "1_1") (pintype "passive"))
    )
    (net (code "115") (name "Net-(LED2-PadA)") (class "Default")
      (node (ref "LED2") (pin "A") (pinfunction "A_A") (pintype "bidirectional"))
      (node (ref "R76") (pin "1") (pinfunction "1_1") (pintype "passive"))
    )
    (net (code "116") (name "Net-(LED3-PadA)") (class "Default")
      (node (ref "LED3") (pin "A") (pinfunction "A_A") (pintype "bidirectional"))
      (node (ref "R77") (pin "1") (pinfunction "1_1") (pintype "passive"))
    )
    (net (code "117") (name "Net-(R66-Pad1)") (class "Default")
      (node (ref "R66") (pin "1") (pinfunction "1_1") (pintype "passive"))
      (node (ref "STATE") (pin "A") (pinfunction "A_A") (pintype "bidirectional"))
    )
    (net (code "118") (name "Net-(USB1-2)") (class "Default")
      (node (ref "IC15") (pin "P$1") (pinfunction "IO1_P$1") (pintype "bidirectional"))
      (node (ref "USB1") (pin "P$2") (pinfunction "2_P$2") (pintype "bidirectional"))
    )
    (net (code "119") (name "Net-(USB1-3)") (class "Default")
      (node (ref "IC15") (pin "P$3") (pinfunction "IO2_P$3") (pintype "bidirectional"))
      (node (ref "USB1") (pin "P$3") (pinfunction "3_P$3") (pintype "bidirectional"))
    )
    (net (code "120") (name "Net-(USB1-P$1)") (class "Default")
      (node (ref "RUSB1") (pin "1") (pinfunction "1_1") (pintype "passive"))
      (node (ref "USB1") (pin "SHIELD_3") (pinfunction "P$1_SHIELD_3") (pintype "bidirectional"))
    )
    (net (code "121") (name "Net-(USB1-P$4)") (class "Default")
      (node (ref "CUSB1") (pin "1") (pinfunction "1_1") (pintype "passive"))
      (node (ref "USB1") (pin "SHIELD_4") (pinfunction "P$4_SHIELD_4") (pintype "bidirectional"))
    )
    (net (code "122") (name "Net-(USB2-2)") (class "Default")
      (node (ref "IC17") (pin "P$1") (pinfunction "IO1_P$1") (pintype "bidirectional"))
      (node (ref "USB2") (pin "P$2") (pinfunction "2_P$2") (pintype "bidirectional"))
    )
    (net (code "123") (name "Net-(USB2-3)") (class "Default")
      (node (ref "IC17") (pin "P$3") (pinfunction "IO2_P$3") (pintype "bidirectional"))
      (node (ref "USB2") (pin "P$3") (pinfunction "3_P$3") (pintype "bidirectional"))
    )
    (net (code "124") (name "Net-(USB2-P$1)") (class "Default")
      (node (ref "RUSB2") (pin "1") (pinfunction "1_1") (pintype "passive"))
      (node (ref "USB2") (pin "SHIELD_1") (pinfunction "P$1_SHIELD_1") (pintype "bidirectional"))
    )
    (net (code "125") (name "Net-(USB2-P$4)") (class "Default")
      (node (ref "CUSB2") (pin "1") (pinfunction "1_1") (pintype "passive"))
      (node (ref "USB2") (pin "SHIELD_4") (pinfunction "P$4_SHIELD_4") (pintype "bidirectional"))
    )
    (net (code "126") (name "OUT0") (class "Default")
      (node (ref "IC23") (pin "4") (pinfunction "P$4_4") (pintype "bidirectional"))
      (node (ref "X1") (pin "P7") (pinfunction "7_P7") (pintype "passive"))
    )
    (net (code "127") (name "OUT00") (class "Default")
      (node (ref "IC16") (pin "22") (pinfunction "AN3/C2INA/RPB3/RB3_22") (pintype "bidirectional"))
      (node (ref "IC23") (pin "2") (pinfunction "P$2_2") (pintype "bidirectional"))
      (node (ref "IC25") (pin "21") (pinfunction "~OC0BXCK0PD1_21") (pintype "bidirectional"))
    )
    (net (code "128") (name "OUT1") (class "Default")
      (node (ref "IC28") (pin "4") (pinfunction "P$4_4") (pintype "bidirectional"))
      (node (ref "X1") (pin "P6") (pinfunction "6_P6") (pintype "passive"))
    )
    (net (code "129") (name "OUT01") (class "Default")
      (node (ref "IC25") (pin "13") (pinfunction "PC3/OC0D/TXD0_13") (pintype "bidirectional"))
      (node (ref "IC28") (pin "2") (pinfunction "P$2_2") (pintype "bidirectional"))
    )
    (net (code "130") (name "OUT2") (class "Default")
      (node (ref "IC29") (pin "4") (pinfunction "P$4_4") (pintype "bidirectional"))
      (node (ref "X1") (pin "P5") (pinfunction "5_P5") (pintype "passive"))
    )
    (net (code "131") (name "OUT02") (class "Default")
      (node (ref "IC25") (pin "14") (pinfunction "PC4/OC1A/#SS_14") (pintype "bidirectional"))
      (node (ref "IC29") (pin "2") (pinfunction "P$2_2") (pintype "bidirectional"))
    )
    (net (code "132") (name "OUTL") (class "Default")
      (node (ref "C57") (pin "1") (pinfunction "1_1") (pintype "passive"))
      (node (ref "J3") (pin "P2") (pinfunction "2_P2") (pintype "passive"))
      (node (ref "R38") (pin "2") (pinfunction "2_2") (pintype "passive"))
    )
    (net (code "133") (name "OUTR") (class "Default")
      (node (ref "C81") (pin "1") (pinfunction "1_1") (pintype "passive"))
      (node (ref "J4") (pin "P2") (pinfunction "2_P2") (pintype "passive"))
      (node (ref "R54") (pin "2") (pinfunction "2_2") (pintype "passive"))
    )
    (net (code "134") (name "PAR0") (class "Default")
      (node (ref "IC16") (pin "17") (pinfunction "TMS/EBIA16/AN24/RA0_17") (pintype "bidirectional"))
      (node (ref "IC25") (pin "40") (pinfunction "PA0/ADC0/AREF_40") (pintype "bidirectional"))
    )
    (net (code "135") (name "PAR1") (class "Default")
      (node (ref "IC16") (pin "38") (pinfunction "TCK/EBIA19/AN29/RA1_38") (pintype "bidirectional"))
      (node (ref "IC25") (pin "41") (pinfunction "PA1/ADC1_41") (pintype "bidirectional"))
    )
    (net (code "136") (name "PAR2") (class "Default")
      (node (ref "IC16") (pin "59") (pinfunction "~{EBICS0}/SCL2/RA2_59") (pintype "bidirectional"))
      (node (ref "IC25") (pin "42") (pinfunction "PA2/ADC2_42") (pintype "bidirectional"))
    )
    (net (code "137") (name "PAR3") (class "Default")
      (node (ref "IC16") (pin "60") (pinfunction "EBIRDY1/SDA2/RA3_60") (pintype "bidirectional"))
      (node (ref "IC25") (pin "43") (pinfunction "PA3/ADC3_43") (pintype "bidirectional"))
    )
    (net (code "138") (name "PAR4") (class "Default")
      (node (ref "IC16") (pin "61") (pinfunction "EBIA14/PMCS1/PMA14/RA4_61") (pintype "bidirectional"))
      (node (ref "IC25") (pin "44") (pinfunction "PA4/ADC4_44") (pintype "bidirectional"))
    )
    (net (code "139") (name "PAR5") (class "Default")
      (node (ref "IC16") (pin "2") (pinfunction "EBIA5/AN34/PMA5/RA5_2") (pintype "bidirectional"))
      (node (ref "IC25") (pin "1") (pinfunction "PA5/ADC5_1") (pintype "bidirectional"))
    )
    (net (code "140") (name "PAR6") (class "Default")
      (node (ref "IC16") (pin "89") (pinfunction "TRCLK/SQICLK/RA6_89") (pintype "bidirectional"))
      (node (ref "IC25") (pin "2") (pinfunction "PA6/ADC6_2") (pintype "bidirectional"))
    )
    (net (code "141") (name "PAR7") (class "Default")
      (node (ref "IC16") (pin "90") (pinfunction "TRD3/SQID3/RA7_90") (pintype "bidirectional"))
      (node (ref "IC25") (pin "3") (pinfunction "PA7/ADC7/AC0-OUT_3") (pintype "bidirectional"))
    )
    (net (code "142") (name "PDI-CLK") (class "Default")
      (node (ref "IC25") (pin "35") (pinfunction "RESET/PDI-CLK_35") (pintype "input"))
      (node (ref "PDI") (pin "5") (pinfunction "5_5") (pintype "passive"))
    )
    (net (code "143") (name "PDI-DATA") (class "Default")
      (node (ref "IC25") (pin "34") (pinfunction "PDI-DATA_34") (pintype "bidirectional"))
      (node (ref "PDI") (pin "1") (pinfunction "1_1") (pintype "passive"))
    )
    (net (code "144") (name "PGEC2") (class "Default")
      (node (ref "IC16") (pin "26") (pinfunction "PGEC2/AN46/RPB6/RB6_26") (pintype "bidirectional"))
      (node (ref "JP1") (pin "5") (pinfunction "5_5") (pintype "passive"))
    )
    (net (code "145") (name "PGED2") (class "Default")
      (node (ref "IC16") (pin "27") (pinfunction "PGED2/AN47/RPB7/RB7_27") (pintype "bidirectional"))
      (node (ref "JP1") (pin "4") (pinfunction "4_4") (pintype "passive"))
    )
    (net (code "146") (name "PMD0") (class "Default")
      (node (ref "IC13") (pin "P29") (pinfunction "I/O0_P29") (pintype "bidirectional"))
      (node (ref "IC16") (pin "91") (pinfunction "EBID0/PMD0/RE0_91") (pintype "bidirectional"))
    )
    (net (code "147") (name "PMD1") (class "Default")
      (node (ref "IC13") (pin "P30") (pinfunction "I/O1_P30") (pintype "bidirectional"))
      (node (ref "IC16") (pin "94") (pinfunction "EBID1/PMD1/RE1_94") (pintype "bidirectional"))
    )
    (net (code "148") (name "PMD2") (class "Default")
      (node (ref "IC13") (pin "P31") (pinfunction "I/O2_P31") (pintype "bidirectional"))
      (node (ref "IC16") (pin "98") (pinfunction "EBID2/PMD2/RE2_98") (pintype "bidirectional"))
    )
    (net (code "149") (name "PMD3") (class "Default")
      (node (ref "IC13") (pin "P32") (pinfunction "I/O3_P32") (pintype "bidirectional"))
      (node (ref "IC16") (pin "99") (pinfunction "EBID3/RPE3/PMD3/RE3_99") (pintype "bidirectional"))
    )
    (net (code "150") (name "PMD4") (class "Default")
      (node (ref "IC13") (pin "P41") (pinfunction "I/O4_P41") (pintype "bidirectional"))
      (node (ref "IC16") (pin "100") (pinfunction "EBID4/AN18/PMD4/RE4_100") (pintype "bidirectional"))
    )
    (net (code "151") (name "PMD5") (class "Default")
      (node (ref "IC13") (pin "P42") (pinfunction "I/O5_P42") (pintype "bidirectional"))
      (node (ref "IC16") (pin "3") (pinfunction "EBID5/AN17/RPE5/PMD5/RE5_3") (pintype "bidirectional"))
    )
    (net (code "152") (name "PMD6") (class "Default")
      (node (ref "IC13") (pin "P43") (pinfunction "I/O6_P43") (pintype "bidirectional"))
      (node (ref "IC16") (pin "4") (pinfunction "EBID6/AN16/PMD6/RE6_4") (pintype "bidirectional"))
    )
    (net (code "153") (name "PMD7") (class "Default")
      (node (ref "IC13") (pin "P44") (pinfunction "I/O7_P44") (pintype "bidirectional"))
      (node (ref "IC16") (pin "5") (pinfunction "EBID7/AN15/PMD7/RE7_5") (pintype "bidirectional"))
    )
    (net (code "154") (name "PMD8") (class "Default")
      (node (ref "IC13") (pin "P26") (pinfunction "I/O8_P26") (pintype "bidirectional"))
    )
    (net (code "155") (name "PMD9") (class "Default")
      (node (ref "IC13") (pin "P27") (pinfunction "I/O9_P27") (pintype "bidirectional"))
    )
    (net (code "156") (name "PMD10") (class "Default")
      (node (ref "IC13") (pin "P28") (pinfunction "I/O10_P28") (pintype "bidirectional"))
    )
    (net (code "157") (name "PMD11") (class "Default")
      (node (ref "IC13") (pin "P33") (pinfunction "I/O11_P33") (pintype "bidirectional"))
    )
    (net (code "158") (name "PMD12") (class "Default")
      (node (ref "IC13") (pin "P40") (pinfunction "I/O12_P40") (pintype "bidirectional"))
    )
    (net (code "159") (name "PMD13") (class "Default")
      (node (ref "IC13") (pin "P45") (pinfunction "I/O13_P45") (pintype "bidirectional"))
    )
    (net (code "160") (name "PMD14") (class "Default")
      (node (ref "IC13") (pin "P46") (pinfunction "I/O14_P46") (pintype "bidirectional"))
    )
    (net (code "161") (name "PMD15") (class "Default")
      (node (ref "IC13") (pin "P47") (pinfunction "I/O15_P47") (pintype "bidirectional"))
    )
    (net (code "162") (name "RE") (class "Default")
      (node (ref "IC13") (pin "P8") (pinfunction "RE#_P8") (pintype "bidirectional"))
      (node (ref "IC16") (pin "9") (pinfunction "~{EBIOE}/AN19/RPC4/PMRD/RC4_9") (pintype "bidirectional"))
    )
    (net (code "163") (name "REFCLK{slash}MCLK") (class "Default")
      (node (ref "IC16") (pin "72") (pinfunction "SOSCI/RPC13/RC13_72") (pintype "bidirectional"))
      (node (ref "IC6") (pin "P27") (pinfunction "MCLK_P27") (pintype "bidirectional"))
    )
    (net (code "164") (name "RTS") (class "Default")
      (node (ref "IC21") (pin "13") (pinfunction "B2_13") (pintype "bidirectional"))
      (node (ref "IC25") (pin "28") (pinfunction "~{OC0ASDAPE0}_28") (pintype "bidirectional"))
    )
    (net (code "165") (name "RXD") (class "Default")
      (node (ref "IC21") (pin "12") (pinfunction "B3_12") (pintype "bidirectional"))
      (node (ref "IC32") (pin "4") (pinfunction "OUT_4") (pintype "bidirectional"))
      (node (ref "IC35") (pin "4") (pinfunction "OUT_4") (pintype "bidirectional"))
    )
    (net (code "166") (name "RXD_") (class "Default")
      (node (ref "IC25") (pin "33") (pinfunction "~TXD0OC0DPE3_33") (pintype "bidirectional"))
      (node (ref "IC35") (pin "2") (pinfunction "IN_2") (pintype "bidirectional"))
    )
    (net (code "167") (name "SCK1") (class "Default")
      (node (ref "IC16") (pin "34") (pinfunction "EBIA13/CVREFOUT/AN5/RPB10/PMA13/RB10_34") (pintype "bidirectional"))
      (node (ref "IC6") (pin "P26") (pinfunction "CCLK_P26") (pintype "bidirectional"))
    )
    (net (code "168") (name "SCK{slash}BIT_CLK") (class "Default")
      (node (ref "IC16") (pin "69") (pinfunction "RPD10/SCK4/RD10_69") (pintype "bidirectional"))
      (node (ref "IC6") (pin "P3") (pinfunction "BCLK/EF_BCLK_P3") (pintype "bidirectional"))
    )
    (net (code "169") (name "SDO1") (class "Default")
      (node (ref "IC16") (pin "33") (pinfunction "EBIA7/AN49/RPB9/PMA7/RB9_33") (pintype "bidirectional"))
      (node (ref "IC6") (pin "P24") (pinfunction "CDATA_P24") (pintype "bidirectional"))
    )
    (net (code "170") (name "SDO{slash}SD") (class "Default")
      (node (ref "IC16") (pin "70") (pinfunction "EMDC/AEMDC/RPD11/RD11_70") (pintype "bidirectional"))
      (node (ref "IC6") (pin "P4") (pinfunction "SDATA/EF_LDATA_P4") (pintype "bidirectional"))
    )
    (net (code "171") (name "SS{slash}WORD_CLK") (class "Default")
      (node (ref "IC16") (pin "68") (pinfunction "EBIA15/RPD9/PMCS2/PMA15/RD9_68") (pintype "bidirectional"))
      (node (ref "IC6") (pin "P2") (pinfunction "LRCLK/EF-WCLK_P2") (pintype "bidirectional"))
    )
    (net (code "172") (name "STATE") (class "Default")
      (node (ref "IC25") (pin "36") (pinfunction "PR0/XTAL2_36") (pintype "bidirectional"))
      (node (ref "R66") (pin "2") (pinfunction "2_2") (pintype "passive"))
    )
    (net (code "173") (name "TP0") (class "Default")
      (node (ref "IC16") (pin "96") (pinfunction "TRD1/SQID1/RG12_96") (pintype "bidirectional"))
      (node (ref "TP0") (pin "TP") (pinfunction "TP_TP") (pintype "input"))
    )
    (net (code "174") (name "TP1") (class "Default")
      (node (ref "IC16") (pin "97") (pinfunction "TRD0/SQID0/RG13_97") (pintype "bidirectional"))
      (node (ref "TP1") (pin "TP") (pinfunction "TP_TP") (pintype "input"))
    )
    (net (code "175") (name "TXD") (class "Default")
      (node (ref "IC21") (pin "14") (pinfunction "B1_14") (pintype "bidirectional"))
      (node (ref "IC25") (pin "32") (pinfunction "~RXD0OC0CPE2_32") (pintype "bidirectional"))
      (node (ref "IC33") (pin "2") (pinfunction "IN_2") (pintype "bidirectional"))
    )
    (net (code "176") (name "UART1_RX") (class "Default")
      (node (ref "IC25") (pin "23") (pinfunction "~OC0DTXD0PD3_23") (pintype "bidirectional"))
    )
    (net (code "177") (name "UART1_TX") (class "Default")
      (node (ref "IC25") (pin "22") (pinfunction "~OC0CRXD0PD2_22") (pintype "bidirectional"))
    )
    (net (code "178") (name "UART2_RX") (class "Default")
      (node (ref "IC16") (pin "7") (pinfunction "EBIA12/AN21/RPC2/PMA12/RC2_7") (pintype "bidirectional"))
      (node (ref "IC25") (pin "26") (pinfunction "~RXD1MISOPD6_26") (pintype "bidirectional"))
      (node (ref "IC33") (pin "4") (pinfunction "OUT_4") (pintype "bidirectional"))
    )
    (net (code "179") (name "UART2_TX") (class "Default")
      (node (ref "IC16") (pin "25") (pinfunction "PGED1/AN0/RPB0/RB0_25") (pintype "bidirectional"))
      (node (ref "IC25") (pin "27") (pinfunction "~~{TXD1SCKCLKOPD7}_27") (pintype "bidirectional"))
      (node (ref "IC32") (pin "2") (pinfunction "IN_2") (pintype "bidirectional"))
    )
    (net (code "180") (name "UC_IO0") (class "Default")
      (node (ref "IC16") (pin "20") (pinfunction "AN45/C1INA/RPB5/RB5_20") (pintype "bidirectional"))
      (node (ref "IC25") (pin "11") (pinfunction "PC1/OC0B/XCK0/SCL_11") (pintype "bidirectional"))
    )
    (net (code "181") (name "UC_IO1") (class "Default")
      (node (ref "IC16") (pin "21") (pinfunction "AN4/C1INB/RB4_21") (pintype "bidirectional"))
      (node (ref "IC25") (pin "15") (pinfunction "PC5/OC1B/MOSI/XCK1_15") (pintype "bidirectional"))
    )
    (net (code "182") (name "UC_IO2") (class "Default")
      (node (ref "IC16") (pin "10") (pinfunction "AN14/C1IND/ECOL/RPG6/SCK2/RG6_10") (pintype "bidirectional"))
      (node (ref "IC25") (pin "16") (pinfunction "PC6/MISO/RXD1_16") (pintype "bidirectional"))
    )
    (net (code "183") (name "UC_IO3") (class "Default")
      (node (ref "IC16") (pin "24") (pinfunction "PGEC1/AN1/RPB1/RB1_24") (pintype "bidirectional"))
      (node (ref "IC25") (pin "17") (pinfunction "PC7/SCK/TXD1/CLKO/EVO_17") (pintype "bidirectional"))
      (node (ref "IC32") (pin "1") (pinfunction "OE_1") (pintype "bidirectional"))
      (node (ref "IC33") (pin "1") (pinfunction "OE_1") (pintype "bidirectional"))
      (node (ref "IC35") (pin "1") (pinfunction "~{OE}_1") (pintype "bidirectional"))
      (node (ref "R89") (pin "1") (pinfunction "1_1") (pintype "passive"))
    )
    (net (code "184") (name "UC_IO4") (class "Default")
      (node (ref "IC16") (pin "23") (pinfunction "AN2/C2INB/RPB2/RB2_23") (pintype "bidirectional"))
      (node (ref "IC25") (pin "25") (pinfunction "~XCK1MOSIPD5_25") (pintype "bidirectional"))
    )
    (net (code "185") (name "USB") (class "Default")
      (node (ref "IC16") (pin "85") (pinfunction "EBID11/ETXD1/RPF0/PMD11/RF0_85") (pintype "bidirectional"))
      (node (ref "R77") (pin "2") (pinfunction "2_2") (pintype "passive"))
    )
    (net (code "186") (name "USB5V") (class "Default")
      (node (ref "C111") (pin "1") (pinfunction "1_1") (pintype "passive"))
      (node (ref "C112") (pin "+") (pinfunction "+_+") (pintype "passive"))
      (node (ref "C114") (pin "1") (pinfunction "1_1") (pintype "passive"))
      (node (ref "C117") (pin "1") (pinfunction "1_1") (pintype "passive"))
      (node (ref "IC19") (pin "20") (pinfunction "VCC_20") (pintype "power_in"))
      (node (ref "IC19") (pin "4") (pinfunction "VCCIO_4") (pintype "power_in"))
      (node (ref "IC21") (pin "1") (pinfunction "VDD1_1") (pintype "bidirectional"))
      (node (ref "IC21") (pin "7") (pinfunction "NC/EN_7") (pintype "bidirectional"))
      (node (ref "L10") (pin "1") (pinfunction "1_1") (pintype "passive"))
    )
    (net (code "187") (name "USBDM") (class "Default")
      (node (ref "C108") (pin "1") (pinfunction "1_1") (pintype "passive"))
      (node (ref "IC17") (pin "P$6") (pinfunction "IO1_P$6") (pintype "bidirectional"))
      (node (ref "IC19") (pin "16") (pinfunction "USBDM_16") (pintype "bidirectional"))
    )
    (net (code "188") (name "USBDP") (class "Default")
      (node (ref "C107") (pin "1") (pinfunction "1_1") (pintype "passive"))
      (node (ref "IC17") (pin "P$4") (pinfunction "IO2_P$4") (pintype "bidirectional"))
      (node (ref "IC19") (pin "15") (pinfunction "USBDP_15") (pintype "bidirectional"))
    )
    (net (code "189") (name "V+") (class "Default")
      (node (ref "C11") (pin "1") (pinfunction "1_1") (pintype "passive"))
      (node (ref "C2") (pin "+") (pinfunction "+_+") (pintype "passive"))
      (node (ref "IC2") (pin "17") (pinfunction "PVIN1_17") (pintype "bidirectional"))
      (node (ref "IC2") (pin "18") (pinfunction "PVINSYS_18") (pintype "bidirectional"))
      (node (ref "IC2") (pin "19") (pinfunction "PVIN2_19") (pintype "bidirectional"))
      (node (ref "JACK") (pin "P1") (pinfunction "1_P1") (pintype "passive"))
      (node (ref "L5") (pin "1") (pinfunction "1_1") (pintype "passive"))
      (node (ref "L6") (pin "1") (pinfunction "1_1") (pintype "passive"))
      (node (ref "L9") (pin "1") (pinfunction "1_1") (pintype "passive"))
    )
    (net (code "190") (name "VBUS") (class "Default")
      (node (ref "IC16") (pin "51") (pinfunction "VBUS_51") (pintype "bidirectional"))
      (node (ref "L13") (pin "1") (pinfunction "1_1") (pintype "passive"))
    )
    (net (code "191") (name "VCC") (class "Default")
      (node (ref "C100") (pin "1") (pinfunction "1_1") (pintype "passive"))
      (node (ref "C102") (pin "1") (pinfunction "1_1") (pintype "passive"))
      (node (ref "C139") (pin "1") (pinfunction "1_1") (pintype "passive"))
      (node (ref "C84") (pin "1") (pinfunction "1_1") (pintype "passive"))
      (node (ref "C86") (pin "1") (pinfunction "1_1") (pintype "passive"))
      (node (ref "C88") (pin "1") (pinfunction "1_1") (pintype "passive"))
      (node (ref "C89") (pin "1") (pinfunction "1_1") (pintype "passive"))
      (node (ref "C92") (pin "1") (pinfunction "1_1") (pintype "passive"))
      (node (ref "C93") (pin "1") (pinfunction "1_1") (pintype "passive"))
      (node (ref "C94") (pin "1") (pinfunction "1_1") (pintype "passive"))
      (node (ref "C95") (pin "1") (pinfunction "1_1") (pintype "passive"))
      (node (ref "C96") (pin "1") (pinfunction "1_1") (pintype "passive"))
      (node (ref "C97") (pin "1") (pinfunction "1_1") (pintype "passive"))
      (node (ref "C98") (pin "1") (pinfunction "1_1") (pintype "passive"))
      (node (ref "C99") (pin "1") (pinfunction "1_1") (pintype "passive"))
      (node (ref "IC13") (pin "P12") (pinfunction "VCC_P12") (pintype "bidirectional"))
      (node (ref "IC13") (pin "P37") (pinfunction "VCC_P37") (pintype "bidirectional"))
      (node (ref "IC13") (pin "P39") (pinfunction "VCC_P39") (pintype "bidirectional"))
      (node (ref "IC16") (pin "14") (pinfunction "VDD_14") (pintype "bidirectional"))
      (node (ref "IC16") (pin "30") (pinfunction "AVDD_30") (pintype "bidirectional"))
      (node (ref "IC16") (pin "37") (pinfunction "VDD_37") (pintype "bidirectional"))
      (node (ref "IC16") (pin "46") (pinfunction "VDD_46") (pintype "bidirectional"))
      (node (ref "IC16") (pin "52") (pinfunction "VUSB3V3_52") (pintype "bidirectional"))
      (node (ref "IC16") (pin "62") (pinfunction "VDD_62") (pintype "bidirectional"))
      (node (ref "IC16") (pin "74") (pinfunction "VDD_74") (pintype "bidirectional"))
      (node (ref "IC16") (pin "83") (pinfunction "VDD_83") (pintype "bidirectional"))
      (node (ref "IC16") (pin "93") (pinfunction "VDD_93") (pintype "bidirectional"))
      (node (ref "IC18") (pin "5") (pinfunction "OUT_5") (pintype "bidirectional"))
      (node (ref "JP1") (pin "2") (pinfunction "2_2") (pintype "passive"))
      (node (ref "OSC1") (pin "P$4") (pinfunction "VDD_P$4") (pintype "passive"))
      (node (ref "OSC3") (pin "P$1") (pinfunction "STANDBY#_P$1") (pintype "passive"))
      (node (ref "OSC3") (pin "P$4") (pinfunction "VDD_P$4") (pintype "passive"))
      (node (ref "R56") (pin "2") (pinfunction "2_2") (pintype "passive"))
      (node (ref "R80") (pin "2") (pinfunction "2_2") (pintype "passive"))
    )
    (net (code "192") (name "VCCINT") (class "Default")
      (node (ref "C120") (pin "1") (pinfunction "1_1") (pintype "passive"))
      (node (ref "C133") (pin "1") (pinfunction "1_1") (pintype "passive"))
      (node (ref "C134") (pin "1") (pinfunction "1_1") (pintype "passive"))
      (node (ref "IC23") (pin "5") (pinfunction "P$5_5") (pintype "bidirectional"))
      (node (ref "IC28") (pin "5") (pinfunction "P$5_5") (pintype "bidirectional"))
      (node (ref "IC29") (pin "5") (pinfunction "P$5_5") (pintype "bidirectional"))
      (node (ref "JP2") (pin "2") (pinfunction "2_2") (pintype "passive"))
    )
    (net (code "193") (name "VCCIO") (class "Default")
      (node (ref "C104") (pin "1") (pinfunction "1_1") (pintype "passive"))
      (node (ref "C105") (pin "1") (pinfunction "1_1") (pintype "passive"))
      (node (ref "C116") (pin "1") (pinfunction "1_1") (pintype "passive"))
      (node (ref "C118") (pin "1") (pinfunction "1_1") (pintype "passive"))
      (node (ref "C119") (pin "1") (pinfunction "1_1") (pintype "passive"))
      (node (ref "C121") (pin "1") (pinfunction "1_1") (pintype "passive"))
      (node (ref "C123") (pin "1") (pinfunction "1_1") (pintype "passive"))
      (node (ref "C126") (pin "1") (pinfunction "1_1") (pintype "passive"))
      (node (ref "C127") (pin "1") (pinfunction "1_1") (pintype "passive"))
      (node (ref "C128") (pin "1") (pinfunction "1_1") (pintype "passive"))
      (node (ref "C130") (pin "1") (pinfunction "1_1") (pintype "passive"))
      (node (ref "C132") (pin "1") (pinfunction "1_1") (pintype "passive"))
      (node (ref "C135") (pin "1") (pinfunction "1_1") (pintype "passive"))
      (node (ref "C136") (pin "1") (pinfunction "1_1") (pintype "passive"))
      (node (ref "C143") (pin "1") (pinfunction "1_1") (pintype "passive"))
      (node (ref "C146") (pin "1") (pinfunction "1_1") (pintype "passive"))
      (node (ref "C147") (pin "1") (pinfunction "1_1") (pintype "passive"))
      (node (ref "CLKIN") (pin "1") (pinfunction "1_1") (pintype "passive"))
      (node (ref "IC20") (pin "5") (pinfunction "OUT_5") (pintype "bidirectional"))
      (node (ref "IC21") (pin "10") (pinfunction "NC/EN_10") (pintype "bidirectional"))
      (node (ref "IC21") (pin "16") (pinfunction "VDD2_16") (pintype "bidirectional"))
      (node (ref "IC22") (pin "5") (pinfunction "P$5_5") (pintype "bidirectional"))
      (node (ref "IC24") (pin "5") (pinfunction "P$5_5") (pintype "bidirectional"))
      (node (ref "IC25") (pin "19") (pinfunction "VCC_19") (pintype "power_in"))
      (node (ref "IC25") (pin "31") (pinfunction "VCC_31") (pintype "power_in"))
      (node (ref "IC25") (pin "9") (pinfunction "VCC_9") (pintype "power_in"))
      (node (ref "IC26") (pin "5") (pinfunction "V+_5") (pintype "power_in"))
      (node (ref "IC27") (pin "5") (pinfunction "V+_5") (pintype "power_in"))
      (node (ref "IC30") (pin "5") (pinfunction "P$5_5") (pintype "bidirectional"))
      (node (ref "IC31") (pin "5") (pinfunction "P$5_5") (pintype "bidirectional"))
      (node (ref "IC32") (pin "5") (pinfunction "VCC_5") (pintype "bidirectional"))
      (node (ref "IC33") (pin "5") (pinfunction "VCC_5") (pintype "bidirectional"))
      (node (ref "IC35") (pin "5") (pinfunction "VCC_5") (pintype "bidirectional"))
      (node (ref "JP2") (pin "3") (pinfunction "3_3") (pintype "passive"))
      (node (ref "L12") (pin "1") (pinfunction "1_1") (pintype "passive"))
      (node (ref "OSC2") (pin "P$4") (pinfunction "VDD_P$4") (pintype "passive"))
      (node (ref "PDI") (pin "2") (pinfunction "2_2") (pintype "passive"))
      (node (ref "R9") (pin "2") (pinfunction "2_2") (pintype "passive"))
    )
    (net (code "194") (name "VREF") (class "Default")
      (node (ref "C34") (pin "1") (pinfunction "1_1") (pintype "passive"))
      (node (ref "C35") (pin "+") (pinfunction "+_+") (pintype "passive"))
      (node (ref "R21") (pin "1") (pinfunction "1_1") (pintype "passive"))
      (node (ref "R22") (pin "2") (pinfunction "2_2") (pintype "passive"))
      (node (ref "R24") (pin "2") (pinfunction "2_2") (pintype "passive"))
      (node (ref "R25") (pin "2") (pinfunction "2_2") (pintype "passive"))
      (node (ref "R40") (pin "2") (pinfunction "2_2") (pintype "passive"))
      (node (ref "R41") (pin "2") (pinfunction "2_2") (pintype "passive"))
    )
    (net (code "195") (name "WE") (class "Default")
      (node (ref "IC13") (pin "P18") (pinfunction "WE#_P18") (pintype "bidirectional"))
      (node (ref "IC16") (pin "8") (pinfunction "~{EBIWE}/AN20/RPC3/PMWR/RC3_8") (pintype "bidirectional"))
    )
    (net (code "196") (name "WP") (class "Default")
      (node (ref "IC13") (pin "P19") (pinfunction "WP#_P19") (pintype "bidirectional"))
      (node (ref "IC16") (pin "12") (pinfunction "EBIA3/AN12/C2IND/ERXDV/ECRSDV..._12") (pintype "bidirectional"))
    )
    (net (code "197") (name "ZEROL") (class "Default")
      (node (ref "IC16") (pin "56") (pinfunction "RPF3/USBID/RF3_56") (pintype "bidirectional"))
      (node (ref "IC6") (pin "P21") (pinfunction "ZEROL_P21") (pintype "bidirectional"))
    )
    (net (code "198") (name "ZEROR") (class "Default")
      (node (ref "IC16") (pin "58") (pinfunction "EBIRDY2/RPF8/SCL3/RF8_58") (pintype "bidirectional"))
      (node (ref "IC6") (pin "P20") (pinfunction "ZEROR_P20") (pintype "bidirectional"))
    )
    (net (code "199") (name "unconnected-(IC2-SEQ-Pad5)") (class "Default")
      (node (ref "IC2") (pin "5") (pinfunction "SEQ_5") (pintype "bidirectional"))
    )
    (net (code "200") (name "unconnected-(IC2-SS-Pad10)") (class "Default")
      (node (ref "IC2") (pin "10") (pinfunction "SS_10") (pintype "bidirectional"))
    )
    (net (code "201") (name "unconnected-(IC6-DSD_LDATA-PadP7)") (class "Default")
      (node (ref "IC6") (pin "P7") (pinfunction "DSD_LDATA_P7") (pintype "bidirectional"))
    )
    (net (code "202") (name "unconnected-(IC6-DSD_RDATA-PadP8)") (class "Default")
      (node (ref "IC6") (pin "P8") (pinfunction "DSD_RDATA_P8") (pintype "bidirectional"))
    )
    (net (code "203") (name "unconnected-(IC6-DSD_SCLK-PadP6)") (class "Default")
      (node (ref "IC6") (pin "P6") (pinfunction "DSD_SCLK_P6") (pintype "bidirectional"))
    )
    (net (code "204") (name "unconnected-(IC6-EF_RDATA-PadP5)") (class "Default")
      (node (ref "IC6") (pin "P5") (pinfunction "EF_RDATA_P5") (pintype "bidirectional"))
    )
    (net (code "205") (name "unconnected-(IC7-COMP-Pad8)") (class "Default")
      (node (ref "IC7") (pin "8") (pinfunction "COMP_8") (pintype "bidirectional"))
    )
    (net (code "206") (name "unconnected-(IC7-NL+-Pad1)") (class "Default")
      (node (ref "IC7") (pin "1") (pinfunction "NL+_1") (pintype "bidirectional"))
    )
    (net (code "207") (name "unconnected-(IC7-NL--Pad5)") (class "Default")
      (node (ref "IC7") (pin "5") (pinfunction "NL-_5") (pintype "bidirectional"))
    )
    (net (code "208") (name "unconnected-(IC8-COMP-Pad8)") (class "Default")
      (node (ref "IC8") (pin "8") (pinfunction "COMP_8") (pintype "bidirectional"))
    )
    (net (code "209") (name "unconnected-(IC8-NL+-Pad1)") (class "Default")
      (node (ref "IC8") (pin "1") (pinfunction "NL+_1") (pintype "bidirectional"))
    )
    (net (code "210") (name "unconnected-(IC8-NL--Pad5)") (class "Default")
      (node (ref "IC8") (pin "5") (pinfunction "NL-_5") (pintype "bidirectional"))
    )
    (net (code "211") (name "unconnected-(IC9-COMP-Pad8)") (class "Default")
      (node (ref "IC9") (pin "8") (pinfunction "COMP_8") (pintype "bidirectional"))
    )
    (net (code "212") (name "unconnected-(IC9-NL+-Pad1)") (class "Default")
      (node (ref "IC9") (pin "1") (pinfunction "NL+_1") (pintype "bidirectional"))
    )
    (net (code "213") (name "unconnected-(IC9-NL--Pad5)") (class "Default")
      (node (ref "IC9") (pin "5") (pinfunction "NL-_5") (pintype "bidirectional"))
    )
    (net (code "214") (name "unconnected-(IC10-COMP-Pad8)") (class "Default")
      (node (ref "IC10") (pin "8") (pinfunction "COMP_8") (pintype "bidirectional"))
    )
    (net (code "215") (name "unconnected-(IC10-NL+-Pad1)") (class "Default")
      (node (ref "IC10") (pin "1") (pinfunction "NL+_1") (pintype "bidirectional"))
    )
    (net (code "216") (name "unconnected-(IC10-NL--Pad5)") (class "Default")
      (node (ref "IC10") (pin "5") (pinfunction "NL-_5") (pintype "bidirectional"))
    )
    (net (code "217") (name "unconnected-(IC11-COMP-Pad8)") (class "Default")
      (node (ref "IC11") (pin "8") (pinfunction "COMP_8") (pintype "bidirectional"))
    )
    (net (code "218") (name "unconnected-(IC11-NL+-Pad1)") (class "Default")
      (node (ref "IC11") (pin "1") (pinfunction "NL+_1") (pintype "bidirectional"))
    )
    (net (code "219") (name "unconnected-(IC11-NL--Pad5)") (class "Default")
      (node (ref "IC11") (pin "5") (pinfunction "NL-_5") (pintype "bidirectional"))
    )
    (net (code "220") (name "unconnected-(IC12-COMP-Pad8)") (class "Default")
      (node (ref "IC12") (pin "8") (pinfunction "COMP_8") (pintype "bidirectional"))
    )
    (net (code "221") (name "unconnected-(IC12-NL+-Pad1)") (class "Default")
      (node (ref "IC12") (pin "1") (pinfunction "NL+_1") (pintype "bidirectional"))
    )
    (net (code "222") (name "unconnected-(IC12-NL--Pad5)") (class "Default")
      (node (ref "IC12") (pin "5") (pinfunction "NL-_5") (pintype "bidirectional"))
    )
    (net (code "223") (name "unconnected-(IC13-NC-PadP1)") (class "Default")
      (node (ref "IC13") (pin "P1") (pinfunction "NC_P1") (pintype "bidirectional"))
    )
    (net (code "224") (name "unconnected-(IC13-NC-PadP2)") (class "Default")
      (node (ref "IC13") (pin "P2") (pinfunction "NC_P2") (pintype "bidirectional"))
    )
    (net (code "225") (name "unconnected-(IC13-NC-PadP3)") (class "Default")
      (node (ref "IC13") (pin "P3") (pinfunction "NC_P3") (pintype "bidirectional"))
    )
    (net (code "226") (name "unconnected-(IC13-NC-PadP4)") (class "Default")
      (node (ref "IC13") (pin "P4") (pinfunction "NC_P4") (pintype "bidirectional"))
    )
    (net (code "227") (name "unconnected-(IC13-NC-PadP5)") (class "Default")
      (node (ref "IC13") (pin "P5") (pinfunction "NC_P5") (pintype "bidirectional"))
    )
    (net (code "228") (name "unconnected-(IC13-NC-PadP6)") (class "Default")
      (node (ref "IC13") (pin "P6") (pinfunction "NC_P6") (pintype "bidirectional"))
    )
    (net (code "229") (name "unconnected-(IC13-NC-PadP10)") (class "Default")
      (node (ref "IC13") (pin "P10") (pinfunction "NC_P10") (pintype "bidirectional"))
    )
    (net (code "230") (name "unconnected-(IC13-NC-PadP11)") (class "Default")
      (node (ref "IC13") (pin "P11") (pinfunction "NC_P11") (pintype "bidirectional"))
    )
    (net (code "231") (name "unconnected-(IC13-NC-PadP14)") (class "Default")
      (node (ref "IC13") (pin "P14") (pinfunction "NC_P14") (pintype "bidirectional"))
    )
    (net (code "232") (name "unconnected-(IC13-NC-PadP15)") (class "Default")
      (node (ref "IC13") (pin "P15") (pinfunction "NC_P15") (pintype "bidirectional"))
    )
    (net (code "233") (name "unconnected-(IC13-NC-PadP20)") (class "Default")
      (node (ref "IC13") (pin "P20") (pinfunction "NC_P20") (pintype "bidirectional"))
    )
    (net (code "234") (name "unconnected-(IC13-NC-PadP21)") (class "Default")
      (node (ref "IC13") (pin "P21") (pinfunction "NC_P21") (pintype "bidirectional"))
    )
    (net (code "235") (name "unconnected-(IC13-NC-PadP22)") (class "Default")
      (node (ref "IC13") (pin "P22") (pinfunction "NC_P22") (pintype "bidirectional"))
    )
    (net (code "236") (name "unconnected-(IC13-NC-PadP23)") (class "Default")
      (node (ref "IC13") (pin "P23") (pinfunction "NC_P23") (pintype "bidirectional"))
    )
    (net (code "237") (name "unconnected-(IC13-NC-PadP24)") (class "Default")
      (node (ref "IC13") (pin "P24") (pinfunction "NC_P24") (pintype "bidirectional"))
    )
    (net (code "238") (name "unconnected-(IC13-NC-PadP35)") (class "Default")
      (node (ref "IC13") (pin "P35") (pinfunction "NC_P35") (pintype "bidirectional"))
    )
    (net (code "239") (name "unconnected-(IC13-NC-PadP38)") (class "Default")
      (node (ref "IC13") (pin "P38") (pinfunction "NC_P38") (pintype "bidirectional"))
    )
    (net (code "240") (name "unconnected-(IC13-VCC-PadP34)") (class "Default")
      (node (ref "IC13") (pin "P34") (pinfunction "VCC_P34") (pintype "bidirectional"))
    )
    (net (code "241") (name "unconnected-(IC16-AETXCLK{slash}RPA14{slash}SCL1{slash}RA14-Pad66)") (class "Default")
      (node (ref "IC16") (pin "66") (pinfunction "AETXCLK/RPA14/SCL1/RA14_66") (pintype "bidirectional"))
    )
    (net (code "242") (name "unconnected-(IC16-AETXEN{slash}RPA15{slash}SDA1{slash}RA15-Pad67)") (class "Default")
      (node (ref "IC16") (pin "67") (pinfunction "AETXEN/RPA15/SDA1/RA15_67") (pintype "bidirectional"))
    )
    (net (code "243") (name "unconnected-(IC16-AN6{slash}ERXERR{slash}AETXERR{slash}RB11-Pad35)") (class "Default")
      (node (ref "IC16") (pin "35") (pinfunction "AN6/ERXERR/AETXERR/RB11_35") (pintype "input"))
    )
    (net (code "244") (name "unconnected-(IC16-AN23{slash}AERXERR{slash}RG15-Pad1)") (class "Default")
      (node (ref "IC16") (pin "1") (pinfunction "AN23/AERXERR/RG15_1") (pintype "bidirectional"))
    )
    (net (code "245") (name "unconnected-(IC16-AN25{slash}AERXD0{slash}RPE8{slash}RE8-Pad18)") (class "Default")
      (node (ref "IC16") (pin "18") (pinfunction "AN25/AERXD0/RPE8/RE8_18") (pintype "bidirectional"))
    )
    (net (code "246") (name "unconnected-(IC16-AN26{slash}AERXD1{slash}RPE9{slash}RE9-Pad19)") (class "Default")
      (node (ref "IC16") (pin "19") (pinfunction "AN26/AERXD1/RPE9/RE9_19") (pintype "bidirectional"))
    )
    (net (code "247") (name "unconnected-(IC16-AN32{slash}AETXD0{slash}RPD14{slash}RD14-Pad47)") (class "Default")
      (node (ref "IC16") (pin "47") (pinfunction "AN32/AETXD0/RPD14/RD14_47") (pintype "bidirectional"))
    )
    (net (code "248") (name "unconnected-(IC16-AN33{slash}AETXD1{slash}RPD15{slash}SCK6{slash}RD15-Pad48)") (class "Default")
      (node (ref "IC16") (pin "48") (pinfunction "AN33/AETXD1/RPD15/SCK6/RD15_48") (pintype "bidirectional"))
    )
    (net (code "249") (name "unconnected-(IC16-EBIA0{slash}AN10{slash}ERXD3{slash}AETXD2{slash}RPB15{slash}OCFB{slash}PMA0{slash}RB15-Pad44)") (class "Default")
      (node (ref "IC16") (pin "44") (pinfunction "EBIA0/AN10/ERXD3/AETXD2/RPB15/OCFB/PMA0/RB15_44") (pintype "bidirectional"))
    )
    (net (code "250") (name "unconnected-(IC16-EBIA1{slash}AN9{slash}ERXD2{slash}AETXD3{slash}RPB14{slash}SCK3{slash}PMA1{slash}RB14-Pad43)") (class "Default")
      (node (ref "IC16") (pin "43") (pinfunction "EBIA1/AN9/ERXD2/AETXD3/RPB14/SCK3/PMA1/RB14_43") (pintype "bidirectional"))
    )
    (net (code "251") (name "unconnected-(IC16-EBIA6{slash}AN22{slash}RPC1{slash}PMA6{slash}RC1-Pad6)") (class "Default")
      (node (ref "IC16") (pin "6") (pinfunction "EBIA6/AN22/RPC1/PMA6/RC1_6") (pintype "bidirectional"))
    )
    (net (code "252") (name "unconnected-(IC16-EBIA9{slash}RPF4{slash}SDA5{slash}PMA9{slash}RF4-Pad64)") (class "Default")
      (node (ref "IC16") (pin "64") (pinfunction "EBIA9/RPF4/SDA5/PMA9/RF4_64") (pintype "bidirectional"))
    )
    (net (code "253") (name "unconnected-(IC16-EBID8{slash}RPG0{slash}PMD8{slash}RG0-Pad88)") (class "Default")
      (node (ref "IC16") (pin "88") (pinfunction "EBID8/RPG0/PMD8/RG0_88") (pintype "input"))
    )
    (net (code "254") (name "unconnected-(IC16-EBID9{slash}ETXERR{slash}RPG1{slash}PMD9{slash}RG1-Pad87)") (class "Default")
      (node (ref "IC16") (pin "87") (pinfunction "EBID9/ETXERR/RPG1/PMD9/RG1_87") (pintype "bidirectional"))
    )
    (net (code "255") (name "unconnected-(IC16-EBID15{slash}ETXCLK{slash}RPD3...-Pad78)") (class "Default")
      (node (ref "IC16") (pin "78") (pinfunction "EBID15/ETXCLK/RPD3..._78") (pintype "bidirectional"))
    )
    (net (code "256") (name "unconnected-(IC16-OSC2{slash}CLKO{slash}RC15-Pad50)") (class "Default")
      (node (ref "IC16") (pin "50") (pinfunction "OSC2/CLKO/RC15_50") (pintype "bidirectional"))
    )
    (net (code "257") (name "unconnected-(IC16-TDI{slash}EBIA18{slash}AN30{slash}RPF13{slash}SCK5{slash}RF13-Pad39)") (class "Default")
      (node (ref "IC16") (pin "39") (pinfunction "TDI/EBIA18/AN30/RPF13/SCK5/RF13_39") (pintype "bidirectional"))
    )
    (net (code "258") (name "unconnected-(IC16-TDO{slash}EBIA17{slash}AN31{slash}RPF12{slash}RF12-Pad40)") (class "Default")
      (node (ref "IC16") (pin "40") (pinfunction "TDO/EBIA17/AN31/RPF12/RF12_40") (pintype "bidirectional"))
    )
    (net (code "259") (name "unconnected-(IC16-VREF+{slash}CVREF+{slash}AN28{slash}AERXD3{slash}RA10-Pad29)") (class "Default")
      (node (ref "IC16") (pin "29") (pinfunction "VREF+/CVREF+/AN28/AERXD3/RA10_29") (pintype "bidirectional"))
    )
    (net (code "260") (name "unconnected-(IC16-VREF-{slash}CVREF-{slash}AN27{slash}AERXD2{slash}RA9-Pad28)") (class "Default")
      (node (ref "IC16") (pin "28") (pinfunction "VREF-/CVREF-/AN27/AERXD2/RA9_28") (pintype "bidirectional"))
    )
    (net (code "261") (name "unconnected-(IC16-~{SQICS1}{slash}RPD5{slash}RD5-Pad82)") (class "Default")
      (node (ref "IC16") (pin "82") (pinfunction "~{SQICS1}/RPD5/RD5_82") (pintype "bidirectional"))
    )
    (net (code "262") (name "unconnected-(IC18-N{slash}C-Pad4)") (class "Default")
      (node (ref "IC18") (pin "4") (pinfunction "N/C_4") (pintype "bidirectional"))
    )
    (net (code "263") (name "unconnected-(IC19-CBUS0-Pad23)") (class "Default")
      (node (ref "IC19") (pin "23") (pinfunction "CBUS0_23") (pintype "bidirectional"))
    )
    (net (code "264") (name "unconnected-(IC19-CBUS1-Pad22)") (class "Default")
      (node (ref "IC19") (pin "22") (pinfunction "CBUS1_22") (pintype "bidirectional"))
    )
    (net (code "265") (name "unconnected-(IC19-CBUS2-Pad13)") (class "Default")
      (node (ref "IC19") (pin "13") (pinfunction "CBUS2_13") (pintype "bidirectional"))
    )
    (net (code "266") (name "unconnected-(IC19-CBUS3-Pad14)") (class "Default")
      (node (ref "IC19") (pin "14") (pinfunction "CBUS3_14") (pintype "bidirectional"))
    )
    (net (code "267") (name "unconnected-(IC19-CBUS4-Pad12)") (class "Default")
      (node (ref "IC19") (pin "12") (pinfunction "CBUS4_12") (pintype "bidirectional"))
    )
    (net (code "268") (name "unconnected-(IC19-OSCI-Pad27)") (class "Default")
      (node (ref "IC19") (pin "27") (pinfunction "OSCI_27") (pintype "input"))
    )
    (net (code "269") (name "unconnected-(IC19-OSCO-Pad28)") (class "Default")
      (node (ref "IC19") (pin "28") (pinfunction "OSCO_28") (pintype "output"))
    )
    (net (code "270") (name "unconnected-(IC19-~{DCD}-Pad10)") (class "Default")
      (node (ref "IC19") (pin "10") (pinfunction "~{DCD}_10") (pintype "input"))
    )
    (net (code "271") (name "unconnected-(IC19-~{DSR}-Pad9)") (class "Default")
      (node (ref "IC19") (pin "9") (pinfunction "~{DSR}_9") (pintype "input"))
    )
    (net (code "272") (name "unconnected-(IC19-~{DTR}-Pad2)") (class "Default")
      (node (ref "IC19") (pin "2") (pinfunction "~{DTR}_2") (pintype "output"))
    )
    (net (code "273") (name "unconnected-(IC19-~{RESET}-Pad19)") (class "Default")
      (node (ref "IC19") (pin "19") (pinfunction "~{RESET}_19") (pintype "input"))
    )
    (net (code "274") (name "unconnected-(IC19-~{RI}-Pad6)") (class "Default")
      (node (ref "IC19") (pin "6") (pinfunction "~{RI}_6") (pintype "input"))
    )
    (net (code "275") (name "unconnected-(IC20-N{slash}C-Pad4)") (class "Default")
      (node (ref "IC20") (pin "4") (pinfunction "N/C_4") (pintype "bidirectional"))
    )
    (net (code "276") (name "unconnected-(J3-3-PadP3)") (class "Default")
      (node (ref "J3") (pin "P3") (pinfunction "3_P3") (pintype "passive"))
    )
    (net (code "277") (name "unconnected-(J4-3-PadP3)") (class "Default")
      (node (ref "J4") (pin "P3") (pinfunction "3_P3") (pintype "passive"))
    )
    (net (code "278") (name "unconnected-(JP1-Pad6)") (class "Default")
      (node (ref "JP1") (pin "6") (pinfunction "6_6") (pintype "passive"))
    )
    (net (code "279") (name "unconnected-(OSC1-STANDBY#-PadP$1)") (class "Default")
      (node (ref "OSC1") (pin "P$1") (pinfunction "STANDBY#_P$1") (pintype "passive"))
    )
    (net (code "280") (name "unconnected-(OSC2-STANDBY#-PadP$1)") (class "Default")
      (node (ref "OSC2") (pin "P$1") (pinfunction "STANDBY#_P$1") (pintype "passive"))
    )
    (net (code "281") (name "unconnected-(PDI-Pad3)") (class "Default")
      (node (ref "PDI") (pin "3") (pinfunction "3_3") (pintype "passive"))
    )
    (net (code "282") (name "unconnected-(PDI-Pad4)") (class "Default")
      (node (ref "PDI") (pin "4") (pinfunction "4_4") (pintype "passive"))
    )
    (net (code "283") (name "unconnected-(USB1-4-PadP$4)") (class "Default")
      (node (ref "USB1") (pin "P$4") (pinfunction "4_P$4") (pintype "bidirectional"))
    )
    (net (code "284") (name "unconnected-(USB1-P$2-PadSHIELD_1)") (class "Default")
      (node (ref "USB1") (pin "SHIELD_1") (pinfunction "P$2_SHIELD_1") (pintype "bidirectional"))
    )
    (net (code "285") (name "unconnected-(USB1-P$3-PadSHIELD_2)") (class "Default")
      (node (ref "USB1") (pin "SHIELD_2") (pinfunction "P$3_SHIELD_2") (pintype "bidirectional"))
    )
    (net (code "286") (name "unconnected-(USB1-P$5-PadP$6)") (class "Default")
      (node (ref "USB1") (pin "P$6") (pinfunction "P$5_P$6") (pintype "bidirectional"))
    )
    (net (code "287") (name "unconnected-(USB1-P$6-PadP$7)") (class "Default")
      (node (ref "USB1") (pin "P$7") (pinfunction "P$6_P$7") (pintype "bidirectional"))
    )
    (net (code "288") (name "unconnected-(USB2-4-PadP$4)") (class "Default")
      (node (ref "USB2") (pin "P$4") (pinfunction "4_P$4") (pintype "bidirectional"))
    )
    (net (code "289") (name "unconnected-(USB2-P$2-PadSHIELD_2)") (class "Default")
      (node (ref "USB2") (pin "SHIELD_2") (pinfunction "P$2_SHIELD_2") (pintype "bidirectional"))
    )
    (net (code "290") (name "unconnected-(USB2-P$3-PadSHIELD_3)") (class "Default")
      (node (ref "USB2") (pin "SHIELD_3") (pinfunction "P$3_SHIELD_3") (pintype "bidirectional"))
    )
    (net (code "291") (name "~{MCLR}") (class "Default")
      (node (ref "IC16") (pin "15") (pinfunction "~{MCLR}_15") (pintype "bidirectional"))
      (node (ref "JP1") (pin "1") (pinfunction "1_1") (pintype "passive"))
      (node (ref "R57") (pin "1") (pinfunction "1_1") (pintype "passive"))
      (node (ref "SW1") (pin "O") (pinfunction "O_O") (pintype "passive"))
    )
    (net (code "292") (name "~{SS1}") (class "Default")
      (node (ref "IC16") (pin "32") (pinfunction "EBIA10/AN48/RPB8/PMA10/RB8_32") (pintype "bidirectional"))
      (node (ref "IC6") (pin "P25") (pinfunction "~{CLATCH}_P25") (pintype "bidirectional"))
    )
  )
)
